# fp_32_v1.net
KiCad netlist of a schematic drawn in EAGLE
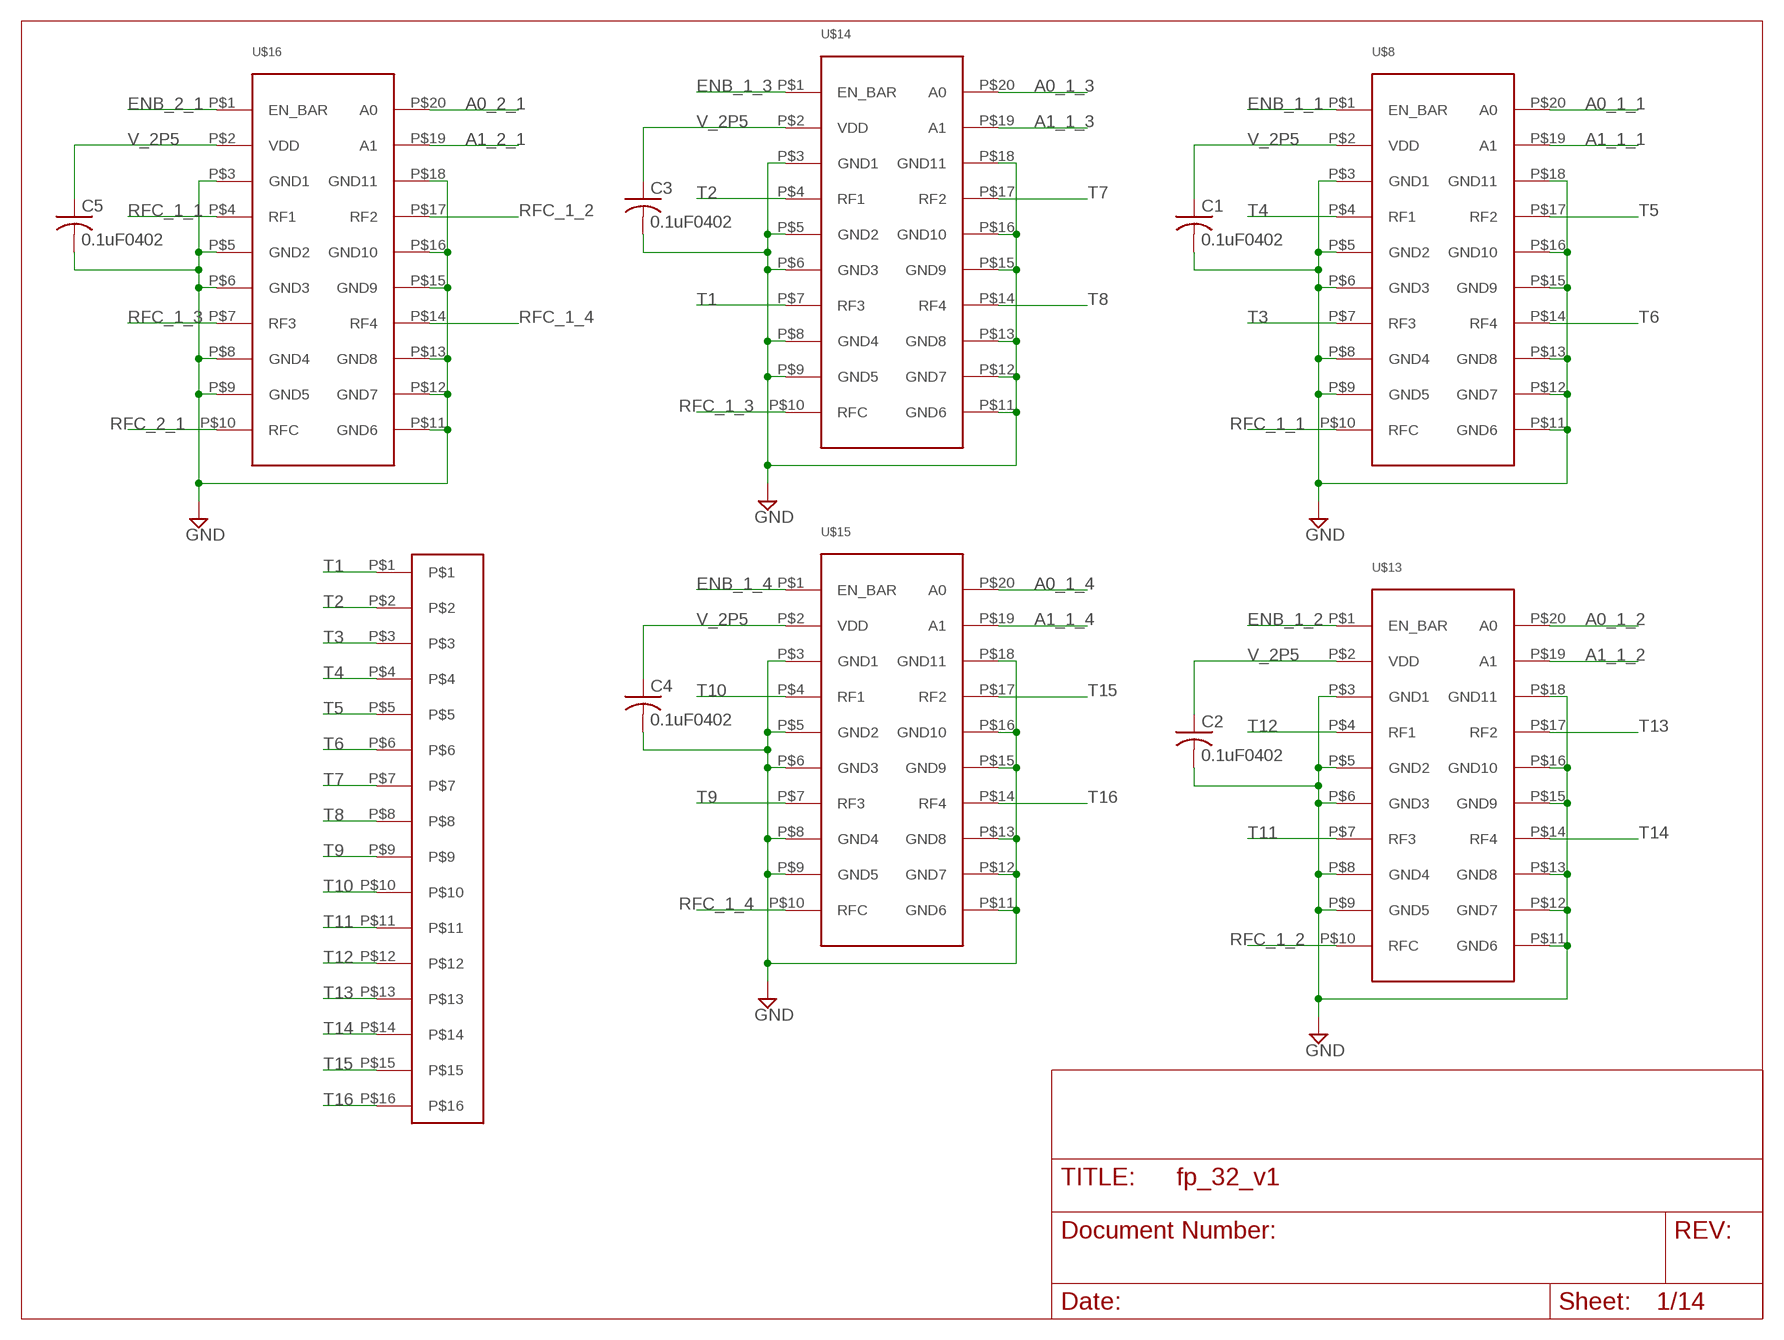
[diagram p0: schematic, sheet 1]
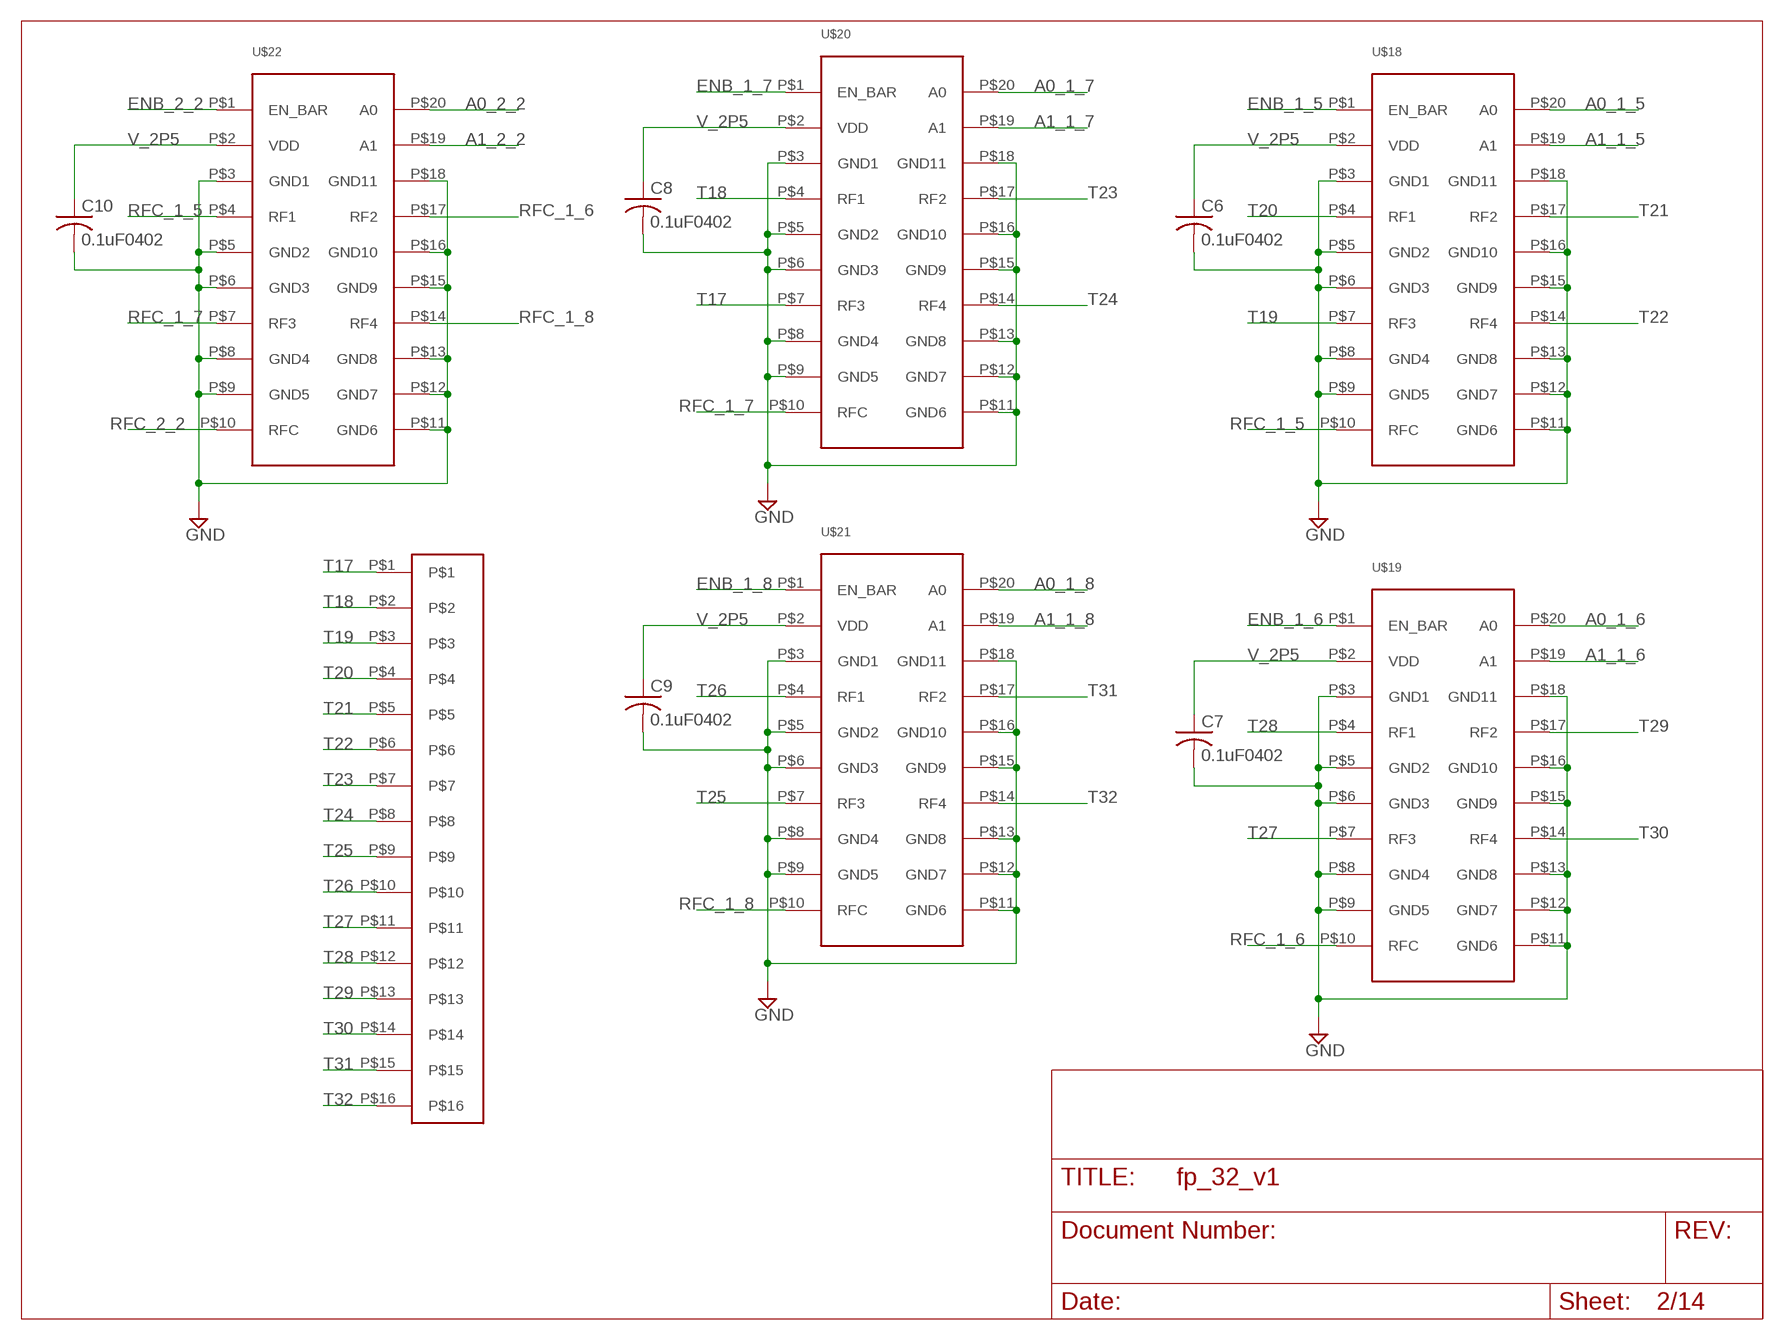
[diagram p1: schematic, sheet 2]
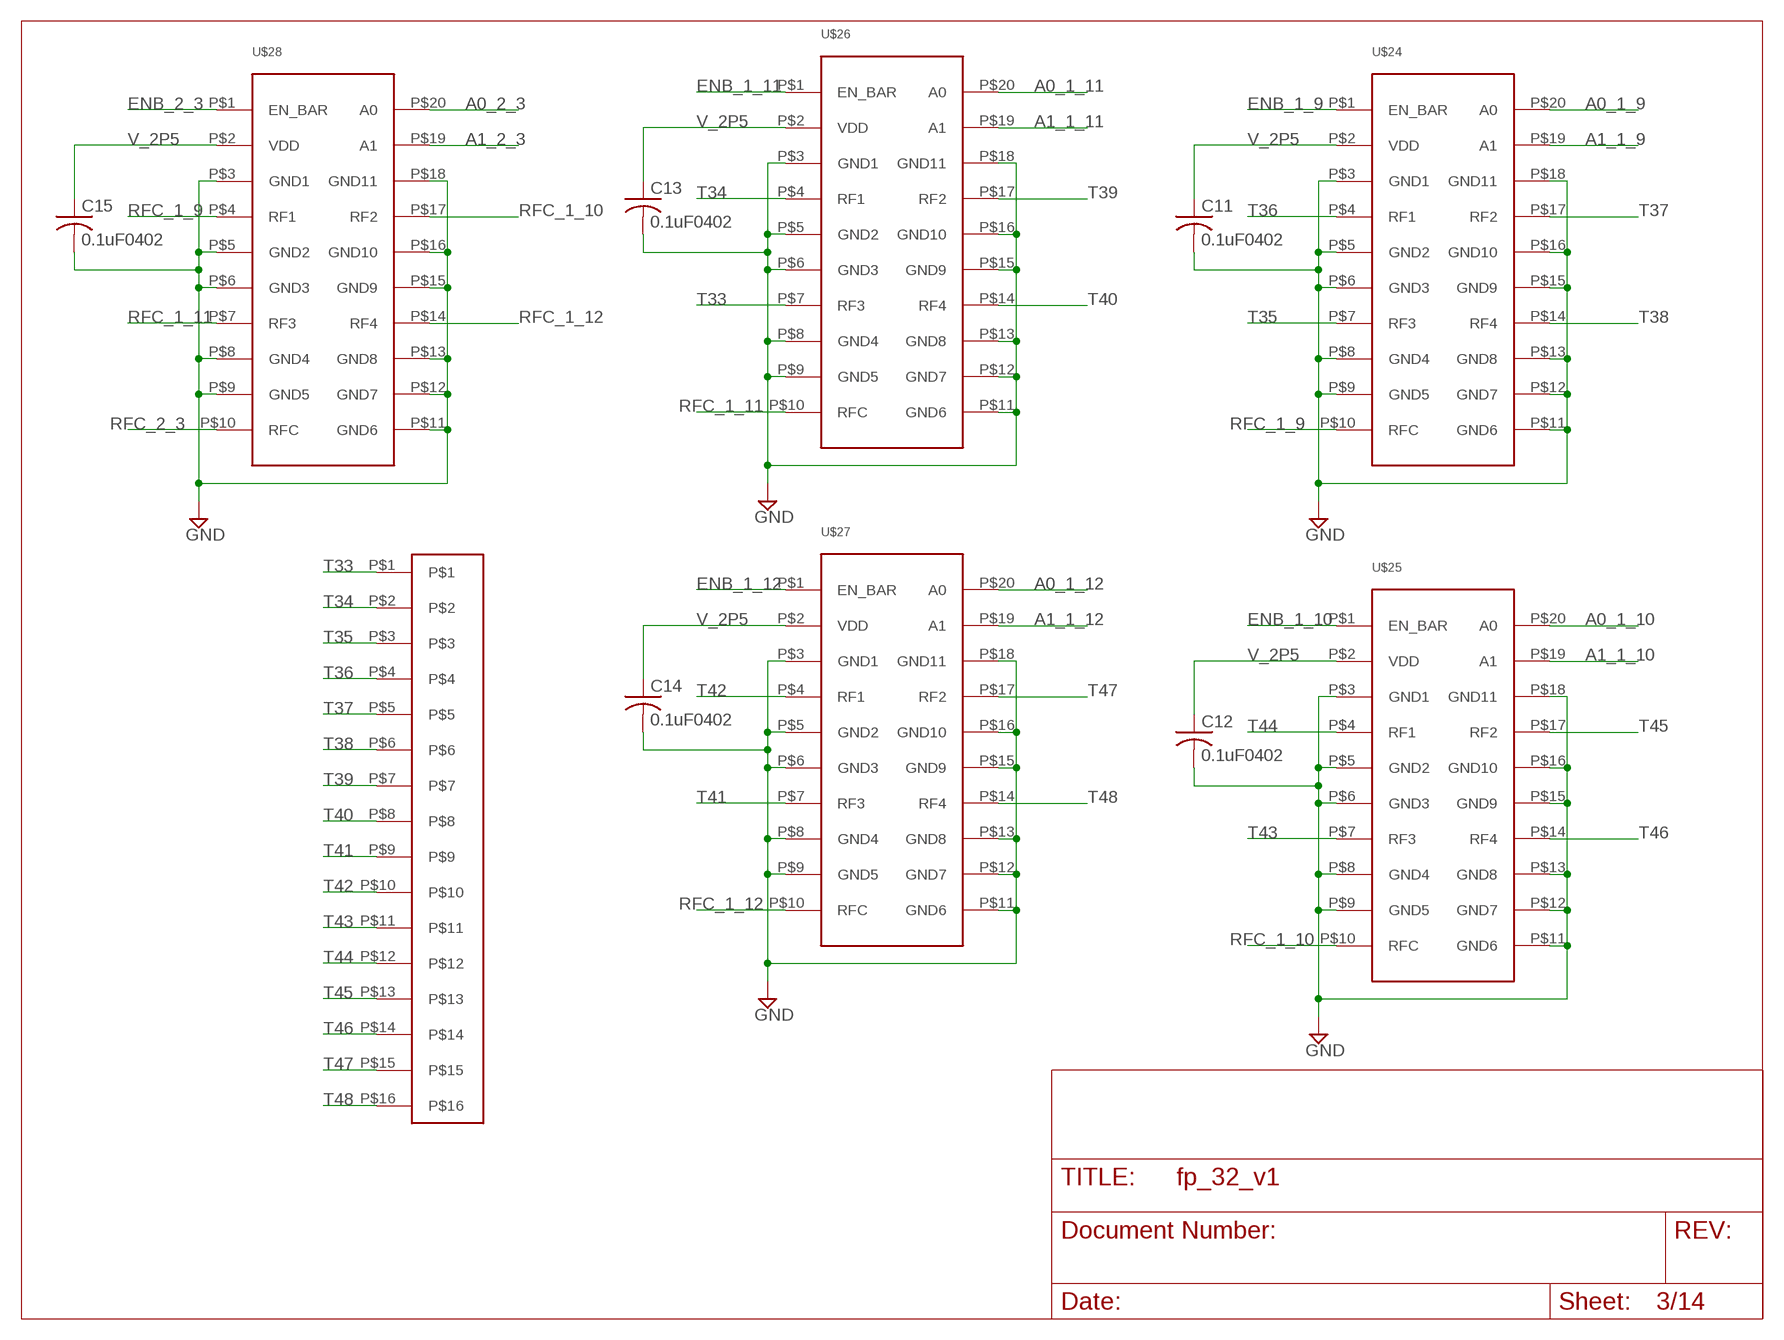
[diagram p2: schematic, sheet 3]
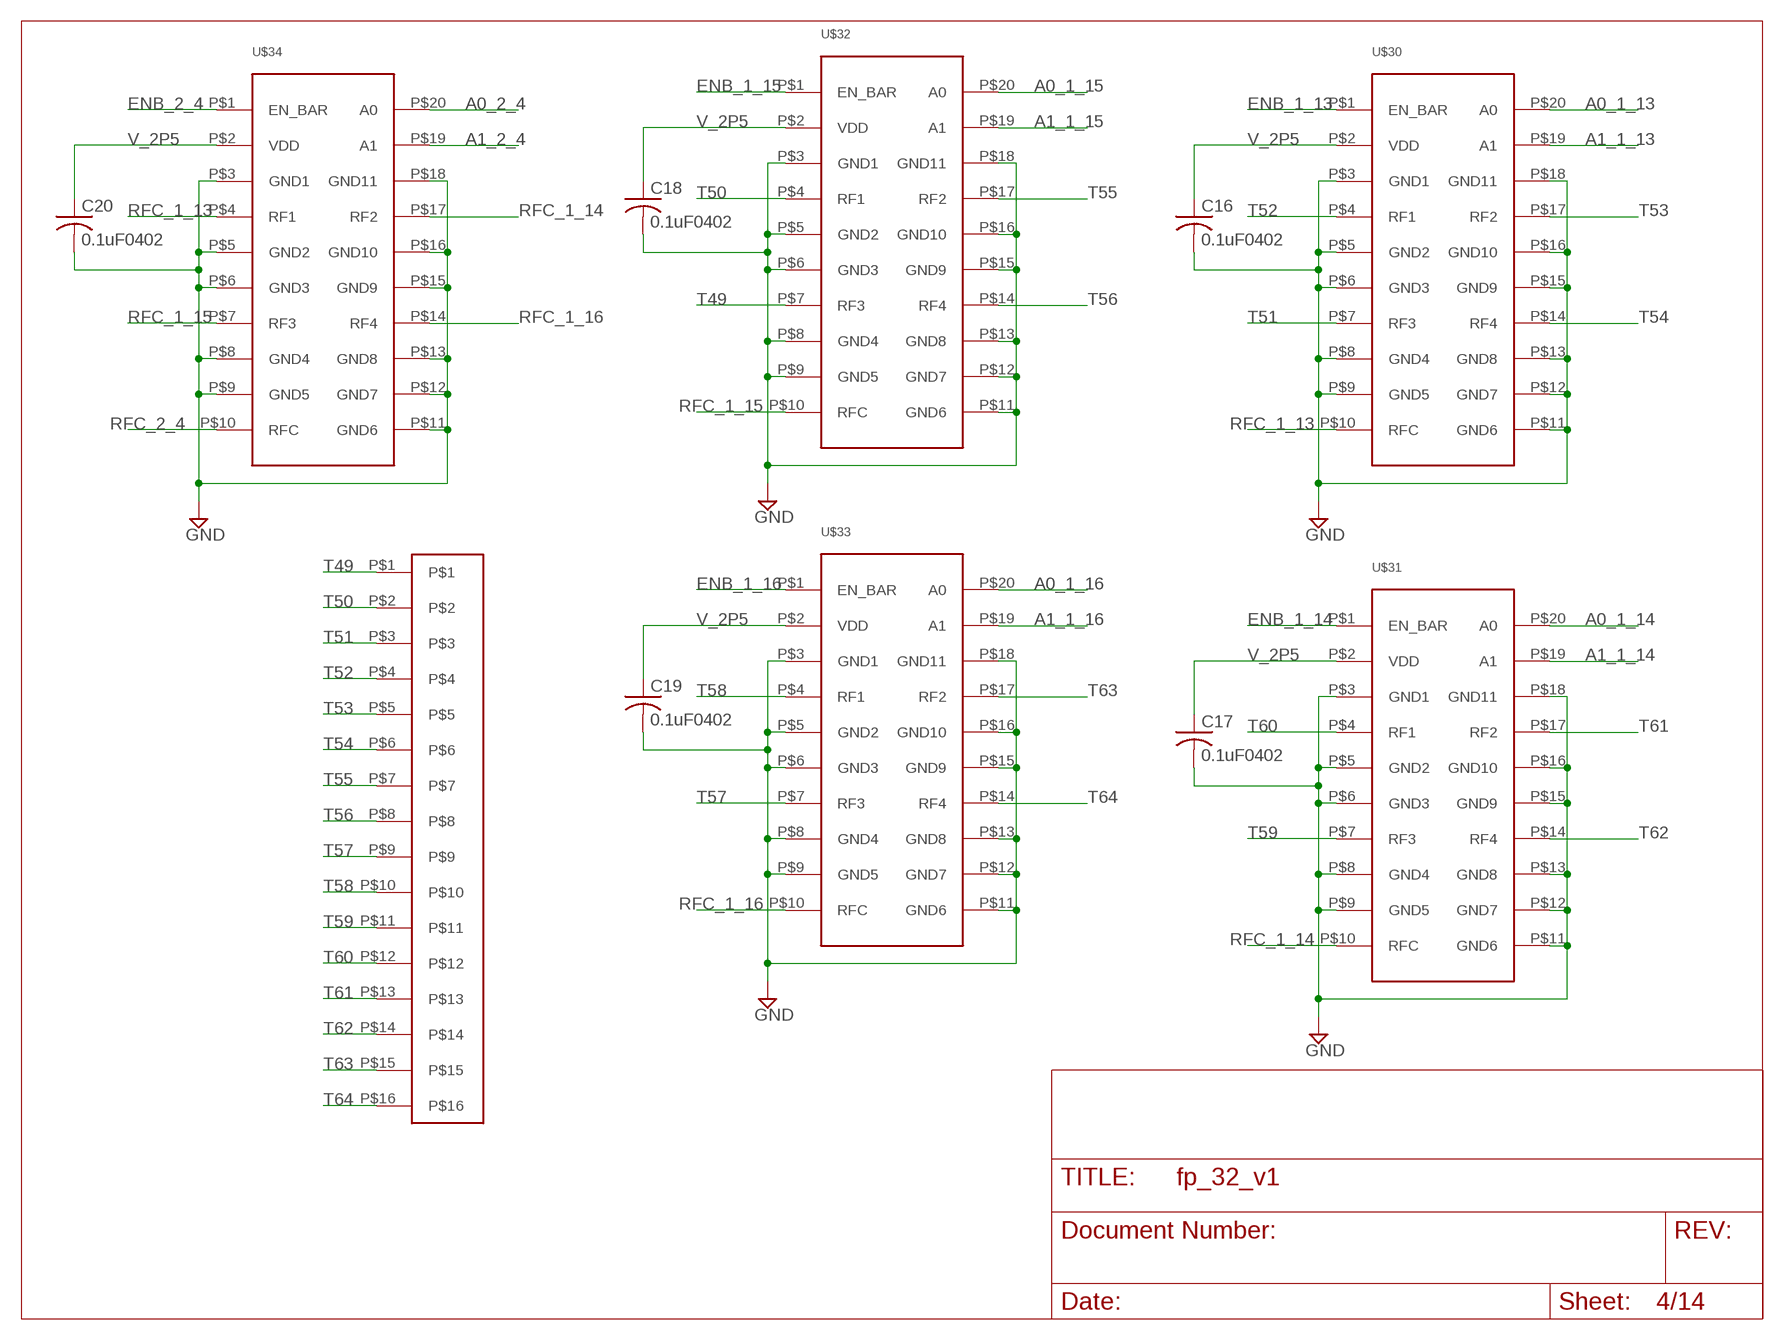
[diagram p3: schematic, sheet 4]
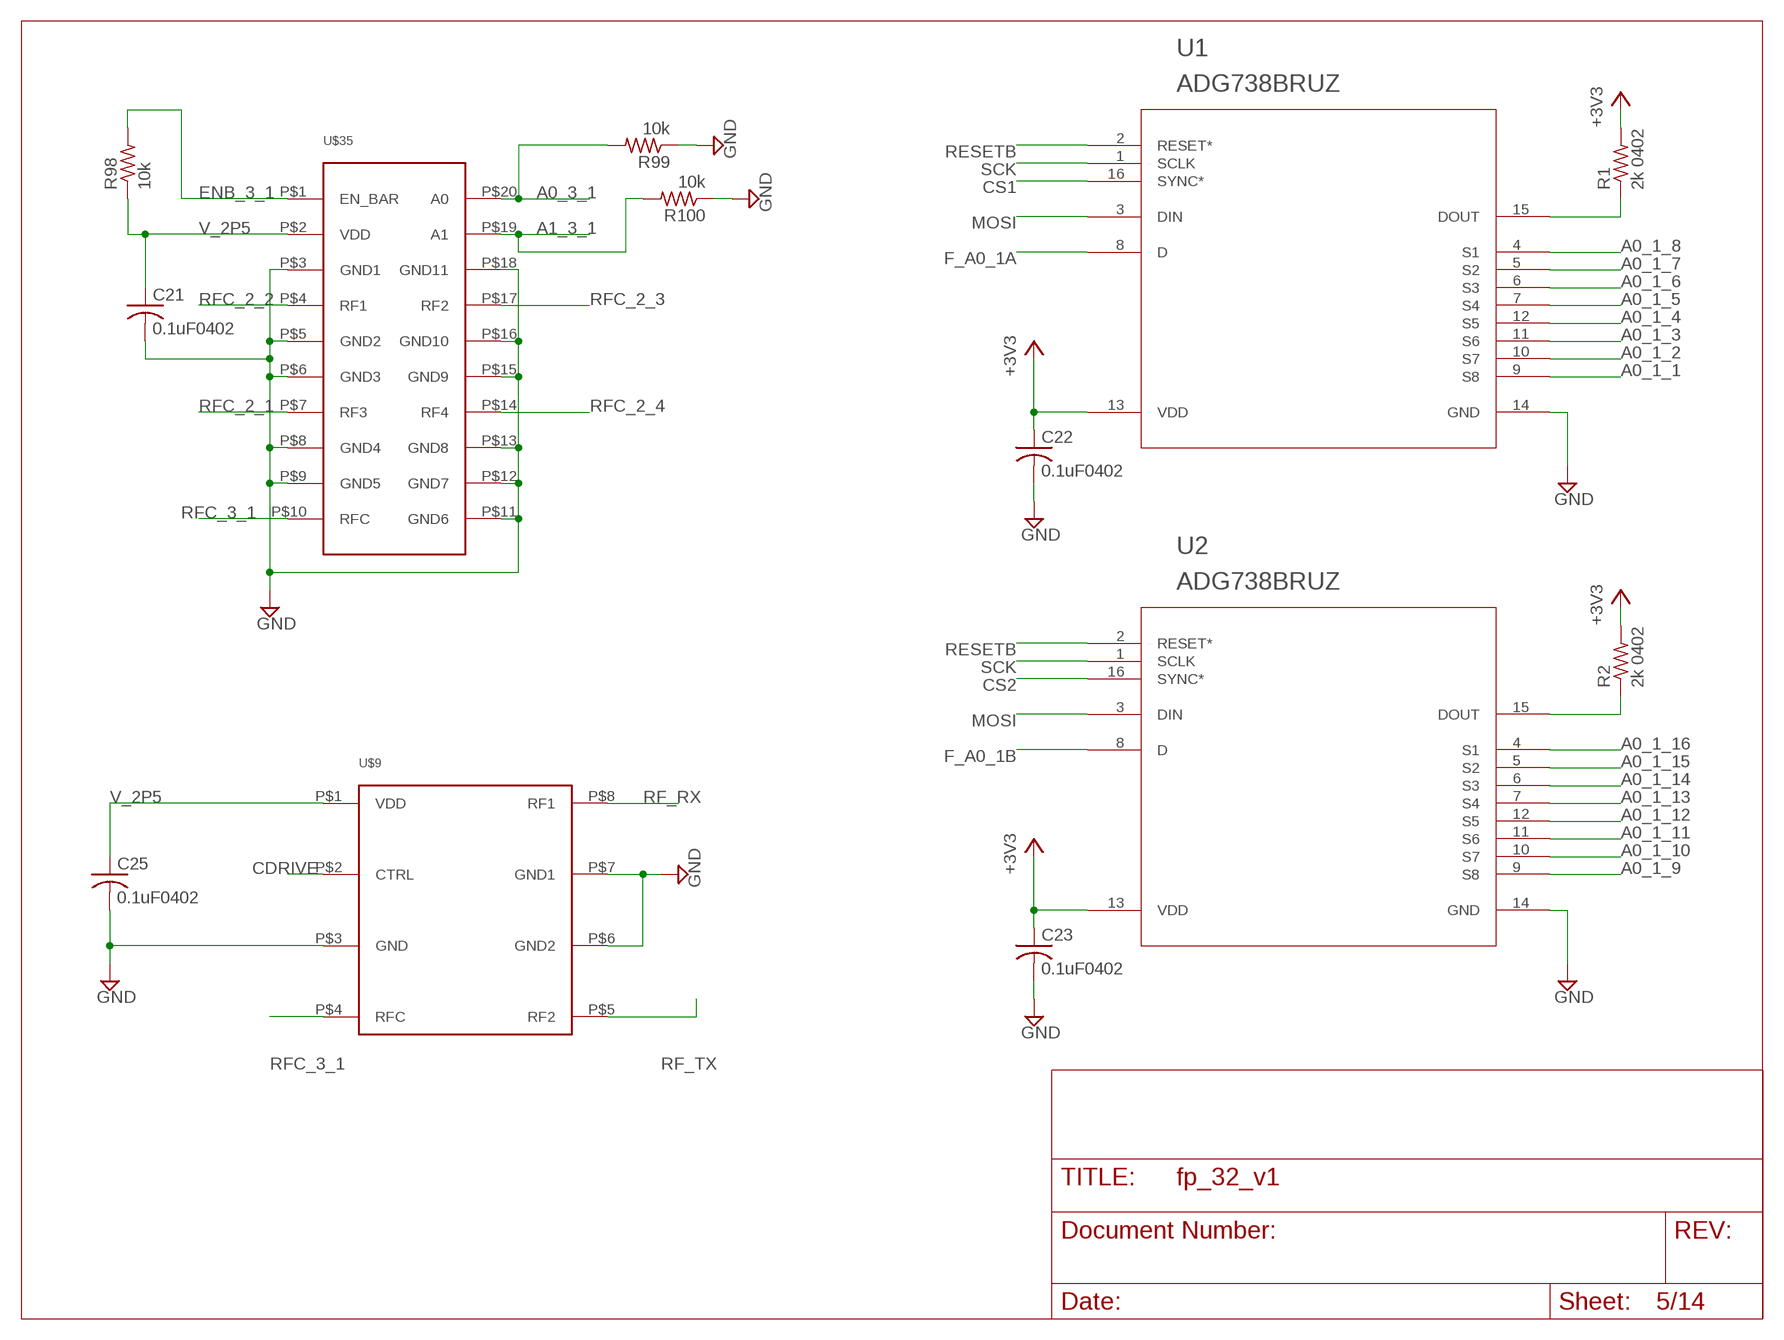
[diagram p4: schematic, sheet 5]
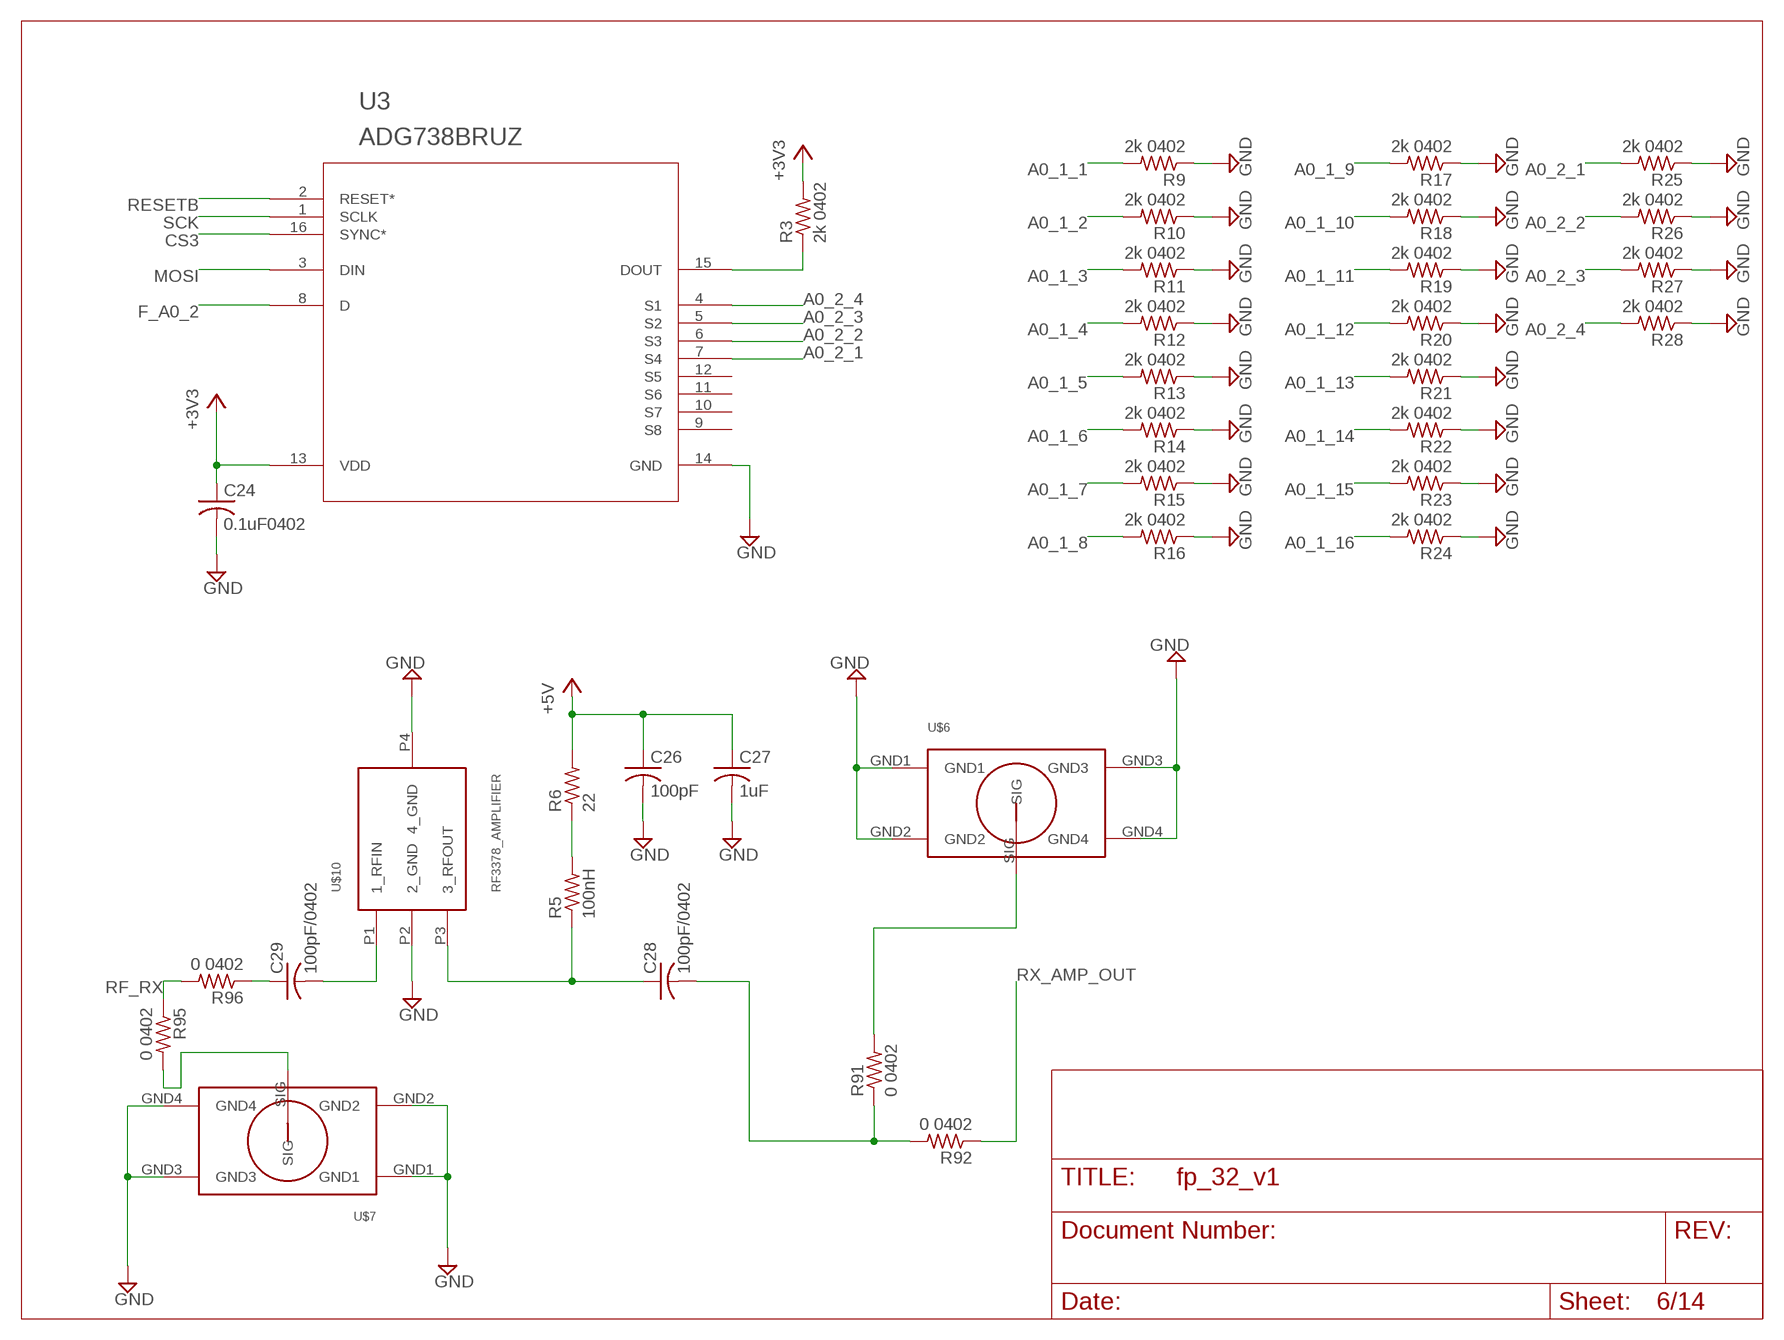
[diagram p5: schematic, sheet 6]
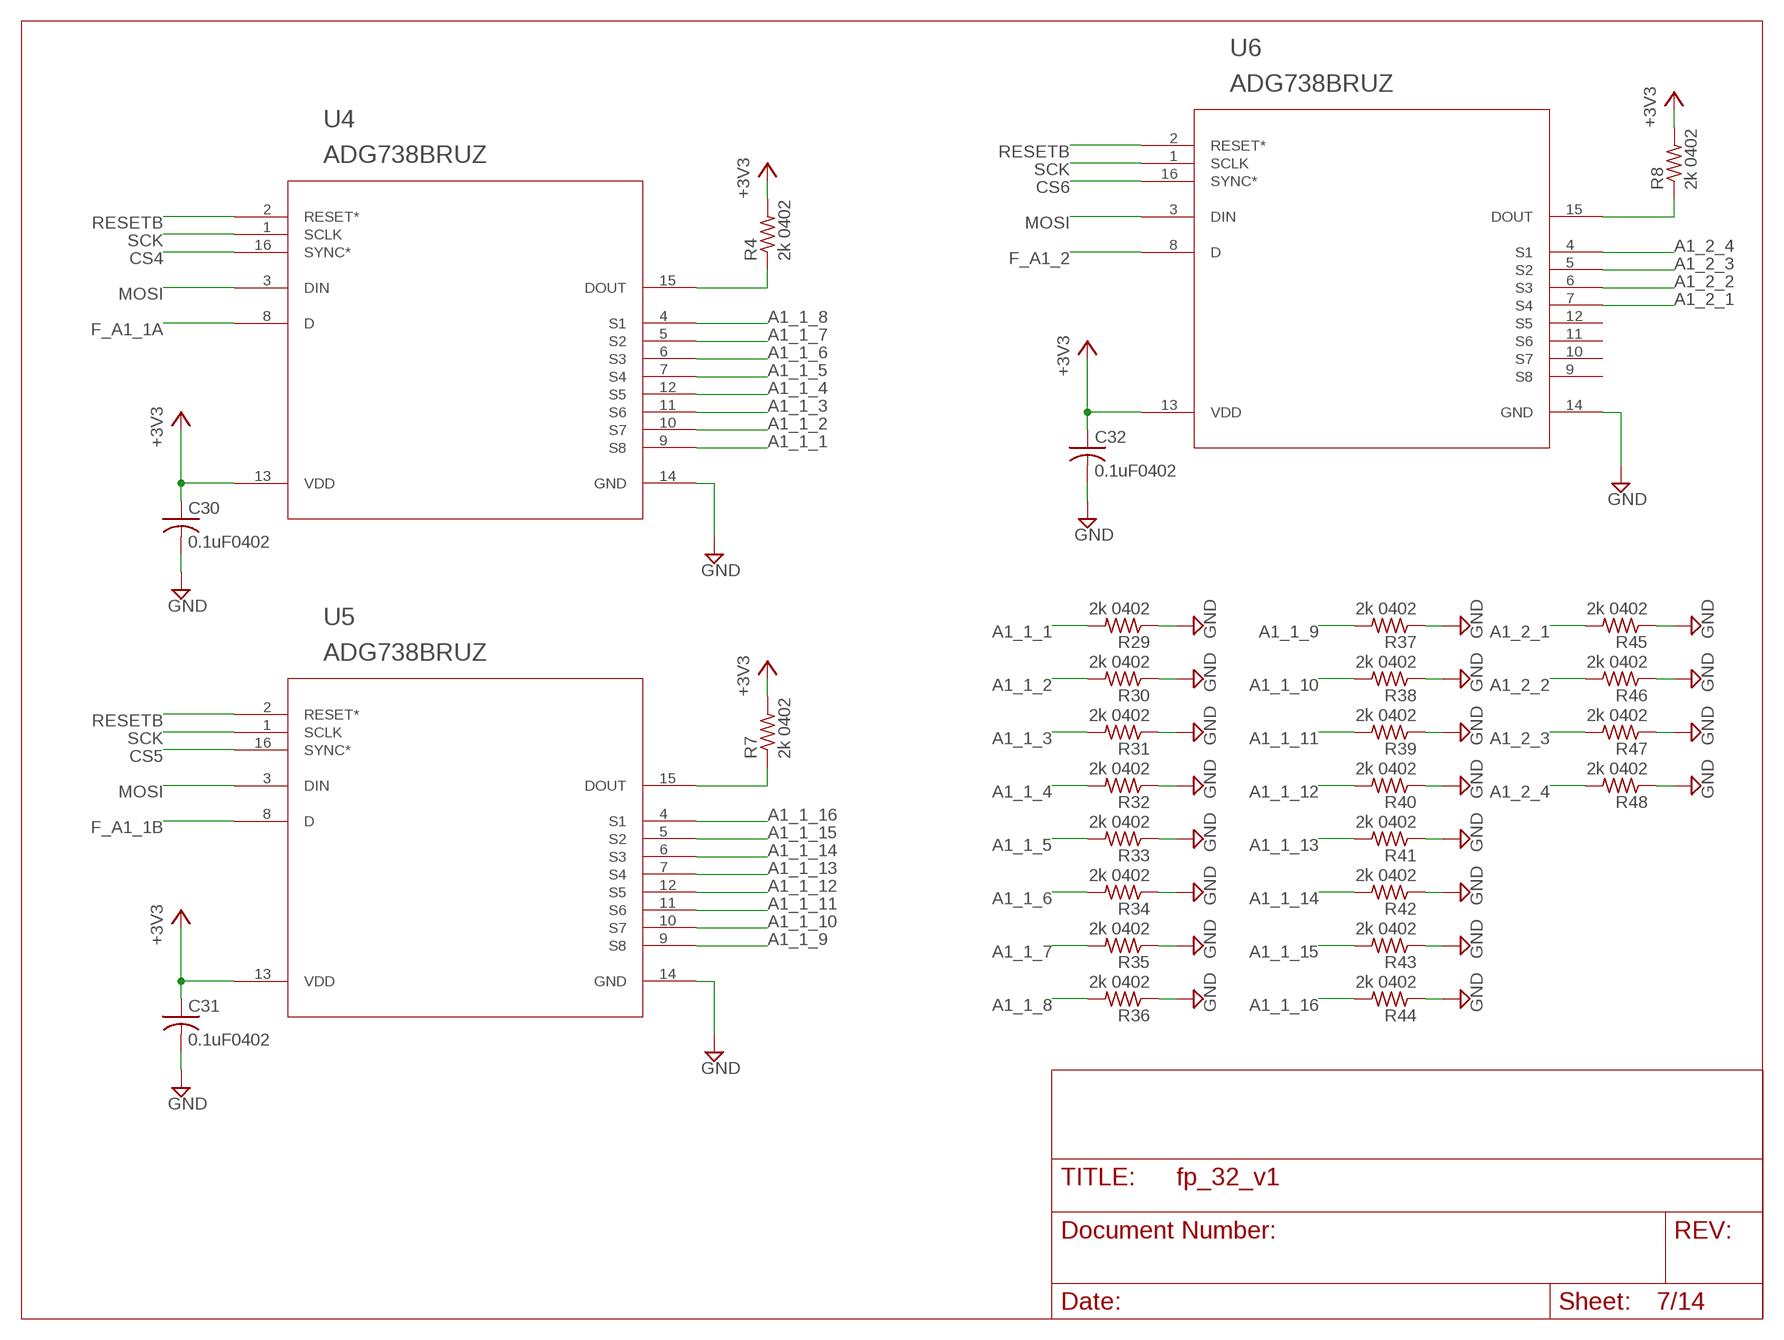
[diagram p6: schematic, sheet 7]
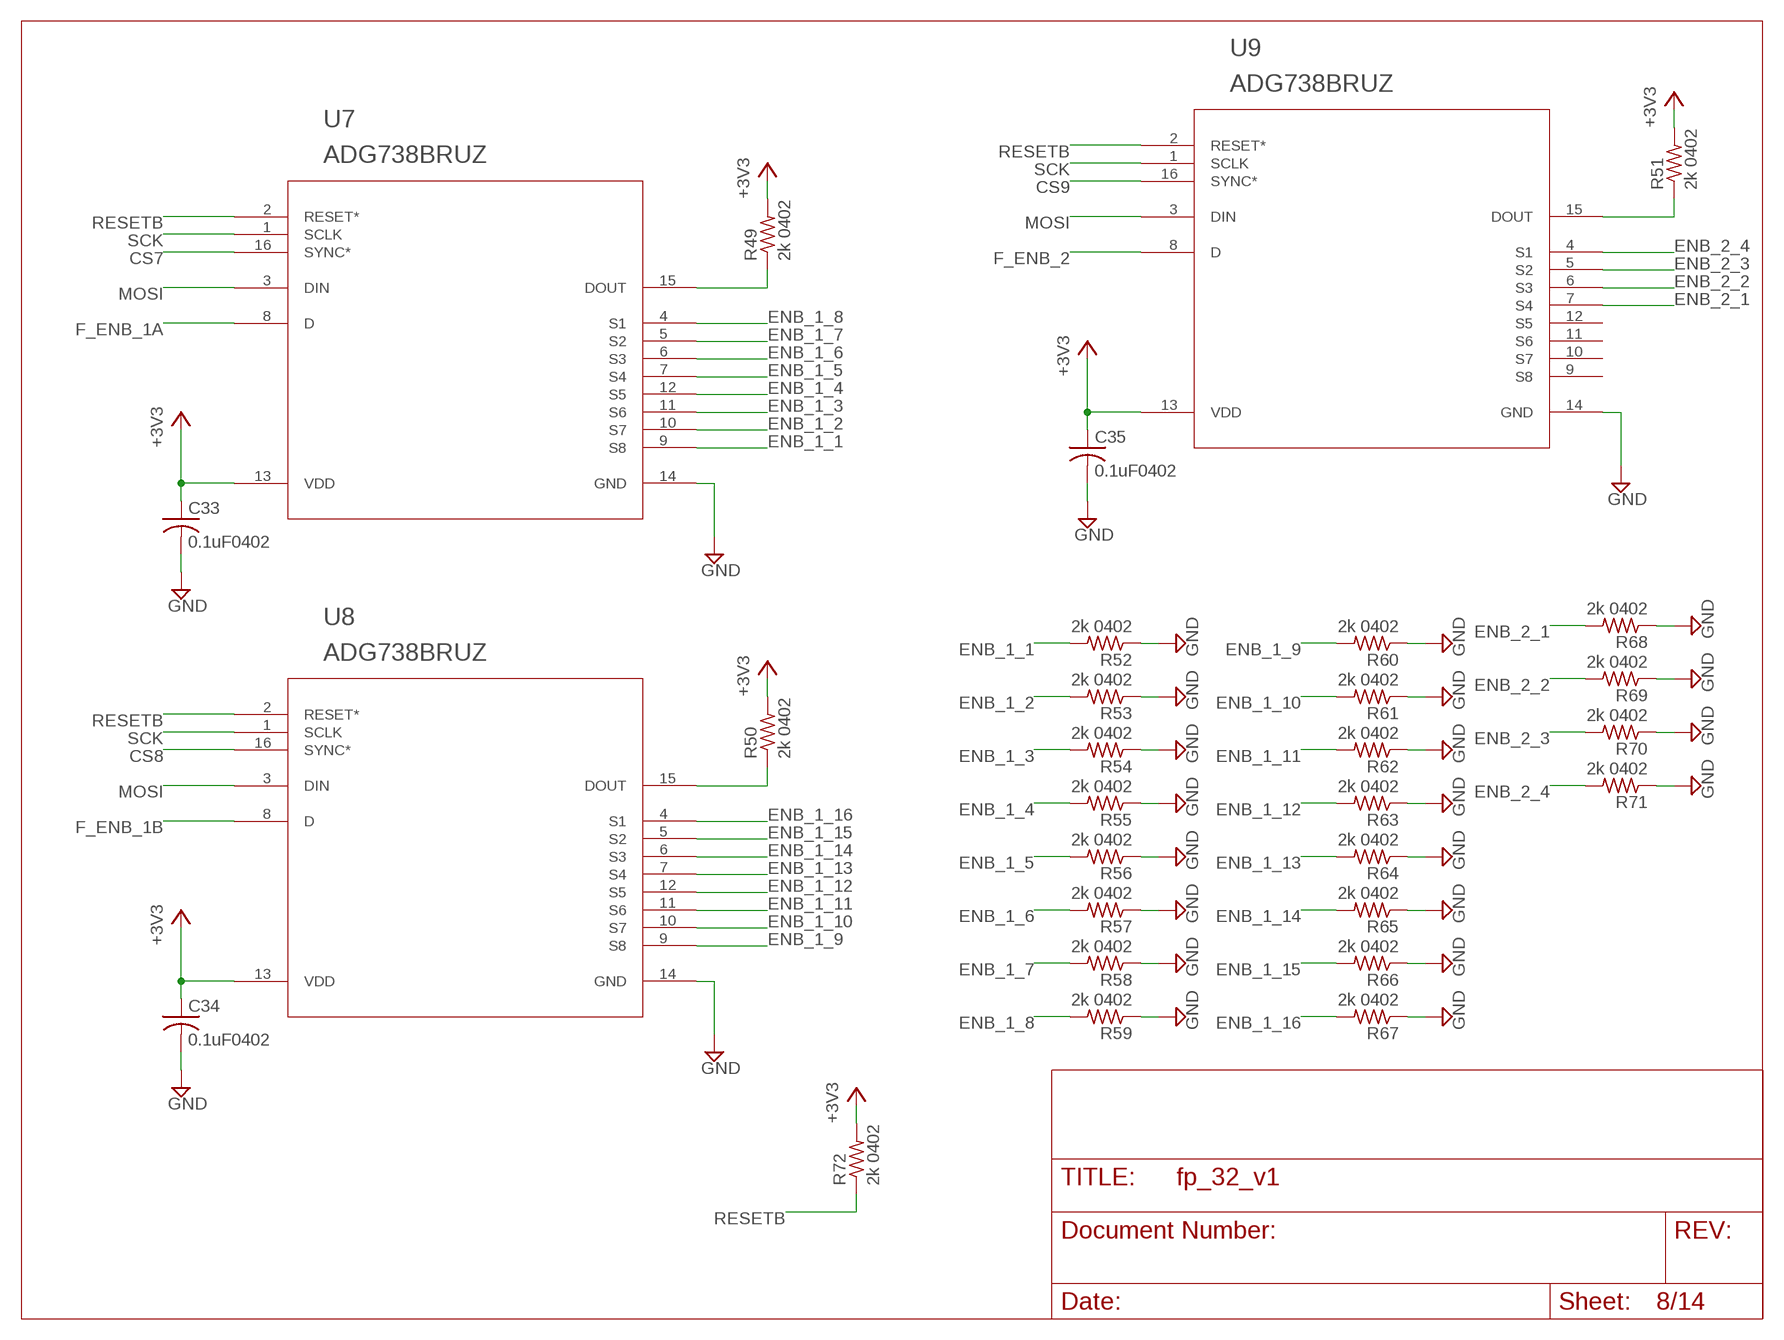
[diagram p7: schematic, sheet 8]
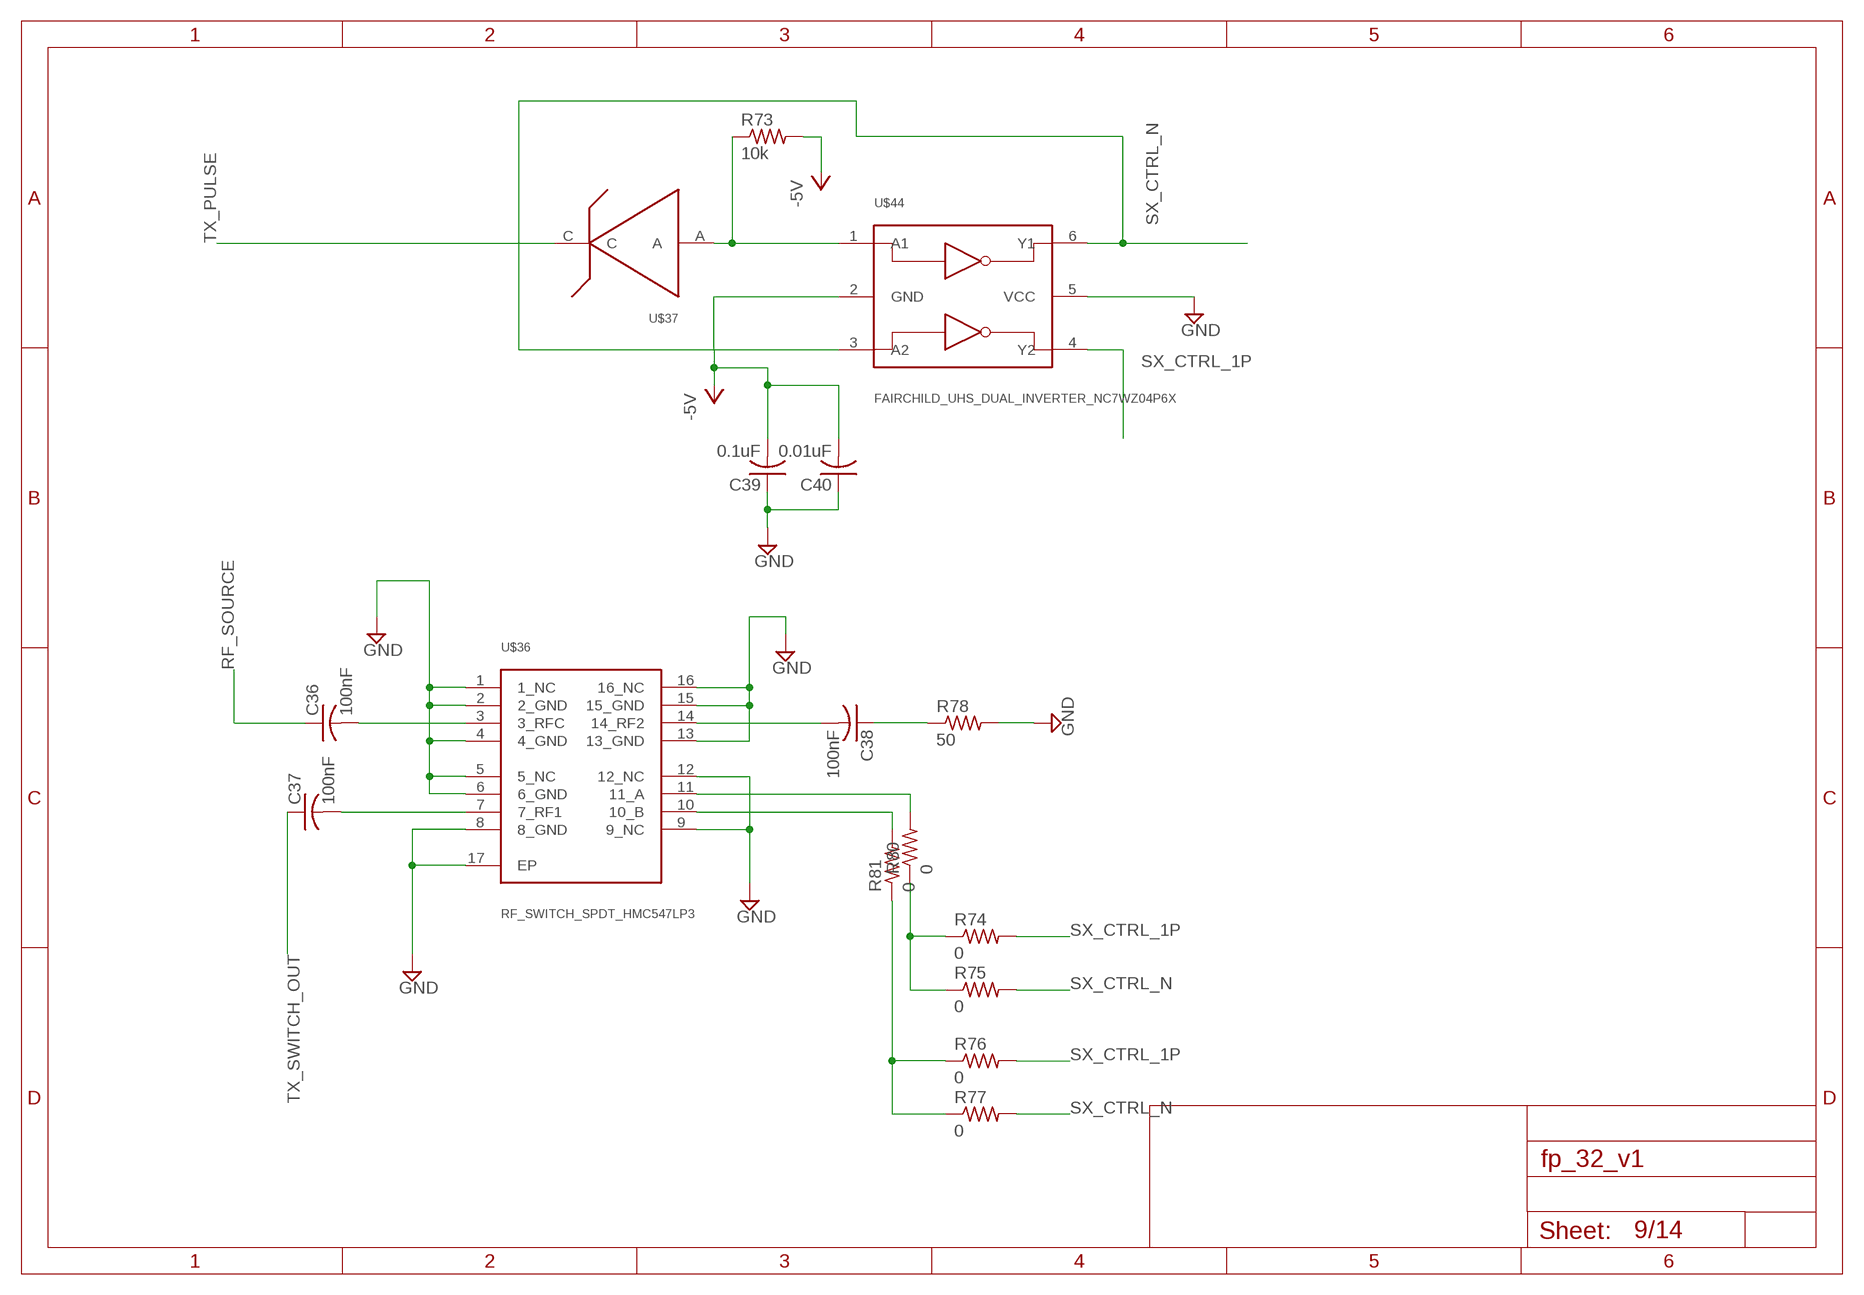
[diagram p8: schematic, sheet 9]
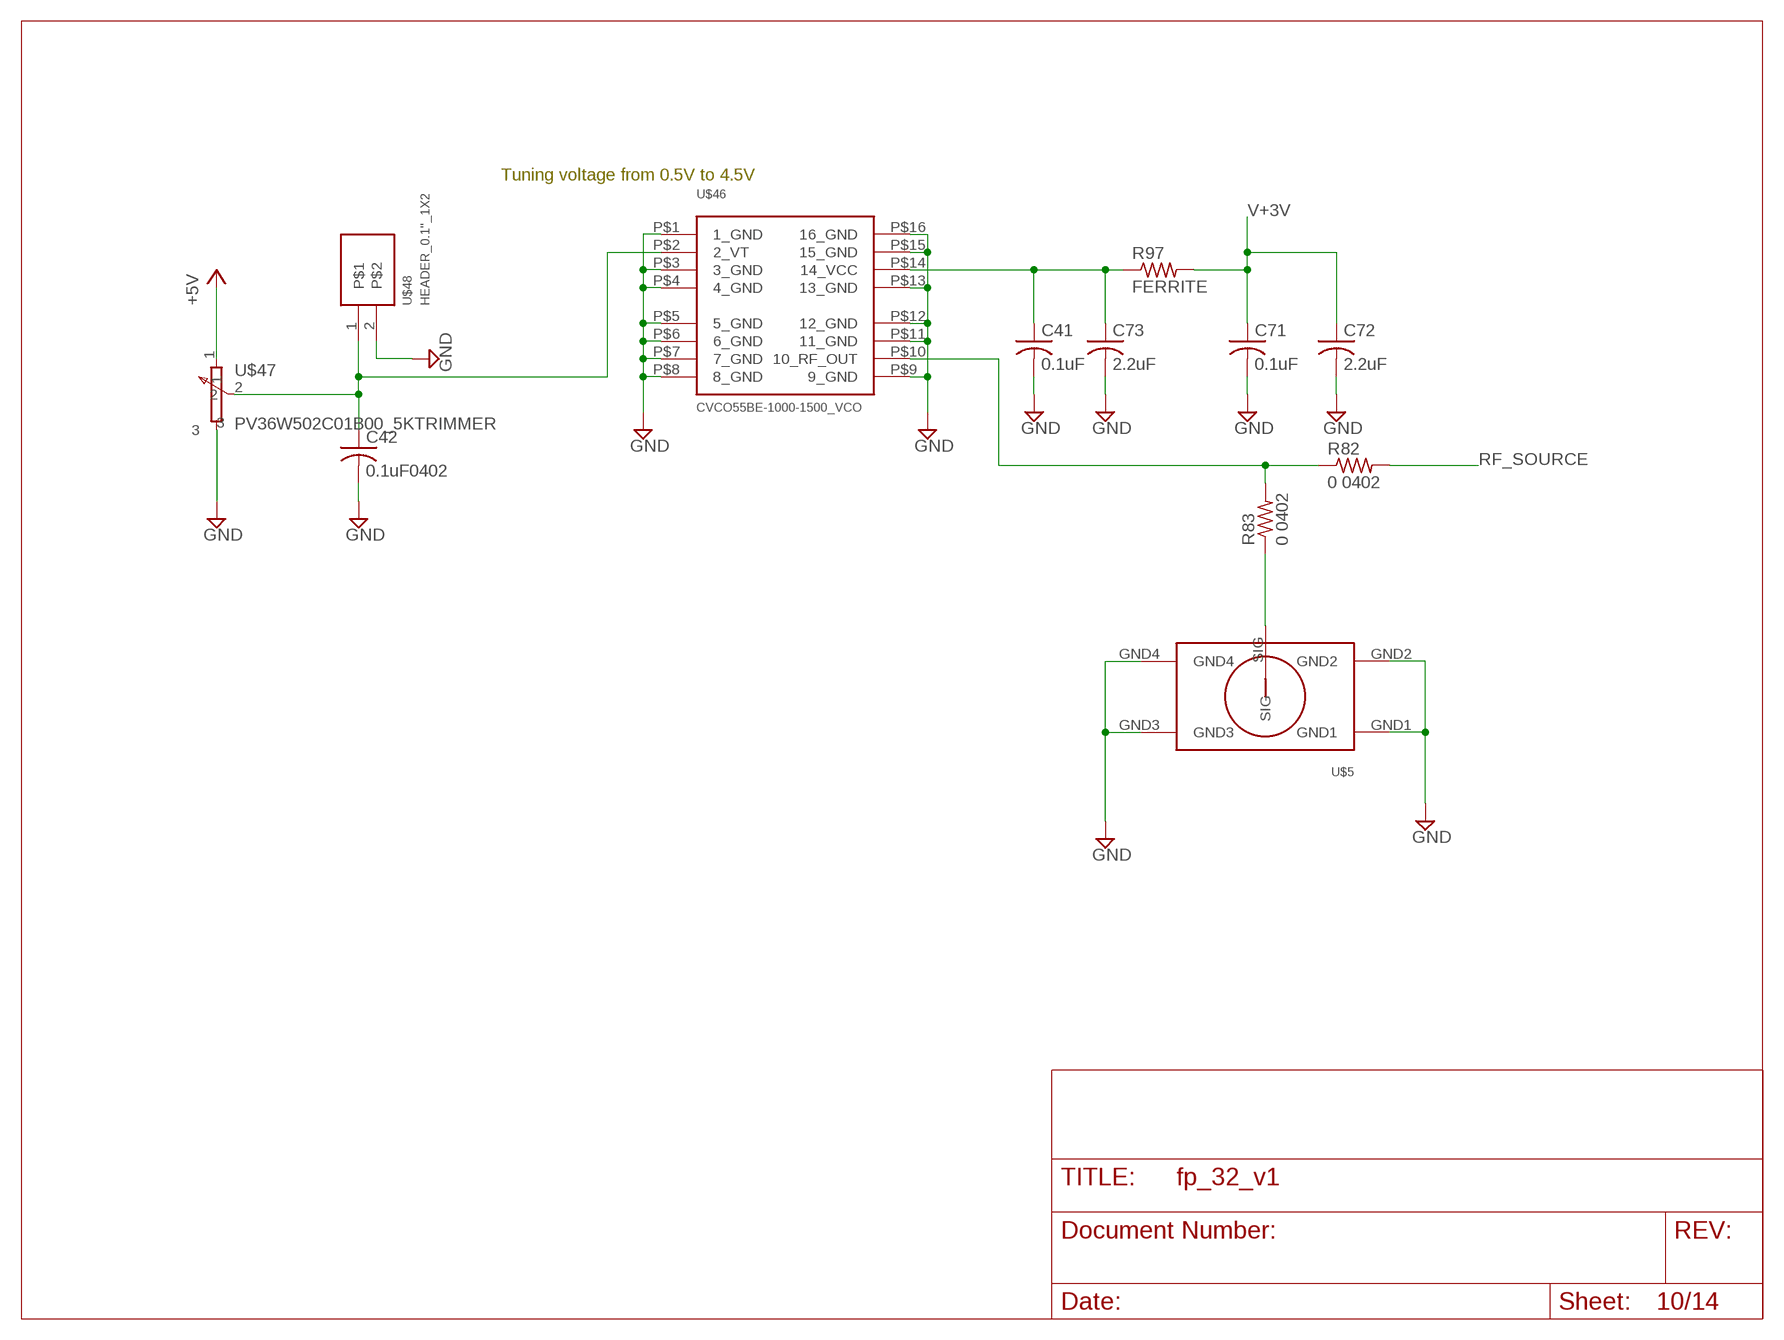
[diagram p9: schematic, sheet 10]
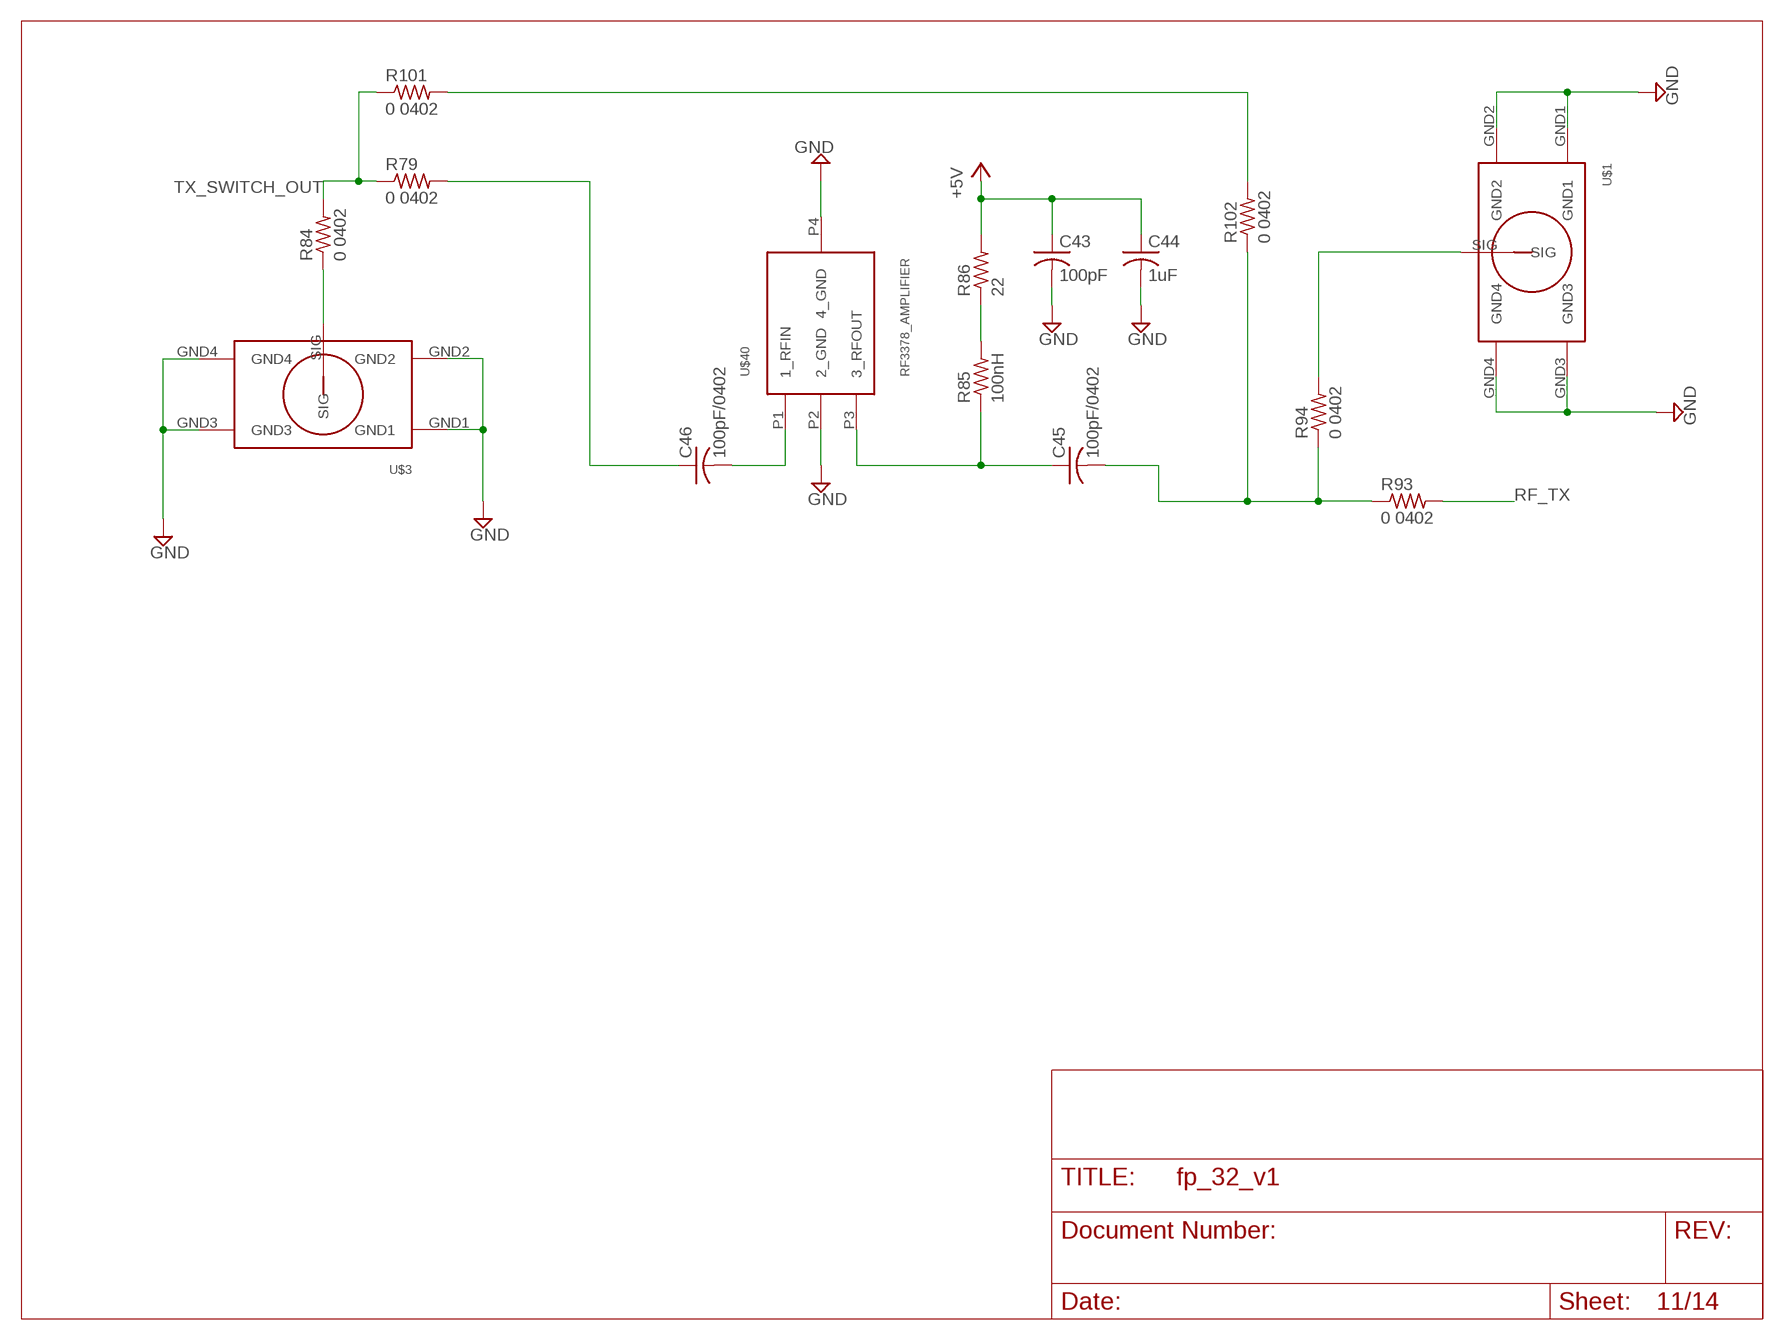
[diagram p10: schematic, sheet 11]
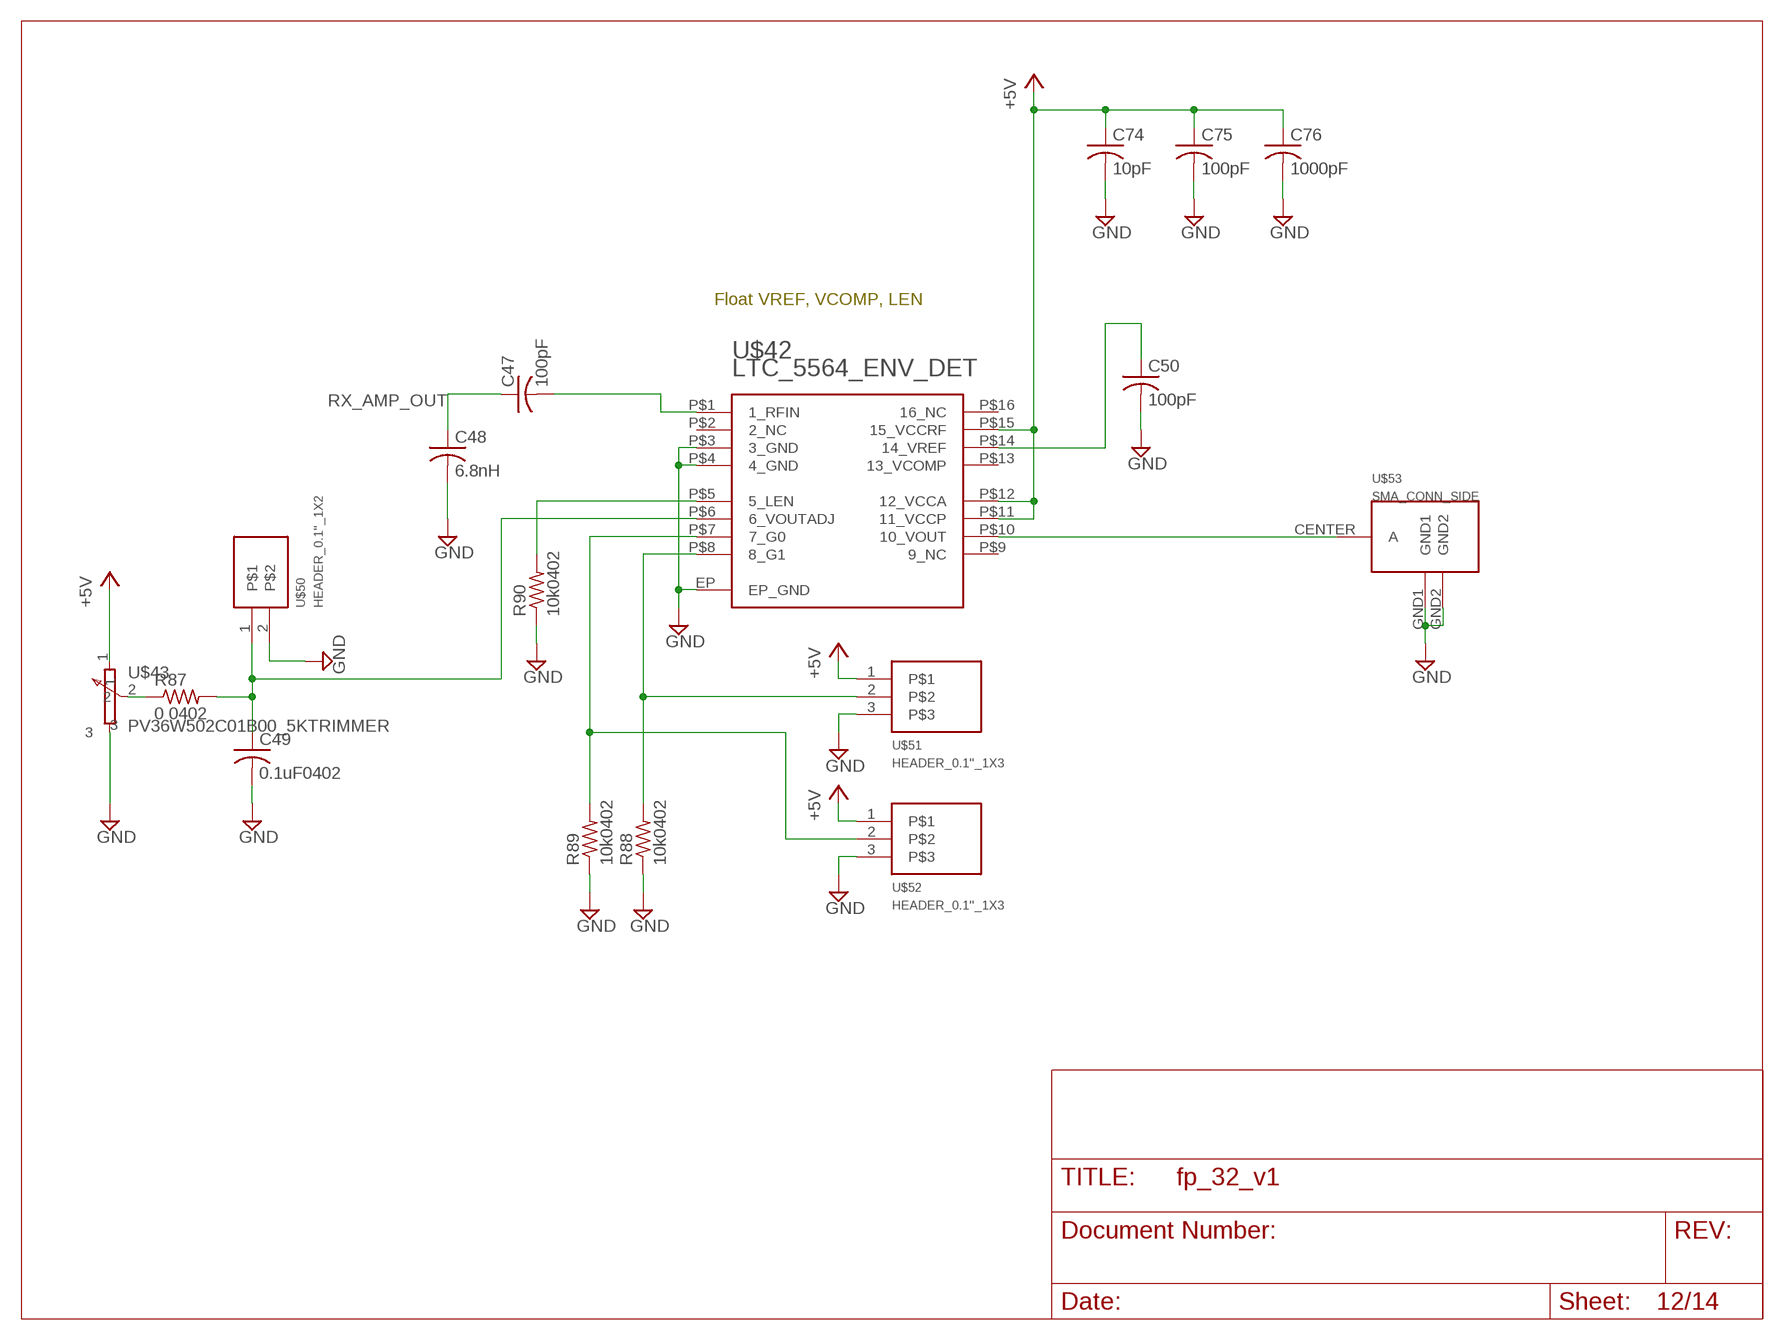
[diagram p11: schematic, sheet 12]
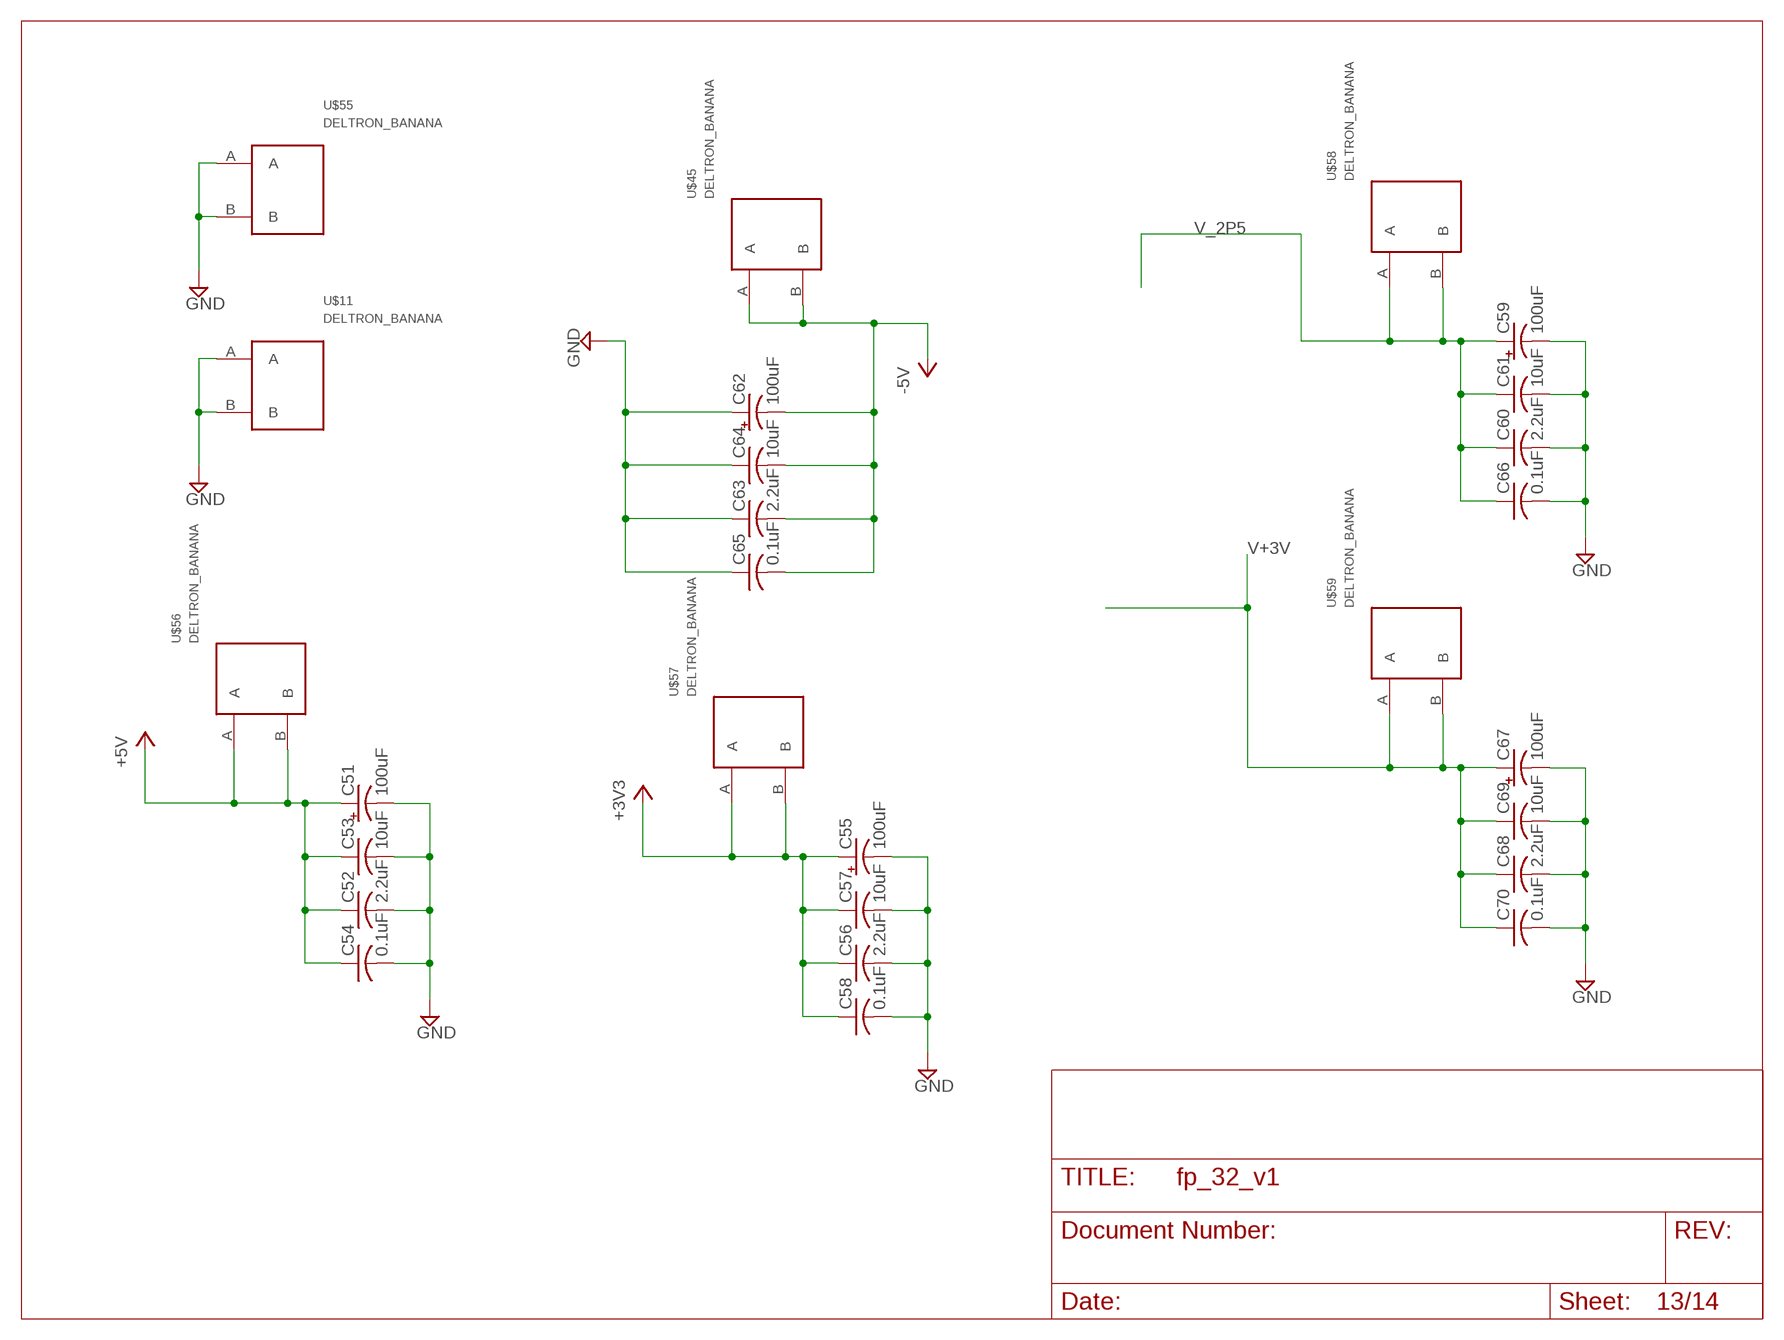
[diagram p12: schematic, sheet 13]
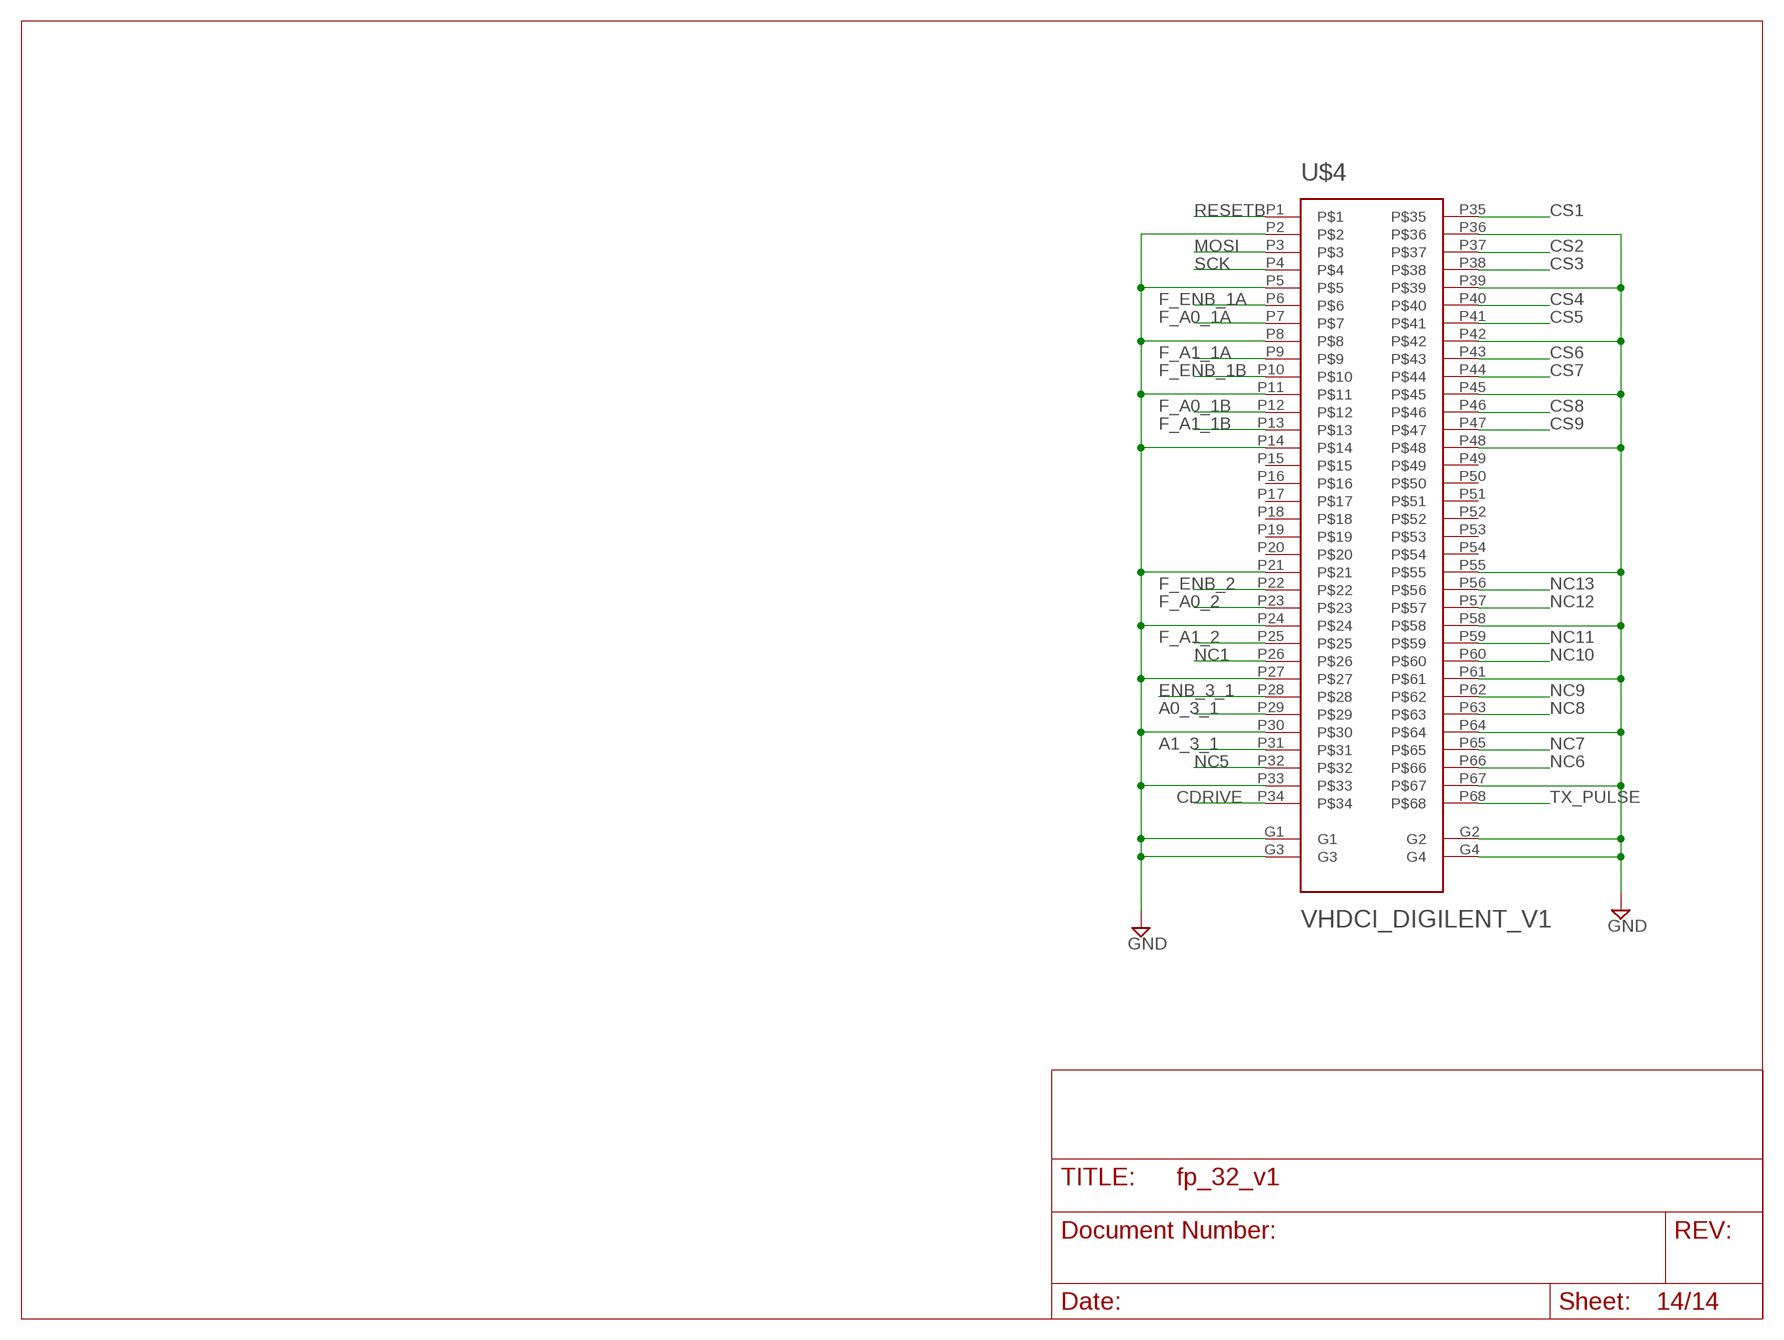
[diagram p13: schematic, sheet 14]

(export (version "E")
  (design (tool "Eeschema 10.0.6"))
  (components
    (comp (ref "C24")
      (value "0.1uF0402")
      (footprint "eagle-import:C0402")
      (libsource (lib "eagle-import") (part "C-USC0402"))
    )
    (comp (ref "C26")
      (value "100pF")
      (footprint "eagle-import:C0603")
      (libsource (lib "eagle-import") (part "C-USC0603"))
    )
    (comp (ref "C27")
      (value "1uF")
      (footprint "eagle-import:C0603")
      (libsource (lib "eagle-import") (part "C-USC0603"))
    )
    (comp (ref "C28")
      (value "100pF/0402")
      (footprint "eagle-import:C0402")
      (libsource (lib "eagle-import") (part "C-USC0402"))
    )
    (comp (ref "C29")
      (value "100pF/0402")
      (footprint "eagle-import:C0402")
      (libsource (lib "eagle-import") (part "C-USC0402"))
    )
    (comp (ref "R3")
      (value "2k 0402")
      (footprint "eagle-import:R0402")
      (libsource (lib "eagle-import") (part "R-US_R0402"))
    )
    (comp (ref "R5")
      (value "100nH")
      (footprint "eagle-import:R0603")
      (libsource (lib "eagle-import") (part "R-US_R0603"))
    )
    (comp (ref "R6")
      (value "22")
      (footprint "eagle-import:R0805")
      (libsource (lib "eagle-import") (part "R-US_R0805"))
    )
    (comp (ref "R9")
      (value "2k 0402")
      (footprint "eagle-import:R0402")
      (libsource (lib "eagle-import") (part "R-US_R0402"))
    )
    (comp (ref "R10")
      (value "2k 0402")
      (footprint "eagle-import:R0402")
      (libsource (lib "eagle-import") (part "R-US_R0402"))
    )
    (comp (ref "R11")
      (value "2k 0402")
      (footprint "eagle-import:R0402")
      (libsource (lib "eagle-import") (part "R-US_R0402"))
    )
    (comp (ref "R12")
      (value "2k 0402")
      (footprint "eagle-import:R0402")
      (libsource (lib "eagle-import") (part "R-US_R0402"))
    )
    (comp (ref "R13")
      (value "2k 0402")
      (footprint "eagle-import:R0402")
      (libsource (lib "eagle-import") (part "R-US_R0402"))
    )
    (comp (ref "R14")
      (value "2k 0402")
      (footprint "eagle-import:R0402")
      (libsource (lib "eagle-import") (part "R-US_R0402"))
    )
    (comp (ref "R15")
      (value "2k 0402")
      (footprint "eagle-import:R0402")
      (libsource (lib "eagle-import") (part "R-US_R0402"))
    )
    (comp (ref "R16")
      (value "2k 0402")
      (footprint "eagle-import:R0402")
      (libsource (lib "eagle-import") (part "R-US_R0402"))
    )
    (comp (ref "R17")
      (value "2k 0402")
      (footprint "eagle-import:R0402")
      (libsource (lib "eagle-import") (part "R-US_R0402"))
    )
    (comp (ref "R18")
      (value "2k 0402")
      (footprint "eagle-import:R0402")
      (libsource (lib "eagle-import") (part "R-US_R0402"))
    )
    (comp (ref "R19")
      (value "2k 0402")
      (footprint "eagle-import:R0402")
      (libsource (lib "eagle-import") (part "R-US_R0402"))
    )
    (comp (ref "R20")
      (value "2k 0402")
      (footprint "eagle-import:R0402")
      (libsource (lib "eagle-import") (part "R-US_R0402"))
    )
    (comp (ref "R21")
      (value "2k 0402")
      (footprint "eagle-import:R0402")
      (libsource (lib "eagle-import") (part "R-US_R0402"))
    )
    (comp (ref "R22")
      (value "2k 0402")
      (footprint "eagle-import:R0402")
      (libsource (lib "eagle-import") (part "R-US_R0402"))
    )
    (comp (ref "R23")
      (value "2k 0402")
      (footprint "eagle-import:R0402")
      (libsource (lib "eagle-import") (part "R-US_R0402"))
    )
    (comp (ref "R24")
      (value "2k 0402")
      (footprint "eagle-import:R0402")
      (libsource (lib "eagle-import") (part "R-US_R0402"))
    )
    (comp (ref "R25")
      (value "2k 0402")
      (footprint "eagle-import:R0402")
      (libsource (lib "eagle-import") (part "R-US_R0402"))
    )
    (comp (ref "R26")
      (value "2k 0402")
      (footprint "eagle-import:R0402")
      (libsource (lib "eagle-import") (part "R-US_R0402"))
    )
    (comp (ref "R27")
      (value "2k 0402")
      (footprint "eagle-import:R0402")
      (libsource (lib "eagle-import") (part "R-US_R0402"))
    )
    (comp (ref "R28")
      (value "2k 0402")
      (footprint "eagle-import:R0402")
      (libsource (lib "eagle-import") (part "R-US_R0402"))
    )
    (comp (ref "R91")
      (value "0 0402")
      (footprint "eagle-import:R0402")
      (libsource (lib "eagle-import") (part "R-US_R0402"))
    )
    (comp (ref "R92")
      (value "0 0402")
      (footprint "eagle-import:R0402")
      (libsource (lib "eagle-import") (part "R-US_R0402"))
    )
    (comp (ref "R95")
      (value "0 0402")
      (footprint "eagle-import:R0402")
      (libsource (lib "eagle-import") (part "R-US_R0402"))
    )
    (comp (ref "R96")
      (value "0 0402")
      (footprint "eagle-import:R0402")
      (libsource (lib "eagle-import") (part "R-US_R0402"))
    )
    (comp (ref "U$6")
      (value "MINISMP_PE44970_THRUHOLE")
      (footprint "eagle-import:MINISMP_PE44970_THRU_HOLE")
      (libsource (lib "eagle-import") (part "MINISMP_PE44970_THRUHOLE"))
    )
    (comp (ref "U$7")
      (value "MINISMP_PE44970_THRUHOLE")
      (footprint "eagle-import:MINISMP_PE44970_THRU_HOLE")
      (libsource (lib "eagle-import") (part "MINISMP_PE44970_THRUHOLE"))
    )
    (comp (ref "U$10")
      (value "RF3378_AMPLIFIER")
      (footprint "eagle-import:TO243AA_SOT89")
      (libsource (lib "eagle-import") (part "RF3378_AMPLIFIER"))
    )
    (comp (ref "U3")
      (value "ADG738BRUZ")
      (footprint "eagle-import:RU_16")
      (libsource (lib "eagle-import") (part "ADG738BRUZ"))
    )
    (comp (ref "C21")
      (value "0.1uF0402")
      (footprint "eagle-import:C0402")
      (libsource (lib "eagle-import") (part "C-USC0402"))
    )
    (comp (ref "C22")
      (value "0.1uF0402")
      (footprint "eagle-import:C0402")
      (libsource (lib "eagle-import") (part "C-USC0402"))
    )
    (comp (ref "C23")
      (value "0.1uF0402")
      (footprint "eagle-import:C0402")
      (libsource (lib "eagle-import") (part "C-USC0402"))
    )
    (comp (ref "C25")
      (value "0.1uF0402")
      (footprint "eagle-import:C0402")
      (libsource (lib "eagle-import") (part "C-USC0402"))
    )
    (comp (ref "R1")
      (value "2k 0402")
      (footprint "eagle-import:R0402")
      (libsource (lib "eagle-import") (part "R-US_R0402"))
    )
    (comp (ref "R2")
      (value "2k 0402")
      (footprint "eagle-import:R0402")
      (libsource (lib "eagle-import") (part "R-US_R0402"))
    )
    (comp (ref "R98")
      (value "10k")
      (footprint "eagle-import:R0402")
      (libsource (lib "eagle-import") (part "R-US_R0402"))
    )
    (comp (ref "R99")
      (value "10k")
      (footprint "eagle-import:R0402")
      (libsource (lib "eagle-import") (part "R-US_R0402"))
    )
    (comp (ref "R100")
      (value "10k")
      (footprint "eagle-import:R0402")
      (libsource (lib "eagle-import") (part "R-US_R0402"))
    )
    (comp (ref "U$9")
      (value "TIC_TESTING_ADG918BRMZ-500RL7CT")
      (footprint "eagle-import:TIC_TESTING_ADG918BRMZ-500RL7CT-ND")
      (libsource (lib "eagle-import") (part "TIC_TESTING_ADG918BRMZ-500RL7CT"))
    )
    (comp (ref "U$35")
      (value "TICLIB2_ADG904")
      (footprint "eagle-import:TICLIB2_ADG904_TSSOP")
      (libsource (lib "eagle-import") (part "TICLIB2_ADG904"))
    )
    (comp (ref "U1")
      (value "ADG738BRUZ")
      (footprint "eagle-import:RU_16")
      (libsource (lib "eagle-import") (part "ADG738BRUZ"))
    )
    (comp (ref "U2")
      (value "ADG738BRUZ")
      (footprint "eagle-import:RU_16")
      (libsource (lib "eagle-import") (part "ADG738BRUZ"))
    )
    (comp (ref "C1")
      (value "0.1uF0402")
      (footprint "eagle-import:C0402")
      (libsource (lib "eagle-import") (part "C-USC0402"))
    )
    (comp (ref "C2")
      (value "0.1uF0402")
      (footprint "eagle-import:C0402")
      (libsource (lib "eagle-import") (part "C-USC0402"))
    )
    (comp (ref "C3")
      (value "0.1uF0402")
      (footprint "eagle-import:C0402")
      (libsource (lib "eagle-import") (part "C-USC0402"))
    )
    (comp (ref "C4")
      (value "0.1uF0402")
      (footprint "eagle-import:C0402")
      (libsource (lib "eagle-import") (part "C-USC0402"))
    )
    (comp (ref "C5")
      (value "0.1uF0402")
      (footprint "eagle-import:C0402")
      (libsource (lib "eagle-import") (part "C-USC0402"))
    )
    (comp (ref "U$2")
      (value "FP-BOND-6MIL")
      (footprint "eagle-import:FP_BOND_6MIL")
      (libsource (lib "eagle-import") (part "FP-BOND-6MIL"))
    )
    (comp (ref "U$8")
      (value "TICLIB2_ADG904")
      (footprint "eagle-import:TICLIB2_ADG904_TSSOP")
      (libsource (lib "eagle-import") (part "TICLIB2_ADG904"))
    )
    (comp (ref "U$13")
      (value "TICLIB2_ADG904")
      (footprint "eagle-import:TICLIB2_ADG904_TSSOP")
      (libsource (lib "eagle-import") (part "TICLIB2_ADG904"))
    )
    (comp (ref "U$14")
      (value "TICLIB2_ADG904")
      (footprint "eagle-import:TICLIB2_ADG904_TSSOP")
      (libsource (lib "eagle-import") (part "TICLIB2_ADG904"))
    )
    (comp (ref "U$15")
      (value "TICLIB2_ADG904")
      (footprint "eagle-import:TICLIB2_ADG904_TSSOP")
      (libsource (lib "eagle-import") (part "TICLIB2_ADG904"))
    )
    (comp (ref "U$16")
      (value "TICLIB2_ADG904")
      (footprint "eagle-import:TICLIB2_ADG904_TSSOP")
      (fields (field (name "SPICEPREFIX") "X"))
      (libsource (lib "eagle-import") (part "TICLIB2_ADG904"))
    )
    (comp (ref "C43")
      (value "100pF")
      (footprint "eagle-import:C0603")
      (libsource (lib "eagle-import") (part "C-USC0603"))
    )
    (comp (ref "C44")
      (value "1uF")
      (footprint "eagle-import:C0603")
      (libsource (lib "eagle-import") (part "C-USC0603"))
    )
    (comp (ref "C45")
      (value "100pF/0402")
      (footprint "eagle-import:C0402")
      (libsource (lib "eagle-import") (part "C-USC0402"))
    )
    (comp (ref "C46")
      (value "100pF/0402")
      (footprint "eagle-import:C0402")
      (libsource (lib "eagle-import") (part "C-USC0402"))
    )
    (comp (ref "R79")
      (value "0 0402")
      (footprint "eagle-import:R0402")
      (libsource (lib "eagle-import") (part "R-US_R0402"))
    )
    (comp (ref "R84")
      (value "0 0402")
      (footprint "eagle-import:R0402")
      (libsource (lib "eagle-import") (part "R-US_R0402"))
    )
    (comp (ref "R85")
      (value "100nH")
      (footprint "eagle-import:R0603")
      (libsource (lib "eagle-import") (part "R-US_R0603"))
    )
    (comp (ref "R86")
      (value "22")
      (footprint "eagle-import:R0805")
      (libsource (lib "eagle-import") (part "R-US_R0805"))
    )
    (comp (ref "R93")
      (value "0 0402")
      (footprint "eagle-import:R0402")
      (libsource (lib "eagle-import") (part "R-US_R0402"))
    )
    (comp (ref "R94")
      (value "0 0402")
      (footprint "eagle-import:R0402")
      (libsource (lib "eagle-import") (part "R-US_R0402"))
    )
    (comp (ref "R101")
      (value "0 0402")
      (footprint "eagle-import:R0402")
      (libsource (lib "eagle-import") (part "R-US_R0402"))
    )
    (comp (ref "R102")
      (value "0 0402")
      (footprint "eagle-import:R0402")
      (libsource (lib "eagle-import") (part "R-US_R0402"))
    )
    (comp (ref "U$1")
      (value "MINISMP_PE44970_THRUHOLE")
      (footprint "eagle-import:MINISMP_PE44970_THRU_HOLE")
      (libsource (lib "eagle-import") (part "MINISMP_PE44970_THRUHOLE"))
    )
    (comp (ref "U$3")
      (value "MINISMP_PE44970_THRUHOLE")
      (footprint "eagle-import:MINISMP_PE44970_THRU_HOLE")
      (libsource (lib "eagle-import") (part "MINISMP_PE44970_THRUHOLE"))
    )
    (comp (ref "U$40")
      (value "RF3378_AMPLIFIER")
      (footprint "eagle-import:TO243AA_SOT89")
      (libsource (lib "eagle-import") (part "RF3378_AMPLIFIER"))
    )
    (comp (ref "C33")
      (value "0.1uF0402")
      (footprint "eagle-import:C0402")
      (libsource (lib "eagle-import") (part "C-USC0402"))
    )
    (comp (ref "C34")
      (value "0.1uF0402")
      (footprint "eagle-import:C0402")
      (libsource (lib "eagle-import") (part "C-USC0402"))
    )
    (comp (ref "C35")
      (value "0.1uF0402")
      (footprint "eagle-import:C0402")
      (libsource (lib "eagle-import") (part "C-USC0402"))
    )
    (comp (ref "R49")
      (value "2k 0402")
      (footprint "eagle-import:R0402")
      (libsource (lib "eagle-import") (part "R-US_R0402"))
    )
    (comp (ref "R50")
      (value "2k 0402")
      (footprint "eagle-import:R0402")
      (libsource (lib "eagle-import") (part "R-US_R0402"))
    )
    (comp (ref "R51")
      (value "2k 0402")
      (footprint "eagle-import:R0402")
      (libsource (lib "eagle-import") (part "R-US_R0402"))
    )
    (comp (ref "R52")
      (value "2k 0402")
      (footprint "eagle-import:R0402")
      (libsource (lib "eagle-import") (part "R-US_R0402"))
    )
    (comp (ref "R53")
      (value "2k 0402")
      (footprint "eagle-import:R0402")
      (libsource (lib "eagle-import") (part "R-US_R0402"))
    )
    (comp (ref "R54")
      (value "2k 0402")
      (footprint "eagle-import:R0402")
      (libsource (lib "eagle-import") (part "R-US_R0402"))
    )
    (comp (ref "R55")
      (value "2k 0402")
      (footprint "eagle-import:R0402")
      (libsource (lib "eagle-import") (part "R-US_R0402"))
    )
    (comp (ref "R56")
      (value "2k 0402")
      (footprint "eagle-import:R0402")
      (libsource (lib "eagle-import") (part "R-US_R0402"))
    )
    (comp (ref "R57")
      (value "2k 0402")
      (footprint "eagle-import:R0402")
      (libsource (lib "eagle-import") (part "R-US_R0402"))
    )
    (comp (ref "R58")
      (value "2k 0402")
      (footprint "eagle-import:R0402")
      (libsource (lib "eagle-import") (part "R-US_R0402"))
    )
    (comp (ref "R59")
      (value "2k 0402")
      (footprint "eagle-import:R0402")
      (libsource (lib "eagle-import") (part "R-US_R0402"))
    )
    (comp (ref "R60")
      (value "2k 0402")
      (footprint "eagle-import:R0402")
      (libsource (lib "eagle-import") (part "R-US_R0402"))
    )
    (comp (ref "R61")
      (value "2k 0402")
      (footprint "eagle-import:R0402")
      (libsource (lib "eagle-import") (part "R-US_R0402"))
    )
    (comp (ref "R62")
      (value "2k 0402")
      (footprint "eagle-import:R0402")
      (libsource (lib "eagle-import") (part "R-US_R0402"))
    )
    (comp (ref "R63")
      (value "2k 0402")
      (footprint "eagle-import:R0402")
      (libsource (lib "eagle-import") (part "R-US_R0402"))
    )
    (comp (ref "R64")
      (value "2k 0402")
      (footprint "eagle-import:R0402")
      (libsource (lib "eagle-import") (part "R-US_R0402"))
    )
    (comp (ref "R65")
      (value "2k 0402")
      (footprint "eagle-import:R0402")
      (libsource (lib "eagle-import") (part "R-US_R0402"))
    )
    (comp (ref "R66")
      (value "2k 0402")
      (footprint "eagle-import:R0402")
      (libsource (lib "eagle-import") (part "R-US_R0402"))
    )
    (comp (ref "R67")
      (value "2k 0402")
      (footprint "eagle-import:R0402")
      (libsource (lib "eagle-import") (part "R-US_R0402"))
    )
    (comp (ref "R68")
      (value "2k 0402")
      (footprint "eagle-import:R0402")
      (libsource (lib "eagle-import") (part "R-US_R0402"))
    )
    (comp (ref "R69")
      (value "2k 0402")
      (footprint "eagle-import:R0402")
      (libsource (lib "eagle-import") (part "R-US_R0402"))
    )
    (comp (ref "R70")
      (value "2k 0402")
      (footprint "eagle-import:R0402")
      (libsource (lib "eagle-import") (part "R-US_R0402"))
    )
    (comp (ref "R71")
      (value "2k 0402")
      (footprint "eagle-import:R0402")
      (libsource (lib "eagle-import") (part "R-US_R0402"))
    )
    (comp (ref "R72")
      (value "2k 0402")
      (footprint "eagle-import:R0402")
      (libsource (lib "eagle-import") (part "R-US_R0402"))
    )
    (comp (ref "U7")
      (value "ADG738BRUZ")
      (footprint "eagle-import:RU_16")
      (libsource (lib "eagle-import") (part "ADG738BRUZ"))
    )
    (comp (ref "U8")
      (value "ADG738BRUZ")
      (footprint "eagle-import:RU_16")
      (libsource (lib "eagle-import") (part "ADG738BRUZ"))
    )
    (comp (ref "U9")
      (value "ADG738BRUZ")
      (footprint "eagle-import:RU_16")
      (libsource (lib "eagle-import") (part "ADG738BRUZ"))
    )
    (comp (ref "C30")
      (value "0.1uF0402")
      (footprint "eagle-import:C0402")
      (libsource (lib "eagle-import") (part "C-USC0402"))
    )
    (comp (ref "C31")
      (value "0.1uF0402")
      (footprint "eagle-import:C0402")
      (libsource (lib "eagle-import") (part "C-USC0402"))
    )
    (comp (ref "C32")
      (value "0.1uF0402")
      (footprint "eagle-import:C0402")
      (libsource (lib "eagle-import") (part "C-USC0402"))
    )
    (comp (ref "R4")
      (value "2k 0402")
      (footprint "eagle-import:R0402")
      (libsource (lib "eagle-import") (part "R-US_R0402"))
    )
    (comp (ref "R7")
      (value "2k 0402")
      (footprint "eagle-import:R0402")
      (libsource (lib "eagle-import") (part "R-US_R0402"))
    )
    (comp (ref "R8")
      (value "2k 0402")
      (footprint "eagle-import:R0402")
      (libsource (lib "eagle-import") (part "R-US_R0402"))
    )
    (comp (ref "R29")
      (value "2k 0402")
      (footprint "eagle-import:R0402")
      (libsource (lib "eagle-import") (part "R-US_R0402"))
    )
    (comp (ref "R30")
      (value "2k 0402")
      (footprint "eagle-import:R0402")
      (libsource (lib "eagle-import") (part "R-US_R0402"))
    )
    (comp (ref "R31")
      (value "2k 0402")
      (footprint "eagle-import:R0402")
      (libsource (lib "eagle-import") (part "R-US_R0402"))
    )
    (comp (ref "R32")
      (value "2k 0402")
      (footprint "eagle-import:R0402")
      (libsource (lib "eagle-import") (part "R-US_R0402"))
    )
    (comp (ref "R33")
      (value "2k 0402")
      (footprint "eagle-import:R0402")
      (libsource (lib "eagle-import") (part "R-US_R0402"))
    )
    (comp (ref "R34")
      (value "2k 0402")
      (footprint "eagle-import:R0402")
      (libsource (lib "eagle-import") (part "R-US_R0402"))
    )
    (comp (ref "R35")
      (value "2k 0402")
      (footprint "eagle-import:R0402")
      (libsource (lib "eagle-import") (part "R-US_R0402"))
    )
    (comp (ref "R36")
      (value "2k 0402")
      (footprint "eagle-import:R0402")
      (libsource (lib "eagle-import") (part "R-US_R0402"))
    )
    (comp (ref "R37")
      (value "2k 0402")
      (footprint "eagle-import:R0402")
      (libsource (lib "eagle-import") (part "R-US_R0402"))
    )
    (comp (ref "R38")
      (value "2k 0402")
      (footprint "eagle-import:R0402")
      (libsource (lib "eagle-import") (part "R-US_R0402"))
    )
    (comp (ref "R39")
      (value "2k 0402")
      (footprint "eagle-import:R0402")
      (libsource (lib "eagle-import") (part "R-US_R0402"))
    )
    (comp (ref "R40")
      (value "2k 0402")
      (footprint "eagle-import:R0402")
      (libsource (lib "eagle-import") (part "R-US_R0402"))
    )
    (comp (ref "R41")
      (value "2k 0402")
      (footprint "eagle-import:R0402")
      (libsource (lib "eagle-import") (part "R-US_R0402"))
    )
    (comp (ref "R42")
      (value "2k 0402")
      (footprint "eagle-import:R0402")
      (libsource (lib "eagle-import") (part "R-US_R0402"))
    )
    (comp (ref "R43")
      (value "2k 0402")
      (footprint "eagle-import:R0402")
      (libsource (lib "eagle-import") (part "R-US_R0402"))
    )
    (comp (ref "R44")
      (value "2k 0402")
      (footprint "eagle-import:R0402")
      (libsource (lib "eagle-import") (part "R-US_R0402"))
    )
    (comp (ref "R45")
      (value "2k 0402")
      (footprint "eagle-import:R0402")
      (libsource (lib "eagle-import") (part "R-US_R0402"))
    )
    (comp (ref "R46")
      (value "2k 0402")
      (footprint "eagle-import:R0402")
      (libsource (lib "eagle-import") (part "R-US_R0402"))
    )
    (comp (ref "R47")
      (value "2k 0402")
      (footprint "eagle-import:R0402")
      (libsource (lib "eagle-import") (part "R-US_R0402"))
    )
    (comp (ref "R48")
      (value "2k 0402")
      (footprint "eagle-import:R0402")
      (libsource (lib "eagle-import") (part "R-US_R0402"))
    )
    (comp (ref "U4")
      (value "ADG738BRUZ")
      (footprint "eagle-import:RU_16")
      (libsource (lib "eagle-import") (part "ADG738BRUZ"))
    )
    (comp (ref "U5")
      (value "ADG738BRUZ")
      (footprint "eagle-import:RU_16")
      (libsource (lib "eagle-import") (part "ADG738BRUZ"))
    )
    (comp (ref "U6")
      (value "ADG738BRUZ")
      (footprint "eagle-import:RU_16")
      (libsource (lib "eagle-import") (part "ADG738BRUZ"))
    )
    (comp (ref "C6")
      (value "0.1uF0402")
      (footprint "eagle-import:C0402")
      (libsource (lib "eagle-import") (part "C-USC0402"))
    )
    (comp (ref "C7")
      (value "0.1uF0402")
      (footprint "eagle-import:C0402")
      (libsource (lib "eagle-import") (part "C-USC0402"))
    )
    (comp (ref "C8")
      (value "0.1uF0402")
      (footprint "eagle-import:C0402")
      (libsource (lib "eagle-import") (part "C-USC0402"))
    )
    (comp (ref "C9")
      (value "0.1uF0402")
      (footprint "eagle-import:C0402")
      (libsource (lib "eagle-import") (part "C-USC0402"))
    )
    (comp (ref "C10")
      (value "0.1uF0402")
      (footprint "eagle-import:C0402")
      (libsource (lib "eagle-import") (part "C-USC0402"))
    )
    (comp (ref "U$17")
      (value "FP-BOND-6MIL")
      (footprint "eagle-import:FP_BOND_6MIL")
      (libsource (lib "eagle-import") (part "FP-BOND-6MIL"))
    )
    (comp (ref "U$18")
      (value "TICLIB2_ADG904")
      (footprint "eagle-import:TICLIB2_ADG904_TSSOP")
      (libsource (lib "eagle-import") (part "TICLIB2_ADG904"))
    )
    (comp (ref "U$19")
      (value "TICLIB2_ADG904")
      (footprint "eagle-import:TICLIB2_ADG904_TSSOP")
      (libsource (lib "eagle-import") (part "TICLIB2_ADG904"))
    )
    (comp (ref "U$20")
      (value "TICLIB2_ADG904")
      (footprint "eagle-import:TICLIB2_ADG904_TSSOP")
      (libsource (lib "eagle-import") (part "TICLIB2_ADG904"))
    )
    (comp (ref "U$21")
      (value "TICLIB2_ADG904")
      (footprint "eagle-import:TICLIB2_ADG904_TSSOP")
      (libsource (lib "eagle-import") (part "TICLIB2_ADG904"))
    )
    (comp (ref "U$22")
      (value "TICLIB2_ADG904")
      (footprint "eagle-import:TICLIB2_ADG904_TSSOP")
      (libsource (lib "eagle-import") (part "TICLIB2_ADG904"))
    )
    (comp (ref "C47")
      (value "100pF")
      (footprint "eagle-import:C0402")
      (libsource (lib "eagle-import") (part "C-USC0402"))
    )
    (comp (ref "C48")
      (value "6.8nH")
      (footprint "eagle-import:C0402")
      (libsource (lib "eagle-import") (part "C-USC0402"))
    )
    (comp (ref "C49")
      (value "0.1uF0402")
      (footprint "eagle-import:C0402")
      (libsource (lib "eagle-import") (part "C-USC0402"))
    )
    (comp (ref "C50")
      (value "100pF")
      (footprint "eagle-import:C0402")
      (libsource (lib "eagle-import") (part "C-USC0402"))
    )
    (comp (ref "C74")
      (value "10pF")
      (footprint "eagle-import:C0402")
      (libsource (lib "eagle-import") (part "C-USC0402"))
    )
    (comp (ref "C75")
      (value "100pF")
      (footprint "eagle-import:C0402")
      (libsource (lib "eagle-import") (part "C-USC0402"))
    )
    (comp (ref "C76")
      (value "1000pF")
      (footprint "eagle-import:C0402")
      (libsource (lib "eagle-import") (part "C-USC0402"))
    )
    (comp (ref "R87")
      (value "0 0402")
      (footprint "eagle-import:R0402")
      (libsource (lib "eagle-import") (part "R-US_R0402"))
    )
    (comp (ref "R88")
      (value "10k0402")
      (footprint "eagle-import:R0402")
      (libsource (lib "eagle-import") (part "R-US_R0402"))
    )
    (comp (ref "R89")
      (value "10k0402")
      (footprint "eagle-import:R0402")
      (libsource (lib "eagle-import") (part "R-US_R0402"))
    )
    (comp (ref "R90")
      (value "10k0402")
      (footprint "eagle-import:R0402")
      (libsource (lib "eagle-import") (part "R-US_R0402"))
    )
    (comp (ref "U$42")
      (value "LTC_5564_ENV_DET")
      (footprint "eagle-import:QFN16")
      (libsource (lib "eagle-import") (part "LTC_5564_ENV_DET"))
    )
    (comp (ref "U$43")
      (value "PV36W502C01B00_5KTRIMMER")
      (footprint "eagle-import:PV36W502C01B00_5KTRIMMER")
      (libsource (lib "eagle-import") (part "PV36W502C01B00_5KTRIMMER"))
    )
    (comp (ref "U$50")
      (value "HEADER_0.1''_1X2")
      (footprint "eagle-import:HEADER_0.1''_1X2")
      (libsource (lib "eagle-import") (part "HEADER_0.1''_1X2"))
    )
    (comp (ref "U$51")
      (value "HEADER_0.1''_1X3")
      (footprint "eagle-import:HEADER_0.1''_1X3")
      (libsource (lib "eagle-import") (part "HEADER_0.1''_1X3"))
    )
    (comp (ref "U$52")
      (value "HEADER_0.1''_1X3")
      (footprint "eagle-import:HEADER_0.1''_1X3")
      (libsource (lib "eagle-import") (part "HEADER_0.1''_1X3"))
    )
    (comp (ref "U$53")
      (value "SMA_CONN_SIDE")
      (footprint "eagle-import:SMA_CONN_SIDE")
      (libsource (lib "eagle-import") (part "SMA_CONN_SIDE"))
    )
    (comp (ref "C36")
      (value "100nF")
      (footprint "eagle-import:C0603")
      (libsource (lib "eagle-import") (part "C-USC0603"))
    )
    (comp (ref "C37")
      (value "100nF")
      (footprint "eagle-import:C0603")
      (libsource (lib "eagle-import") (part "C-USC0603"))
    )
    (comp (ref "C38")
      (value "100nF")
      (footprint "eagle-import:C0603")
      (libsource (lib "eagle-import") (part "C-USC0603"))
    )
    (comp (ref "C39")
      (value "0.1uF")
      (footprint "eagle-import:C0603")
      (libsource (lib "eagle-import") (part "C-USC0603"))
    )
    (comp (ref "C40")
      (value "0.01uF")
      (footprint "eagle-import:C0603")
      (libsource (lib "eagle-import") (part "C-USC0603"))
    )
    (comp (ref "R73")
      (value "10k")
      (footprint "eagle-import:R0603")
      (libsource (lib "eagle-import") (part "R-US_R0603"))
    )
    (comp (ref "R74")
      (value "0")
      (footprint "eagle-import:R0603")
      (libsource (lib "eagle-import") (part "R-US_R0603"))
    )
    (comp (ref "R75")
      (value "0")
      (footprint "eagle-import:R0603")
      (libsource (lib "eagle-import") (part "R-US_R0603"))
    )
    (comp (ref "R76")
      (value "0")
      (footprint "eagle-import:R0603")
      (libsource (lib "eagle-import") (part "R-US_R0603"))
    )
    (comp (ref "R77")
      (value "0")
      (footprint "eagle-import:R0603")
      (libsource (lib "eagle-import") (part "R-US_R0603"))
    )
    (comp (ref "R78")
      (value "50")
      (footprint "eagle-import:R0603")
      (libsource (lib "eagle-import") (part "R-US_R0603"))
    )
    (comp (ref "R80")
      (value "0")
      (footprint "eagle-import:R0603")
      (libsource (lib "eagle-import") (part "R-US_R0603"))
    )
    (comp (ref "R81")
      (value "0")
      (footprint "eagle-import:R0603")
      (libsource (lib "eagle-import") (part "R-US_R0603"))
    )
    (comp (ref "U$36")
      (value "RF_SWITCH_SPDT_HMC547LP3")
      (footprint "eagle-import:CP_16_3")
      (libsource (lib "eagle-import") (part "RF_SWITCH_SPDT_HMC547LP3"))
    )
    (comp (ref "U$37")
      (value "ZENER_MMSZ4689-TP")
      (footprint "eagle-import:SOD123")
      (libsource (lib "eagle-import") (part "ZENER_MMSZ4689-TP"))
    )
    (comp (ref "U$44")
      (value "FAIRCHILD_UHS_DUAL_INVERTER_NC7WZ04P6X")
      (footprint "eagle-import:FAIRCHILD_DUAL_INVERTER_NC7WZ04P6X")
      (libsource (lib "eagle-import") (part "FAIRCHILD_UHS_DUAL_INVERTER_NC7WZ04P6X"))
    )
    (comp (ref "C16")
      (value "0.1uF0402")
      (footprint "eagle-import:C0402")
      (libsource (lib "eagle-import") (part "C-USC0402"))
    )
    (comp (ref "C17")
      (value "0.1uF0402")
      (footprint "eagle-import:C0402")
      (libsource (lib "eagle-import") (part "C-USC0402"))
    )
    (comp (ref "C18")
      (value "0.1uF0402")
      (footprint "eagle-import:C0402")
      (libsource (lib "eagle-import") (part "C-USC0402"))
    )
    (comp (ref "C19")
      (value "0.1uF0402")
      (footprint "eagle-import:C0402")
      (libsource (lib "eagle-import") (part "C-USC0402"))
    )
    (comp (ref "C20")
      (value "0.1uF0402")
      (footprint "eagle-import:C0402")
      (libsource (lib "eagle-import") (part "C-USC0402"))
    )
    (comp (ref "U$29")
      (value "FP-BOND-6MIL")
      (footprint "eagle-import:FP_BOND_6MIL")
      (libsource (lib "eagle-import") (part "FP-BOND-6MIL"))
    )
    (comp (ref "U$30")
      (value "TICLIB2_ADG904")
      (footprint "eagle-import:TICLIB2_ADG904_TSSOP")
      (libsource (lib "eagle-import") (part "TICLIB2_ADG904"))
    )
    (comp (ref "U$31")
      (value "TICLIB2_ADG904")
      (footprint "eagle-import:TICLIB2_ADG904_TSSOP")
      (libsource (lib "eagle-import") (part "TICLIB2_ADG904"))
    )
    (comp (ref "U$32")
      (value "TICLIB2_ADG904")
      (footprint "eagle-import:TICLIB2_ADG904_TSSOP")
      (libsource (lib "eagle-import") (part "TICLIB2_ADG904"))
    )
    (comp (ref "U$33")
      (value "TICLIB2_ADG904")
      (footprint "eagle-import:TICLIB2_ADG904_TSSOP")
      (libsource (lib "eagle-import") (part "TICLIB2_ADG904"))
    )
    (comp (ref "U$34")
      (value "TICLIB2_ADG904")
      (footprint "eagle-import:TICLIB2_ADG904_TSSOP")
      (libsource (lib "eagle-import") (part "TICLIB2_ADG904"))
    )
    (comp (ref "C51")
      (value "100uF")
      (footprint "eagle-import:CAP_POL_RADIAL_8MM_3P5MMPAD")
      (libsource (lib "eagle-import") (part "CAP_POL_DEV"))
    )
    (comp (ref "C52")
      (value "2.2uF")
      (footprint "eagle-import:C0603")
      (libsource (lib "eagle-import") (part "C-USC0603"))
    )
    (comp (ref "C53")
      (value "10uF")
      (footprint "eagle-import:C1206")
      (libsource (lib "eagle-import") (part "C-USC1206"))
    )
    (comp (ref "C54")
      (value "0.1uF")
      (footprint "eagle-import:C0603")
      (libsource (lib "eagle-import") (part "C-USC0603"))
    )
    (comp (ref "C55")
      (value "100uF")
      (footprint "eagle-import:CAP_POL_RADIAL_8MM_3P5MMPAD")
      (libsource (lib "eagle-import") (part "CAP_POL_DEV"))
    )
    (comp (ref "C56")
      (value "2.2uF")
      (footprint "eagle-import:C0603")
      (libsource (lib "eagle-import") (part "C-USC0603"))
    )
    (comp (ref "C57")
      (value "10uF")
      (footprint "eagle-import:C1206")
      (libsource (lib "eagle-import") (part "C-USC1206"))
    )
    (comp (ref "C58")
      (value "0.1uF")
      (footprint "eagle-import:C0603")
      (libsource (lib "eagle-import") (part "C-USC0603"))
    )
    (comp (ref "C59")
      (value "100uF")
      (footprint "eagle-import:CAP_POL_RADIAL_8MM_3P5MMPAD")
      (libsource (lib "eagle-import") (part "CAP_POL_DEV"))
    )
    (comp (ref "C60")
      (value "2.2uF")
      (footprint "eagle-import:C0603")
      (libsource (lib "eagle-import") (part "C-USC0603"))
    )
    (comp (ref "C61")
      (value "10uF")
      (footprint "eagle-import:C1206")
      (libsource (lib "eagle-import") (part "C-USC1206"))
    )
    (comp (ref "C62")
      (value "100uF")
      (footprint "eagle-import:CAP_POL_RADIAL_8MM_3P5MMPAD")
      (libsource (lib "eagle-import") (part "CAP_POL_DEV"))
    )
    (comp (ref "C63")
      (value "2.2uF")
      (footprint "eagle-import:C0603")
      (libsource (lib "eagle-import") (part "C-USC0603"))
    )
    (comp (ref "C64")
      (value "10uF")
      (footprint "eagle-import:C1206")
      (libsource (lib "eagle-import") (part "C-USC1206"))
    )
    (comp (ref "C65")
      (value "0.1uF")
      (footprint "eagle-import:C0603")
      (libsource (lib "eagle-import") (part "C-USC0603"))
    )
    (comp (ref "C66")
      (value "0.1uF")
      (footprint "eagle-import:C0603")
      (libsource (lib "eagle-import") (part "C-USC0603"))
    )
    (comp (ref "C67")
      (value "100uF")
      (footprint "eagle-import:CAP_POL_RADIAL_8MM_3P5MMPAD")
      (libsource (lib "eagle-import") (part "CAP_POL_DEV"))
    )
    (comp (ref "C68")
      (value "2.2uF")
      (footprint "eagle-import:C0603")
      (libsource (lib "eagle-import") (part "C-USC0603"))
    )
    (comp (ref "C69")
      (value "10uF")
      (footprint "eagle-import:C1206")
      (libsource (lib "eagle-import") (part "C-USC1206"))
    )
    (comp (ref "C70")
      (value "0.1uF")
      (footprint "eagle-import:C0603")
      (libsource (lib "eagle-import") (part "C-USC0603"))
    )
    (comp (ref "U$11")
      (value "DELTRON_BANANA")
      (footprint "eagle-import:DELTRON_BANANA")
      (libsource (lib "eagle-import") (part "DELTRON_BANANA"))
    )
    (comp (ref "U$45")
      (value "DELTRON_BANANA")
      (footprint "eagle-import:DELTRON_BANANA")
      (libsource (lib "eagle-import") (part "DELTRON_BANANA"))
    )
    (comp (ref "U$55")
      (value "DELTRON_BANANA")
      (footprint "eagle-import:DELTRON_BANANA")
      (libsource (lib "eagle-import") (part "DELTRON_BANANA"))
    )
    (comp (ref "U$56")
      (value "DELTRON_BANANA")
      (footprint "eagle-import:DELTRON_BANANA")
      (libsource (lib "eagle-import") (part "DELTRON_BANANA"))
    )
    (comp (ref "U$57")
      (value "DELTRON_BANANA")
      (footprint "eagle-import:DELTRON_BANANA")
      (libsource (lib "eagle-import") (part "DELTRON_BANANA"))
    )
    (comp (ref "U$58")
      (value "DELTRON_BANANA")
      (footprint "eagle-import:DELTRON_BANANA")
      (libsource (lib "eagle-import") (part "DELTRON_BANANA"))
    )
    (comp (ref "U$59")
      (value "DELTRON_BANANA")
      (footprint "eagle-import:DELTRON_BANANA")
      (libsource (lib "eagle-import") (part "DELTRON_BANANA"))
    )
    (comp (ref "U$4")
      (value "VHDCI_DIGILENT_V1")
      (footprint "eagle-import:VHCDI_DIGILENT_V1")
      (libsource (lib "eagle-import") (part "VHDCI_DIGILENT_V1"))
    )
    (comp (ref "C11")
      (value "0.1uF0402")
      (footprint "eagle-import:C0402")
      (libsource (lib "eagle-import") (part "C-USC0402"))
    )
    (comp (ref "C12")
      (value "0.1uF0402")
      (footprint "eagle-import:C0402")
      (libsource (lib "eagle-import") (part "C-USC0402"))
    )
    (comp (ref "C13")
      (value "0.1uF0402")
      (footprint "eagle-import:C0402")
      (libsource (lib "eagle-import") (part "C-USC0402"))
    )
    (comp (ref "C14")
      (value "0.1uF0402")
      (footprint "eagle-import:C0402")
      (libsource (lib "eagle-import") (part "C-USC0402"))
    )
    (comp (ref "C15")
      (value "0.1uF0402")
      (footprint "eagle-import:C0402")
      (libsource (lib "eagle-import") (part "C-USC0402"))
    )
    (comp (ref "U$23")
      (value "FP-BOND-6MIL")
      (footprint "eagle-import:FP_BOND_6MIL")
      (libsource (lib "eagle-import") (part "FP-BOND-6MIL"))
    )
    (comp (ref "U$24")
      (value "TICLIB2_ADG904")
      (footprint "eagle-import:TICLIB2_ADG904_TSSOP")
      (libsource (lib "eagle-import") (part "TICLIB2_ADG904"))
    )
    (comp (ref "U$25")
      (value "TICLIB2_ADG904")
      (footprint "eagle-import:TICLIB2_ADG904_TSSOP")
      (libsource (lib "eagle-import") (part "TICLIB2_ADG904"))
    )
    (comp (ref "U$26")
      (value "TICLIB2_ADG904")
      (footprint "eagle-import:TICLIB2_ADG904_TSSOP")
      (libsource (lib "eagle-import") (part "TICLIB2_ADG904"))
    )
    (comp (ref "U$27")
      (value "TICLIB2_ADG904")
      (footprint "eagle-import:TICLIB2_ADG904_TSSOP")
      (libsource (lib "eagle-import") (part "TICLIB2_ADG904"))
    )
    (comp (ref "U$28")
      (value "TICLIB2_ADG904")
      (footprint "eagle-import:TICLIB2_ADG904_TSSOP")
      (libsource (lib "eagle-import") (part "TICLIB2_ADG904"))
    )
    (comp (ref "C41")
      (value "0.1uF")
      (footprint "eagle-import:C0603")
      (libsource (lib "eagle-import") (part "C-USC0603"))
    )
    (comp (ref "C42")
      (value "0.1uF0402")
      (footprint "eagle-import:C0402")
      (libsource (lib "eagle-import") (part "C-USC0402"))
    )
    (comp (ref "C71")
      (value "0.1uF")
      (footprint "eagle-import:C0603")
      (libsource (lib "eagle-import") (part "C-USC0603"))
    )
    (comp (ref "C72")
      (value "2.2uF")
      (footprint "eagle-import:C0603")
      (libsource (lib "eagle-import") (part "C-USC0603"))
    )
    (comp (ref "C73")
      (value "2.2uF")
      (footprint "eagle-import:C0603")
      (libsource (lib "eagle-import") (part "C-USC0603"))
    )
    (comp (ref "R82")
      (value "0 0402")
      (footprint "eagle-import:R0402")
      (libsource (lib "eagle-import") (part "R-US_R0402"))
    )
    (comp (ref "R83")
      (value "0 0402")
      (footprint "eagle-import:R0402")
      (libsource (lib "eagle-import") (part "R-US_R0402"))
    )
    (comp (ref "R97")
      (value "FERRITE")
      (footprint "eagle-import:R0603")
      (libsource (lib "eagle-import") (part "R-US_R0603"))
    )
    (comp (ref "U$5")
      (value "MINISMP_PE44970_THRUHOLE")
      (footprint "eagle-import:MINISMP_PE44970_THRU_HOLE")
      (libsource (lib "eagle-import") (part "MINISMP_PE44970_THRUHOLE"))
    )
    (comp (ref "U$46")
      (value "CVCO55BE-1000-1500_VCO")
      (footprint "eagle-import:CVCO55BE-1000-1500_VCO")
      (libsource (lib "eagle-import") (part "CVCO55BE-1000-1500_VCO"))
    )
    (comp (ref "U$47")
      (value "PV36W502C01B00_5KTRIMMER")
      (footprint "eagle-import:PV36W502C01B00_5KTRIMMER")
      (libsource (lib "eagle-import") (part "PV36W502C01B00_5KTRIMMER"))
    )
    (comp (ref "U$48")
      (value "HEADER_0.1''_1X2")
      (footprint "eagle-import:HEADER_0.1''_1X2")
      (libsource (lib "eagle-import") (part "HEADER_0.1''_1X2"))
    )
  )
  (nets
    (net (code "1") (name "+3V3") (class "Default")
      (node (ref "C22") (pin "1") (pinfunction "1_1") (pintype "passive"))
      (node (ref "C23") (pin "1") (pinfunction "1_1") (pintype "passive"))
      (node (ref "C24") (pin "1") (pinfunction "1_1") (pintype "passive"))
      (node (ref "C30") (pin "1") (pinfunction "1_1") (pintype "passive"))
      (node (ref "C31") (pin "1") (pinfunction "1_1") (pintype "passive"))
      (node (ref "C32") (pin "1") (pinfunction "1_1") (pintype "passive"))
      (node (ref "C33") (pin "1") (pinfunction "1_1") (pintype "passive"))
      (node (ref "C34") (pin "1") (pinfunction "1_1") (pintype "passive"))
      (node (ref "C35") (pin "1") (pinfunction "1_1") (pintype "passive"))
      (node (ref "C55") (pin "PIN+") (pinfunction "PIN+_PIN+") (pintype "passive"))
      (node (ref "C56") (pin "1") (pinfunction "1_1") (pintype "passive"))
      (node (ref "C57") (pin "1") (pinfunction "1_1") (pintype "passive"))
      (node (ref "C58") (pin "1") (pinfunction "1_1") (pintype "passive"))
      (node (ref "R1") (pin "2") (pinfunction "2_2") (pintype "passive"))
      (node (ref "R2") (pin "2") (pinfunction "2_2") (pintype "passive"))
      (node (ref "R3") (pin "2") (pinfunction "2_2") (pintype "passive"))
      (node (ref "R4") (pin "2") (pinfunction "2_2") (pintype "passive"))
      (node (ref "R49") (pin "2") (pinfunction "2_2") (pintype "passive"))
      (node (ref "R50") (pin "2") (pinfunction "2_2") (pintype "passive"))
      (node (ref "R51") (pin "2") (pinfunction "2_2") (pintype "passive"))
      (node (ref "R7") (pin "2") (pinfunction "2_2") (pintype "passive"))
      (node (ref "R72") (pin "2") (pinfunction "2_2") (pintype "passive"))
      (node (ref "R8") (pin "2") (pinfunction "2_2") (pintype "passive"))
      (node (ref "U$57") (pin "A") (pinfunction "A_A") (pintype "bidirectional"))
      (node (ref "U$57") (pin "B") (pinfunction "B_B") (pintype "bidirectional"))
      (node (ref "U1") (pin "13") (pinfunction "VDD_13") (pintype "power_in"))
      (node (ref "U2") (pin "13") (pinfunction "VDD_13") (pintype "power_in"))
      (node (ref "U3") (pin "13") (pinfunction "VDD_13") (pintype "power_in"))
      (node (ref "U4") (pin "13") (pinfunction "VDD_13") (pintype "power_in"))
      (node (ref "U5") (pin "13") (pinfunction "VDD_13") (pintype "power_in"))
      (node (ref "U6") (pin "13") (pinfunction "VDD_13") (pintype "power_in"))
      (node (ref "U7") (pin "13") (pinfunction "VDD_13") (pintype "power_in"))
      (node (ref "U8") (pin "13") (pinfunction "VDD_13") (pintype "power_in"))
      (node (ref "U9") (pin "13") (pinfunction "VDD_13") (pintype "power_in"))
    )
    (net (code "2") (name "+5V") (class "Default")
      (node (ref "C26") (pin "1") (pinfunction "1_1") (pintype "passive"))
      (node (ref "C27") (pin "1") (pinfunction "1_1") (pintype "passive"))
      (node (ref "C43") (pin "1") (pinfunction "1_1") (pintype "passive"))
      (node (ref "C44") (pin "1") (pinfunction "1_1") (pintype "passive"))
      (node (ref "C51") (pin "PIN+") (pinfunction "PIN+_PIN+") (pintype "passive"))
      (node (ref "C52") (pin "1") (pinfunction "1_1") (pintype "passive"))
      (node (ref "C53") (pin "1") (pinfunction "1_1") (pintype "passive"))
      (node (ref "C54") (pin "1") (pinfunction "1_1") (pintype "passive"))
      (node (ref "C74") (pin "1") (pinfunction "1_1") (pintype "passive"))
      (node (ref "C75") (pin "1") (pinfunction "1_1") (pintype "passive"))
      (node (ref "C76") (pin "1") (pinfunction "1_1") (pintype "passive"))
      (node (ref "R6") (pin "2") (pinfunction "2_2") (pintype "passive"))
      (node (ref "R86") (pin "2") (pinfunction "2_2") (pintype "passive"))
      (node (ref "U$42") (pin "P$11") (pinfunction "11_VCCP_P$11") (pintype "bidirectional"))
      (node (ref "U$42") (pin "P$12") (pinfunction "12_VCCA_P$12") (pintype "bidirectional"))
      (node (ref "U$42") (pin "P$15") (pinfunction "15_VCCRF_P$15") (pintype "bidirectional"))
      (node (ref "U$43") (pin "1") (pinfunction "1_1") (pintype "bidirectional"))
      (node (ref "U$47") (pin "1") (pinfunction "1_1") (pintype "bidirectional"))
      (node (ref "U$51") (pin "1") (pinfunction "P$1_1") (pintype "bidirectional"))
      (node (ref "U$52") (pin "1") (pinfunction "P$1_1") (pintype "bidirectional"))
      (node (ref "U$56") (pin "A") (pinfunction "A_A") (pintype "bidirectional"))
      (node (ref "U$56") (pin "B") (pinfunction "B_B") (pintype "bidirectional"))
    )
    (net (code "3") (name "-5V") (class "Default")
      (node (ref "C39") (pin "2") (pinfunction "2_2") (pintype "passive"))
      (node (ref "C40") (pin "2") (pinfunction "2_2") (pintype "passive"))
      (node (ref "C62") (pin "PIN-") (pinfunction "PIN-_PIN-") (pintype "passive"))
      (node (ref "C63") (pin "2") (pinfunction "2_2") (pintype "passive"))
      (node (ref "C64") (pin "2") (pinfunction "2_2") (pintype "passive"))
      (node (ref "C65") (pin "2") (pinfunction "2_2") (pintype "passive"))
      (node (ref "R73") (pin "2") (pinfunction "2_2") (pintype "passive"))
      (node (ref "U$44") (pin "2") (pinfunction "GND_2") (pintype "bidirectional"))
      (node (ref "U$45") (pin "A") (pinfunction "A_A") (pintype "bidirectional"))
      (node (ref "U$45") (pin "B") (pinfunction "B_B") (pintype "bidirectional"))
    )
    (net (code "4") (name "A0_1_1") (class "Default")
      (node (ref "R9") (pin "2") (pinfunction "2_2") (pintype "passive"))
      (node (ref "U$8") (pin "P$20") (pinfunction "A0_P$20") (pintype "bidirectional"))
      (node (ref "U1") (pin "9") (pinfunction "S8_9") (pintype "passive"))
    )
    (net (code "5") (name "A0_1_2") (class "Default")
      (node (ref "R10") (pin "2") (pinfunction "2_2") (pintype "passive"))
      (node (ref "U$13") (pin "P$20") (pinfunction "A0_P$20") (pintype "bidirectional"))
      (node (ref "U1") (pin "10") (pinfunction "S7_10") (pintype "passive"))
    )
    (net (code "6") (name "A0_1_3") (class "Default")
      (node (ref "R11") (pin "2") (pinfunction "2_2") (pintype "passive"))
      (node (ref "U$14") (pin "P$20") (pinfunction "A0_P$20") (pintype "bidirectional"))
      (node (ref "U1") (pin "11") (pinfunction "S6_11") (pintype "passive"))
    )
    (net (code "7") (name "A0_1_4") (class "Default")
      (node (ref "R12") (pin "2") (pinfunction "2_2") (pintype "passive"))
      (node (ref "U$15") (pin "P$20") (pinfunction "A0_P$20") (pintype "bidirectional"))
      (node (ref "U1") (pin "12") (pinfunction "S5_12") (pintype "passive"))
    )
    (net (code "8") (name "A0_1_5") (class "Default")
      (node (ref "R13") (pin "2") (pinfunction "2_2") (pintype "passive"))
      (node (ref "U$18") (pin "P$20") (pinfunction "A0_P$20") (pintype "bidirectional"))
      (node (ref "U1") (pin "7") (pinfunction "S4_7") (pintype "passive"))
    )
    (net (code "9") (name "A0_1_6") (class "Default")
      (node (ref "R14") (pin "2") (pinfunction "2_2") (pintype "passive"))
      (node (ref "U$19") (pin "P$20") (pinfunction "A0_P$20") (pintype "bidirectional"))
      (node (ref "U1") (pin "6") (pinfunction "S3_6") (pintype "passive"))
    )
    (net (code "10") (name "A0_1_7") (class "Default")
      (node (ref "R15") (pin "2") (pinfunction "2_2") (pintype "passive"))
      (node (ref "U$20") (pin "P$20") (pinfunction "A0_P$20") (pintype "bidirectional"))
      (node (ref "U1") (pin "5") (pinfunction "S2_5") (pintype "passive"))
    )
    (net (code "11") (name "A0_1_8") (class "Default")
      (node (ref "R16") (pin "2") (pinfunction "2_2") (pintype "passive"))
      (node (ref "U$21") (pin "P$20") (pinfunction "A0_P$20") (pintype "bidirectional"))
      (node (ref "U1") (pin "4") (pinfunction "S1_4") (pintype "passive"))
    )
    (net (code "12") (name "A0_1_9") (class "Default")
      (node (ref "R17") (pin "2") (pinfunction "2_2") (pintype "passive"))
      (node (ref "U$24") (pin "P$20") (pinfunction "A0_P$20") (pintype "bidirectional"))
      (node (ref "U2") (pin "9") (pinfunction "S8_9") (pintype "passive"))
    )
    (net (code "13") (name "A0_1_10") (class "Default")
      (node (ref "R18") (pin "2") (pinfunction "2_2") (pintype "passive"))
      (node (ref "U$25") (pin "P$20") (pinfunction "A0_P$20") (pintype "bidirectional"))
      (node (ref "U2") (pin "10") (pinfunction "S7_10") (pintype "passive"))
    )
    (net (code "14") (name "A0_1_11") (class "Default")
      (node (ref "R19") (pin "2") (pinfunction "2_2") (pintype "passive"))
      (node (ref "U$26") (pin "P$20") (pinfunction "A0_P$20") (pintype "bidirectional"))
      (node (ref "U2") (pin "11") (pinfunction "S6_11") (pintype "passive"))
    )
    (net (code "15") (name "A0_1_12") (class "Default")
      (node (ref "R20") (pin "2") (pinfunction "2_2") (pintype "passive"))
      (node (ref "U$27") (pin "P$20") (pinfunction "A0_P$20") (pintype "bidirectional"))
      (node (ref "U2") (pin "12") (pinfunction "S5_12") (pintype "passive"))
    )
    (net (code "16") (name "A0_1_13") (class "Default")
      (node (ref "R21") (pin "2") (pinfunction "2_2") (pintype "passive"))
      (node (ref "U$30") (pin "P$20") (pinfunction "A0_P$20") (pintype "bidirectional"))
      (node (ref "U2") (pin "7") (pinfunction "S4_7") (pintype "passive"))
    )
    (net (code "17") (name "A0_1_14") (class "Default")
      (node (ref "R22") (pin "2") (pinfunction "2_2") (pintype "passive"))
      (node (ref "U$31") (pin "P$20") (pinfunction "A0_P$20") (pintype "bidirectional"))
      (node (ref "U2") (pin "6") (pinfunction "S3_6") (pintype "passive"))
    )
    (net (code "18") (name "A0_1_15") (class "Default")
      (node (ref "R23") (pin "2") (pinfunction "2_2") (pintype "passive"))
      (node (ref "U$32") (pin "P$20") (pinfunction "A0_P$20") (pintype "bidirectional"))
      (node (ref "U2") (pin "5") (pinfunction "S2_5") (pintype "passive"))
    )
    (net (code "19") (name "A0_1_16") (class "Default")
      (node (ref "R24") (pin "2") (pinfunction "2_2") (pintype "passive"))
      (node (ref "U$33") (pin "P$20") (pinfunction "A0_P$20") (pintype "bidirectional"))
      (node (ref "U2") (pin "4") (pinfunction "S1_4") (pintype "passive"))
    )
    (net (code "20") (name "A0_2_1") (class "Default")
      (node (ref "R25") (pin "2") (pinfunction "2_2") (pintype "passive"))
      (node (ref "U$16") (pin "P$20") (pinfunction "A0_P$20") (pintype "bidirectional"))
      (node (ref "U3") (pin "7") (pinfunction "S4_7") (pintype "passive"))
    )
    (net (code "21") (name "A0_2_2") (class "Default")
      (node (ref "R26") (pin "2") (pinfunction "2_2") (pintype "passive"))
      (node (ref "U$22") (pin "P$20") (pinfunction "A0_P$20") (pintype "bidirectional"))
      (node (ref "U3") (pin "6") (pinfunction "S3_6") (pintype "passive"))
    )
    (net (code "22") (name "A0_2_3") (class "Default")
      (node (ref "R27") (pin "2") (pinfunction "2_2") (pintype "passive"))
      (node (ref "U$28") (pin "P$20") (pinfunction "A0_P$20") (pintype "bidirectional"))
      (node (ref "U3") (pin "5") (pinfunction "S2_5") (pintype "passive"))
    )
    (net (code "23") (name "A0_2_4") (class "Default")
      (node (ref "R28") (pin "2") (pinfunction "2_2") (pintype "passive"))
      (node (ref "U$34") (pin "P$20") (pinfunction "A0_P$20") (pintype "bidirectional"))
      (node (ref "U3") (pin "4") (pinfunction "S1_4") (pintype "passive"))
    )
    (net (code "24") (name "A0_3_1") (class "Default")
      (node (ref "R99") (pin "2") (pinfunction "2_2") (pintype "passive"))
      (node (ref "U$35") (pin "P$20") (pinfunction "A0_P$20") (pintype "bidirectional"))
      (node (ref "U$4") (pin "P29") (pinfunction "P$29_P29") (pintype "bidirectional"))
    )
    (net (code "25") (name "A1_1_1") (class "Default")
      (node (ref "R29") (pin "2") (pinfunction "2_2") (pintype "passive"))
      (node (ref "U$8") (pin "P$19") (pinfunction "A1_P$19") (pintype "bidirectional"))
      (node (ref "U4") (pin "9") (pinfunction "S8_9") (pintype "passive"))
    )
    (net (code "26") (name "A1_1_2") (class "Default")
      (node (ref "R30") (pin "2") (pinfunction "2_2") (pintype "passive"))
      (node (ref "U$13") (pin "P$19") (pinfunction "A1_P$19") (pintype "bidirectional"))
      (node (ref "U4") (pin "10") (pinfunction "S7_10") (pintype "passive"))
    )
    (net (code "27") (name "A1_1_3") (class "Default")
      (node (ref "R31") (pin "2") (pinfunction "2_2") (pintype "passive"))
      (node (ref "U$14") (pin "P$19") (pinfunction "A1_P$19") (pintype "bidirectional"))
      (node (ref "U4") (pin "11") (pinfunction "S6_11") (pintype "passive"))
    )
    (net (code "28") (name "A1_1_4") (class "Default")
      (node (ref "R32") (pin "2") (pinfunction "2_2") (pintype "passive"))
      (node (ref "U$15") (pin "P$19") (pinfunction "A1_P$19") (pintype "bidirectional"))
      (node (ref "U4") (pin "12") (pinfunction "S5_12") (pintype "passive"))
    )
    (net (code "29") (name "A1_1_5") (class "Default")
      (node (ref "R33") (pin "2") (pinfunction "2_2") (pintype "passive"))
      (node (ref "U$18") (pin "P$19") (pinfunction "A1_P$19") (pintype "bidirectional"))
      (node (ref "U4") (pin "7") (pinfunction "S4_7") (pintype "passive"))
    )
    (net (code "30") (name "A1_1_6") (class "Default")
      (node (ref "R34") (pin "2") (pinfunction "2_2") (pintype "passive"))
      (node (ref "U$19") (pin "P$19") (pinfunction "A1_P$19") (pintype "bidirectional"))
      (node (ref "U4") (pin "6") (pinfunction "S3_6") (pintype "passive"))
    )
    (net (code "31") (name "A1_1_7") (class "Default")
      (node (ref "R35") (pin "2") (pinfunction "2_2") (pintype "passive"))
      (node (ref "U$20") (pin "P$19") (pinfunction "A1_P$19") (pintype "bidirectional"))
      (node (ref "U4") (pin "5") (pinfunction "S2_5") (pintype "passive"))
    )
    (net (code "32") (name "A1_1_8") (class "Default")
      (node (ref "R36") (pin "2") (pinfunction "2_2") (pintype "passive"))
      (node (ref "U$21") (pin "P$19") (pinfunction "A1_P$19") (pintype "bidirectional"))
      (node (ref "U4") (pin "4") (pinfunction "S1_4") (pintype "passive"))
    )
    (net (code "33") (name "A1_1_9") (class "Default")
      (node (ref "R37") (pin "2") (pinfunction "2_2") (pintype "passive"))
      (node (ref "U$24") (pin "P$19") (pinfunction "A1_P$19") (pintype "bidirectional"))
      (node (ref "U5") (pin "9") (pinfunction "S8_9") (pintype "passive"))
    )
    (net (code "34") (name "A1_1_10") (class "Default")
      (node (ref "R38") (pin "2") (pinfunction "2_2") (pintype "passive"))
      (node (ref "U$25") (pin "P$19") (pinfunction "A1_P$19") (pintype "bidirectional"))
      (node (ref "U5") (pin "10") (pinfunction "S7_10") (pintype "passive"))
    )
    (net (code "35") (name "A1_1_11") (class "Default")
      (node (ref "R39") (pin "2") (pinfunction "2_2") (pintype "passive"))
      (node (ref "U$26") (pin "P$19") (pinfunction "A1_P$19") (pintype "bidirectional"))
      (node (ref "U5") (pin "11") (pinfunction "S6_11") (pintype "passive"))
    )
    (net (code "36") (name "A1_1_12") (class "Default")
      (node (ref "R40") (pin "2") (pinfunction "2_2") (pintype "passive"))
      (node (ref "U$27") (pin "P$19") (pinfunction "A1_P$19") (pintype "bidirectional"))
      (node (ref "U5") (pin "12") (pinfunction "S5_12") (pintype "passive"))
    )
    (net (code "37") (name "A1_1_13") (class "Default")
      (node (ref "R41") (pin "2") (pinfunction "2_2") (pintype "passive"))
      (node (ref "U$30") (pin "P$19") (pinfunction "A1_P$19") (pintype "bidirectional"))
      (node (ref "U5") (pin "7") (pinfunction "S4_7") (pintype "passive"))
    )
    (net (code "38") (name "A1_1_14") (class "Default")
      (node (ref "R42") (pin "2") (pinfunction "2_2") (pintype "passive"))
      (node (ref "U$31") (pin "P$19") (pinfunction "A1_P$19") (pintype "bidirectional"))
      (node (ref "U5") (pin "6") (pinfunction "S3_6") (pintype "passive"))
    )
    (net (code "39") (name "A1_1_15") (class "Default")
      (node (ref "R43") (pin "2") (pinfunction "2_2") (pintype "passive"))
      (node (ref "U$32") (pin "P$19") (pinfunction "A1_P$19") (pintype "bidirectional"))
      (node (ref "U5") (pin "5") (pinfunction "S2_5") (pintype "passive"))
    )
    (net (code "40") (name "A1_1_16") (class "Default")
      (node (ref "R44") (pin "2") (pinfunction "2_2") (pintype "passive"))
      (node (ref "U$33") (pin "P$19") (pinfunction "A1_P$19") (pintype "bidirectional"))
      (node (ref "U5") (pin "4") (pinfunction "S1_4") (pintype "passive"))
    )
    (net (code "41") (name "A1_2_1") (class "Default")
      (node (ref "R45") (pin "2") (pinfunction "2_2") (pintype "passive"))
      (node (ref "U$16") (pin "P$19") (pinfunction "A1_P$19") (pintype "bidirectional"))
      (node (ref "U6") (pin "7") (pinfunction "S4_7") (pintype "passive"))
    )
    (net (code "42") (name "A1_2_2") (class "Default")
      (node (ref "R46") (pin "2") (pinfunction "2_2") (pintype "passive"))
      (node (ref "U$22") (pin "P$19") (pinfunction "A1_P$19") (pintype "bidirectional"))
      (node (ref "U6") (pin "6") (pinfunction "S3_6") (pintype "passive"))
    )
    (net (code "43") (name "A1_2_3") (class "Default")
      (node (ref "R47") (pin "2") (pinfunction "2_2") (pintype "passive"))
      (node (ref "U$28") (pin "P$19") (pinfunction "A1_P$19") (pintype "bidirectional"))
      (node (ref "U6") (pin "5") (pinfunction "S2_5") (pintype "passive"))
    )
    (net (code "44") (name "A1_2_4") (class "Default")
      (node (ref "R48") (pin "2") (pinfunction "2_2") (pintype "passive"))
      (node (ref "U$34") (pin "P$19") (pinfunction "A1_P$19") (pintype "bidirectional"))
      (node (ref "U6") (pin "4") (pinfunction "S1_4") (pintype "passive"))
    )
    (net (code "45") (name "A1_3_1") (class "Default")
      (node (ref "R100") (pin "2") (pinfunction "2_2") (pintype "passive"))
      (node (ref "U$35") (pin "P$19") (pinfunction "A1_P$19") (pintype "bidirectional"))
      (node (ref "U$4") (pin "P31") (pinfunction "P$31_P31") (pintype "bidirectional"))
    )
    (net (code "46") (name "CDRIVE") (class "Default")
      (node (ref "U$4") (pin "P34") (pinfunction "P$34_P34") (pintype "bidirectional"))
      (node (ref "U$9") (pin "P$2") (pinfunction "CTRL_P$2") (pintype "bidirectional"))
    )
    (net (code "47") (name "CS1") (class "Default")
      (node (ref "U$4") (pin "P35") (pinfunction "P$35_P35") (pintype "bidirectional"))
      (node (ref "U1") (pin "16") (pinfunction "SYNC*_16") (pintype "passive"))
    )
    (net (code "48") (name "CS2") (class "Default")
      (node (ref "U$4") (pin "P37") (pinfunction "P$37_P37") (pintype "bidirectional"))
      (node (ref "U2") (pin "16") (pinfunction "SYNC*_16") (pintype "passive"))
    )
    (net (code "49") (name "CS3") (class "Default")
      (node (ref "U$4") (pin "P38") (pinfunction "P$38_P38") (pintype "bidirectional"))
      (node (ref "U3") (pin "16") (pinfunction "SYNC*_16") (pintype "passive"))
    )
    (net (code "50") (name "CS4") (class "Default")
      (node (ref "U$4") (pin "P40") (pinfunction "P$40_P40") (pintype "bidirectional"))
      (node (ref "U4") (pin "16") (pinfunction "SYNC*_16") (pintype "passive"))
    )
    (net (code "51") (name "CS5") (class "Default")
      (node (ref "U$4") (pin "P41") (pinfunction "P$41_P41") (pintype "bidirectional"))
      (node (ref "U5") (pin "16") (pinfunction "SYNC*_16") (pintype "passive"))
    )
    (net (code "52") (name "CS6") (class "Default")
      (node (ref "U$4") (pin "P43") (pinfunction "P$43_P43") (pintype "bidirectional"))
      (node (ref "U6") (pin "16") (pinfunction "SYNC*_16") (pintype "passive"))
    )
    (net (code "53") (name "CS7") (class "Default")
      (node (ref "U$4") (pin "P44") (pinfunction "P$44_P44") (pintype "bidirectional"))
      (node (ref "U7") (pin "16") (pinfunction "SYNC*_16") (pintype "passive"))
    )
    (net (code "54") (name "CS8") (class "Default")
      (node (ref "U$4") (pin "P46") (pinfunction "P$46_P46") (pintype "bidirectional"))
      (node (ref "U8") (pin "16") (pinfunction "SYNC*_16") (pintype "passive"))
    )
    (net (code "55") (name "CS9") (class "Default")
      (node (ref "U$4") (pin "P47") (pinfunction "P$47_P47") (pintype "bidirectional"))
      (node (ref "U9") (pin "16") (pinfunction "SYNC*_16") (pintype "passive"))
    )
    (net (code "56") (name "ENB_1_1") (class "Default")
      (node (ref "R52") (pin "2") (pinfunction "2_2") (pintype "passive"))
      (node (ref "U$8") (pin "P$1") (pinfunction "EN_BAR_P$1") (pintype "bidirectional"))
      (node (ref "U7") (pin "9") (pinfunction "S8_9") (pintype "passive"))
    )
    (net (code "57") (name "ENB_1_2") (class "Default")
      (node (ref "R53") (pin "2") (pinfunction "2_2") (pintype "passive"))
      (node (ref "U$13") (pin "P$1") (pinfunction "EN_BAR_P$1") (pintype "bidirectional"))
      (node (ref "U7") (pin "10") (pinfunction "S7_10") (pintype "passive"))
    )
    (net (code "58") (name "ENB_1_3") (class "Default")
      (node (ref "R54") (pin "2") (pinfunction "2_2") (pintype "passive"))
      (node (ref "U$14") (pin "P$1") (pinfunction "EN_BAR_P$1") (pintype "bidirectional"))
      (node (ref "U7") (pin "11") (pinfunction "S6_11") (pintype "passive"))
    )
    (net (code "59") (name "ENB_1_4") (class "Default")
      (node (ref "R55") (pin "2") (pinfunction "2_2") (pintype "passive"))
      (node (ref "U$15") (pin "P$1") (pinfunction "EN_BAR_P$1") (pintype "bidirectional"))
      (node (ref "U7") (pin "12") (pinfunction "S5_12") (pintype "passive"))
    )
    (net (code "60") (name "ENB_1_5") (class "Default")
      (node (ref "R56") (pin "2") (pinfunction "2_2") (pintype "passive"))
      (node (ref "U$18") (pin "P$1") (pinfunction "EN_BAR_P$1") (pintype "bidirectional"))
      (node (ref "U7") (pin "7") (pinfunction "S4_7") (pintype "passive"))
    )
    (net (code "61") (name "ENB_1_6") (class "Default")
      (node (ref "R57") (pin "2") (pinfunction "2_2") (pintype "passive"))
      (node (ref "U$19") (pin "P$1") (pinfunction "EN_BAR_P$1") (pintype "bidirectional"))
      (node (ref "U7") (pin "6") (pinfunction "S3_6") (pintype "passive"))
    )
    (net (code "62") (name "ENB_1_7") (class "Default")
      (node (ref "R58") (pin "2") (pinfunction "2_2") (pintype "passive"))
      (node (ref "U$20") (pin "P$1") (pinfunction "EN_BAR_P$1") (pintype "bidirectional"))
      (node (ref "U7") (pin "5") (pinfunction "S2_5") (pintype "passive"))
    )
    (net (code "63") (name "ENB_1_8") (class "Default")
      (node (ref "R59") (pin "2") (pinfunction "2_2") (pintype "passive"))
      (node (ref "U$21") (pin "P$1") (pinfunction "EN_BAR_P$1") (pintype "bidirectional"))
      (node (ref "U7") (pin "4") (pinfunction "S1_4") (pintype "passive"))
    )
    (net (code "64") (name "ENB_1_9") (class "Default")
      (node (ref "R60") (pin "2") (pinfunction "2_2") (pintype "passive"))
      (node (ref "U$24") (pin "P$1") (pinfunction "EN_BAR_P$1") (pintype "bidirectional"))
      (node (ref "U8") (pin "9") (pinfunction "S8_9") (pintype "passive"))
    )
    (net (code "65") (name "ENB_1_10") (class "Default")
      (node (ref "R61") (pin "2") (pinfunction "2_2") (pintype "passive"))
      (node (ref "U$25") (pin "P$1") (pinfunction "EN_BAR_P$1") (pintype "bidirectional"))
      (node (ref "U8") (pin "10") (pinfunction "S7_10") (pintype "passive"))
    )
    (net (code "66") (name "ENB_1_11") (class "Default")
      (node (ref "R62") (pin "2") (pinfunction "2_2") (pintype "passive"))
      (node (ref "U$26") (pin "P$1") (pinfunction "EN_BAR_P$1") (pintype "bidirectional"))
      (node (ref "U8") (pin "11") (pinfunction "S6_11") (pintype "passive"))
    )
    (net (code "67") (name "ENB_1_12") (class "Default")
      (node (ref "R63") (pin "2") (pinfunction "2_2") (pintype "passive"))
      (node (ref "U$27") (pin "P$1") (pinfunction "EN_BAR_P$1") (pintype "bidirectional"))
      (node (ref "U8") (pin "12") (pinfunction "S5_12") (pintype "passive"))
    )
    (net (code "68") (name "ENB_1_13") (class "Default")
      (node (ref "R64") (pin "2") (pinfunction "2_2") (pintype "passive"))
      (node (ref "U$30") (pin "P$1") (pinfunction "EN_BAR_P$1") (pintype "bidirectional"))
      (node (ref "U8") (pin "7") (pinfunction "S4_7") (pintype "passive"))
    )
    (net (code "69") (name "ENB_1_14") (class "Default")
      (node (ref "R65") (pin "2") (pinfunction "2_2") (pintype "passive"))
      (node (ref "U$31") (pin "P$1") (pinfunction "EN_BAR_P$1") (pintype "bidirectional"))
      (node (ref "U8") (pin "6") (pinfunction "S3_6") (pintype "passive"))
    )
    (net (code "70") (name "ENB_1_15") (class "Default")
      (node (ref "R66") (pin "2") (pinfunction "2_2") (pintype "passive"))
      (node (ref "U$32") (pin "P$1") (pinfunction "EN_BAR_P$1") (pintype "bidirectional"))
      (node (ref "U8") (pin "5") (pinfunction "S2_5") (pintype "passive"))
    )
    (net (code "71") (name "ENB_1_16") (class "Default")
      (node (ref "R67") (pin "2") (pinfunction "2_2") (pintype "passive"))
      (node (ref "U$33") (pin "P$1") (pinfunction "EN_BAR_P$1") (pintype "bidirectional"))
      (node (ref "U8") (pin "4") (pinfunction "S1_4") (pintype "passive"))
    )
    (net (code "72") (name "ENB_2_1") (class "Default")
      (node (ref "R68") (pin "2") (pinfunction "2_2") (pintype "passive"))
      (node (ref "U$16") (pin "P$1") (pinfunction "EN_BAR_P$1") (pintype "bidirectional"))
      (node (ref "U9") (pin "7") (pinfunction "S4_7") (pintype "passive"))
    )
    (net (code "73") (name "ENB_2_2") (class "Default")
      (node (ref "R69") (pin "2") (pinfunction "2_2") (pintype "passive"))
      (node (ref "U$22") (pin "P$1") (pinfunction "EN_BAR_P$1") (pintype "bidirectional"))
      (node (ref "U9") (pin "6") (pinfunction "S3_6") (pintype "passive"))
    )
    (net (code "74") (name "ENB_2_3") (class "Default")
      (node (ref "R70") (pin "2") (pinfunction "2_2") (pintype "passive"))
      (node (ref "U$28") (pin "P$1") (pinfunction "EN_BAR_P$1") (pintype "bidirectional"))
      (node (ref "U9") (pin "5") (pinfunction "S2_5") (pintype "passive"))
    )
    (net (code "75") (name "ENB_2_4") (class "Default")
      (node (ref "R71") (pin "2") (pinfunction "2_2") (pintype "passive"))
      (node (ref "U$34") (pin "P$1") (pinfunction "EN_BAR_P$1") (pintype "bidirectional"))
      (node (ref "U9") (pin "4") (pinfunction "S1_4") (pintype "passive"))
    )
    (net (code "76") (name "ENB_3_1") (class "Default")
      (node (ref "R98") (pin "2") (pinfunction "2_2") (pintype "passive"))
      (node (ref "U$35") (pin "P$1") (pinfunction "EN_BAR_P$1") (pintype "bidirectional"))
      (node (ref "U$4") (pin "P28") (pinfunction "P$28_P28") (pintype "bidirectional"))
    )
    (net (code "77") (name "F_A0_1A") (class "Default")
      (node (ref "U$4") (pin "P7") (pinfunction "P$7_P7") (pintype "bidirectional"))
      (node (ref "U1") (pin "8") (pinfunction "D_8") (pintype "passive"))
    )
    (net (code "78") (name "F_A0_1B") (class "Default")
      (node (ref "U$4") (pin "P12") (pinfunction "P$12_P12") (pintype "bidirectional"))
      (node (ref "U2") (pin "8") (pinfunction "D_8") (pintype "passive"))
    )
    (net (code "79") (name "F_A0_2") (class "Default")
      (node (ref "U$4") (pin "P23") (pinfunction "P$23_P23") (pintype "bidirectional"))
      (node (ref "U3") (pin "8") (pinfunction "D_8") (pintype "passive"))
    )
    (net (code "80") (name "F_A1_1A") (class "Default")
      (node (ref "U$4") (pin "P9") (pinfunction "P$9_P9") (pintype "bidirectional"))
      (node (ref "U4") (pin "8") (pinfunction "D_8") (pintype "passive"))
    )
    (net (code "81") (name "F_A1_1B") (class "Default")
      (node (ref "U$4") (pin "P13") (pinfunction "P$13_P13") (pintype "bidirectional"))
      (node (ref "U5") (pin "8") (pinfunction "D_8") (pintype "passive"))
    )
    (net (code "82") (name "F_A1_2") (class "Default")
      (node (ref "U$4") (pin "P25") (pinfunction "P$25_P25") (pintype "bidirectional"))
      (node (ref "U6") (pin "8") (pinfunction "D_8") (pintype "passive"))
    )
    (net (code "83") (name "F_ENB_1A") (class "Default")
      (node (ref "U$4") (pin "P6") (pinfunction "P$6_P6") (pintype "bidirectional"))
      (node (ref "U7") (pin "8") (pinfunction "D_8") (pintype "passive"))
    )
    (net (code "84") (name "F_ENB_1B") (class "Default")
      (node (ref "U$4") (pin "P10") (pinfunction "P$10_P10") (pintype "bidirectional"))
      (node (ref "U8") (pin "8") (pinfunction "D_8") (pintype "passive"))
    )
    (net (code "85") (name "F_ENB_2") (class "Default")
      (node (ref "U$4") (pin "P22") (pinfunction "P$22_P22") (pintype "bidirectional"))
      (node (ref "U9") (pin "8") (pinfunction "D_8") (pintype "passive"))
    )
    (net (code "86") (name "GND") (class "Default")
      (node (ref "C1") (pin "2") (pinfunction "2_2") (pintype "passive"))
      (node (ref "C10") (pin "2") (pinfunction "2_2") (pintype "passive"))
      (node (ref "C11") (pin "2") (pinfunction "2_2") (pintype "passive"))
      (node (ref "C12") (pin "2") (pinfunction "2_2") (pintype "passive"))
      (node (ref "C13") (pin "2") (pinfunction "2_2") (pintype "passive"))
      (node (ref "C14") (pin "2") (pinfunction "2_2") (pintype "passive"))
      (node (ref "C15") (pin "2") (pinfunction "2_2") (pintype "passive"))
      (node (ref "C16") (pin "2") (pinfunction "2_2") (pintype "passive"))
      (node (ref "C17") (pin "2") (pinfunction "2_2") (pintype "passive"))
      (node (ref "C18") (pin "2") (pinfunction "2_2") (pintype "passive"))
      (node (ref "C19") (pin "2") (pinfunction "2_2") (pintype "passive"))
      (node (ref "C2") (pin "2") (pinfunction "2_2") (pintype "passive"))
      (node (ref "C20") (pin "2") (pinfunction "2_2") (pintype "passive"))
      (node (ref "C21") (pin "2") (pinfunction "2_2") (pintype "passive"))
      (node (ref "C22") (pin "2") (pinfunction "2_2") (pintype "passive"))
      (node (ref "C23") (pin "2") (pinfunction "2_2") (pintype "passive"))
      (node (ref "C24") (pin "2") (pinfunction "2_2") (pintype "passive"))
      (node (ref "C25") (pin "2") (pinfunction "2_2") (pintype "passive"))
      (node (ref "C26") (pin "2") (pinfunction "2_2") (pintype "passive"))
      (node (ref "C27") (pin "2") (pinfunction "2_2") (pintype "passive"))
      (node (ref "C3") (pin "2") (pinfunction "2_2") (pintype "passive"))
      (node (ref "C30") (pin "2") (pinfunction "2_2") (pintype "passive"))
      (node (ref "C31") (pin "2") (pinfunction "2_2") (pintype "passive"))
      (node (ref "C32") (pin "2") (pinfunction "2_2") (pintype "passive"))
      (node (ref "C33") (pin "2") (pinfunction "2_2") (pintype "passive"))
      (node (ref "C34") (pin "2") (pinfunction "2_2") (pintype "passive"))
      (node (ref "C35") (pin "2") (pinfunction "2_2") (pintype "passive"))
      (node (ref "C39") (pin "1") (pinfunction "1_1") (pintype "passive"))
      (node (ref "C4") (pin "2") (pinfunction "2_2") (pintype "passive"))
      (node (ref "C40") (pin "1") (pinfunction "1_1") (pintype "passive"))
      (node (ref "C41") (pin "2") (pinfunction "2_2") (pintype "passive"))
      (node (ref "C42") (pin "2") (pinfunction "2_2") (pintype "passive"))
      (node (ref "C43") (pin "2") (pinfunction "2_2") (pintype "passive"))
      (node (ref "C44") (pin "2") (pinfunction "2_2") (pintype "passive"))
      (node (ref "C48") (pin "2") (pinfunction "2_2") (pintype "passive"))
      (node (ref "C49") (pin "2") (pinfunction "2_2") (pintype "passive"))
      (node (ref "C5") (pin "2") (pinfunction "2_2") (pintype "passive"))
      (node (ref "C50") (pin "2") (pinfunction "2_2") (pintype "passive"))
      (node (ref "C51") (pin "PIN-") (pinfunction "PIN-_PIN-") (pintype "passive"))
      (node (ref "C52") (pin "2") (pinfunction "2_2") (pintype "passive"))
      (node (ref "C53") (pin "2") (pinfunction "2_2") (pintype "passive"))
      (node (ref "C54") (pin "2") (pinfunction "2_2") (pintype "passive"))
      (node (ref "C55") (pin "PIN-") (pinfunction "PIN-_PIN-") (pintype "passive"))
      (node (ref "C56") (pin "2") (pinfunction "2_2") (pintype "passive"))
      (node (ref "C57") (pin "2") (pinfunction "2_2") (pintype "passive"))
      (node (ref "C58") (pin "2") (pinfunction "2_2") (pintype "passive"))
      (node (ref "C59") (pin "PIN-") (pinfunction "PIN-_PIN-") (pintype "passive"))
      (node (ref "C6") (pin "2") (pinfunction "2_2") (pintype "passive"))
      (node (ref "C60") (pin "2") (pinfunction "2_2") (pintype "passive"))
      (node (ref "C61") (pin "2") (pinfunction "2_2") (pintype "passive"))
      (node (ref "C62") (pin "PIN+") (pinfunction "PIN+_PIN+") (pintype "passive"))
      (node (ref "C63") (pin "1") (pinfunction "1_1") (pintype "passive"))
      (node (ref "C64") (pin "1") (pinfunction "1_1") (pintype "passive"))
      (node (ref "C65") (pin "1") (pinfunction "1_1") (pintype "passive"))
      (node (ref "C66") (pin "2") (pinfunction "2_2") (pintype "passive"))
      (node (ref "C67") (pin "PIN-") (pinfunction "PIN-_PIN-") (pintype "passive"))
      (node (ref "C68") (pin "2") (pinfunction "2_2") (pintype "passive"))
      (node (ref "C69") (pin "2") (pinfunction "2_2") (pintype "passive"))
      (node (ref "C7") (pin "2") (pinfunction "2_2") (pintype "passive"))
      (node (ref "C70") (pin "2") (pinfunction "2_2") (pintype "passive"))
      (node (ref "C71") (pin "2") (pinfunction "2_2") (pintype "passive"))
      (node (ref "C72") (pin "2") (pinfunction "2_2") (pintype "passive"))
      (node (ref "C73") (pin "2") (pinfunction "2_2") (pintype "passive"))
      (node (ref "C74") (pin "2") (pinfunction "2_2") (pintype "passive"))
      (node (ref "C75") (pin "2") (pinfunction "2_2") (pintype "passive"))
      (node (ref "C76") (pin "2") (pinfunction "2_2") (pintype "passive"))
      (node (ref "C8") (pin "2") (pinfunction "2_2") (pintype "passive"))
      (node (ref "C9") (pin "2") (pinfunction "2_2") (pintype "passive"))
      (node (ref "R10") (pin "1") (pinfunction "1_1") (pintype "passive"))
      (node (ref "R100") (pin "1") (pinfunction "1_1") (pintype "passive"))
      (node (ref "R11") (pin "1") (pinfunction "1_1") (pintype "passive"))
      (node (ref "R12") (pin "1") (pinfunction "1_1") (pintype "passive"))
      (node (ref "R13") (pin "1") (pinfunction "1_1") (pintype "passive"))
      (node (ref "R14") (pin "1") (pinfunction "1_1") (pintype "passive"))
      (node (ref "R15") (pin "1") (pinfunction "1_1") (pintype "passive"))
      (node (ref "R16") (pin "1") (pinfunction "1_1") (pintype "passive"))
      (node (ref "R17") (pin "1") (pinfunction "1_1") (pintype "passive"))
      (node (ref "R18") (pin "1") (pinfunction "1_1") (pintype "passive"))
      (node (ref "R19") (pin "1") (pinfunction "1_1") (pintype "passive"))
      (node (ref "R20") (pin "1") (pinfunction "1_1") (pintype "passive"))
      (node (ref "R21") (pin "1") (pinfunction "1_1") (pintype "passive"))
      (node (ref "R22") (pin "1") (pinfunction "1_1") (pintype "passive"))
      (node (ref "R23") (pin "1") (pinfunction "1_1") (pintype "passive"))
      (node (ref "R24") (pin "1") (pinfunction "1_1") (pintype "passive"))
      (node (ref "R25") (pin "1") (pinfunction "1_1") (pintype "passive"))
      (node (ref "R26") (pin "1") (pinfunction "1_1") (pintype "passive"))
      (node (ref "R27") (pin "1") (pinfunction "1_1") (pintype "passive"))
      (node (ref "R28") (pin "1") (pinfunction "1_1") (pintype "passive"))
      (node (ref "R29") (pin "1") (pinfunction "1_1") (pintype "passive"))
      (node (ref "R30") (pin "1") (pinfunction "1_1") (pintype "passive"))
      (node (ref "R31") (pin "1") (pinfunction "1_1") (pintype "passive"))
      (node (ref "R32") (pin "1") (pinfunction "1_1") (pintype "passive"))
      (node (ref "R33") (pin "1") (pinfunction "1_1") (pintype "passive"))
      (node (ref "R34") (pin "1") (pinfunction "1_1") (pintype "passive"))
      (node (ref "R35") (pin "1") (pinfunction "1_1") (pintype "passive"))
      (node (ref "R36") (pin "1") (pinfunction "1_1") (pintype "passive"))
      (node (ref "R37") (pin "1") (pinfunction "1_1") (pintype "passive"))
      (node (ref "R38") (pin "1") (pinfunction "1_1") (pintype "passive"))
      (node (ref "R39") (pin "1") (pinfunction "1_1") (pintype "passive"))
      (node (ref "R40") (pin "1") (pinfunction "1_1") (pintype "passive"))
      (node (ref "R41") (pin "1") (pinfunction "1_1") (pintype "passive"))
      (node (ref "R42") (pin "1") (pinfunction "1_1") (pintype "passive"))
      (node (ref "R43") (pin "1") (pinfunction "1_1") (pintype "passive"))
      (node (ref "R44") (pin "1") (pinfunction "1_1") (pintype "passive"))
      (node (ref "R45") (pin "1") (pinfunction "1_1") (pintype "passive"))
      (node (ref "R46") (pin "1") (pinfunction "1_1") (pintype "passive"))
      (node (ref "R47") (pin "1") (pinfunction "1_1") (pintype "passive"))
      (node (ref "R48") (pin "1") (pinfunction "1_1") (pintype "passive"))
      (node (ref "R52") (pin "1") (pinfunction "1_1") (pintype "passive"))
      (node (ref "R53") (pin "1") (pinfunction "1_1") (pintype "passive"))
      (node (ref "R54") (pin "1") (pinfunction "1_1") (pintype "passive"))
      (node (ref "R55") (pin "1") (pinfunction "1_1") (pintype "passive"))
      (node (ref "R56") (pin "1") (pinfunction "1_1") (pintype "passive"))
      (node (ref "R57") (pin "1") (pinfunction "1_1") (pintype "passive"))
      (node (ref "R58") (pin "1") (pinfunction "1_1") (pintype "passive"))
      (node (ref "R59") (pin "1") (pinfunction "1_1") (pintype "passive"))
      (node (ref "R60") (pin "1") (pinfunction "1_1") (pintype "passive"))
      (node (ref "R61") (pin "1") (pinfunction "1_1") (pintype "passive"))
      (node (ref "R62") (pin "1") (pinfunction "1_1") (pintype "passive"))
      (node (ref "R63") (pin "1") (pinfunction "1_1") (pintype "passive"))
      (node (ref "R64") (pin "1") (pinfunction "1_1") (pintype "passive"))
      (node (ref "R65") (pin "1") (pinfunction "1_1") (pintype "passive"))
      (node (ref "R66") (pin "1") (pinfunction "1_1") (pintype "passive"))
      (node (ref "R67") (pin "1") (pinfunction "1_1") (pintype "passive"))
      (node (ref "R68") (pin "1") (pinfunction "1_1") (pintype "passive"))
      (node (ref "R69") (pin "1") (pinfunction "1_1") (pintype "passive"))
      (node (ref "R70") (pin "1") (pinfunction "1_1") (pintype "passive"))
      (node (ref "R71") (pin "1") (pinfunction "1_1") (pintype "passive"))
      (node (ref "R78") (pin "2") (pinfunction "2_2") (pintype "passive"))
      (node (ref "R88") (pin "1") (pinfunction "1_1") (pintype "passive"))
      (node (ref "R89") (pin "1") (pinfunction "1_1") (pintype "passive"))
      (node (ref "R9") (pin "1") (pinfunction "1_1") (pintype "passive"))
      (node (ref "R90") (pin "1") (pinfunction "1_1") (pintype "passive"))
      (node (ref "R99") (pin "1") (pinfunction "1_1") (pintype "passive"))
      (node (ref "U$1") (pin "GND1") (pinfunction "GND1_GND1") (pintype "bidirectional"))
      (node (ref "U$1") (pin "GND2") (pinfunction "GND2_GND2") (pintype "bidirectional"))
      (node (ref "U$1") (pin "GND3") (pinfunction "GND3_GND3") (pintype "bidirectional"))
      (node (ref "U$1") (pin "GND4") (pinfunction "GND4_GND4") (pintype "bidirectional"))
      (node (ref "U$10") (pin "P2") (pinfunction "2_GND_P2") (pintype "bidirectional"))
      (node (ref "U$10") (pin "P4") (pinfunction "4_GND_P4") (pintype "bidirectional"))
      (node (ref "U$11") (pin "A") (pinfunction "A_A") (pintype "bidirectional"))
      (node (ref "U$11") (pin "B") (pinfunction "B_B") (pintype "bidirectional"))
      (node (ref "U$13") (pin "P$11") (pinfunction "GND6_P$11") (pintype "bidirectional"))
      (node (ref "U$13") (pin "P$12") (pinfunction "GND7_P$12") (pintype "bidirectional"))
      (node (ref "U$13") (pin "P$13") (pinfunction "GND8_P$13") (pintype "bidirectional"))
      (node (ref "U$13") (pin "P$15") (pinfunction "GND9_P$15") (pintype "bidirectional"))
      (node (ref "U$13") (pin "P$16") (pinfunction "GND10_P$16") (pintype "bidirectional"))
      (node (ref "U$13") (pin "P$18") (pinfunction "GND11_P$18") (pintype "bidirectional"))
      (node (ref "U$13") (pin "P$3") (pinfunction "GND1_P$3") (pintype "bidirectional"))
      (node (ref "U$13") (pin "P$5") (pinfunction "GND2_P$5") (pintype "bidirectional"))
      (node (ref "U$13") (pin "P$6") (pinfunction "GND3_P$6") (pintype "bidirectional"))
      (node (ref "U$13") (pin "P$8") (pinfunction "GND4_P$8") (pintype "bidirectional"))
      (node (ref "U$13") (pin "P$9") (pinfunction "GND5_P$9") (pintype "bidirectional"))
      (node (ref "U$14") (pin "P$11") (pinfunction "GND6_P$11") (pintype "bidirectional"))
      (node (ref "U$14") (pin "P$12") (pinfunction "GND7_P$12") (pintype "bidirectional"))
      (node (ref "U$14") (pin "P$13") (pinfunction "GND8_P$13") (pintype "bidirectional"))
      (node (ref "U$14") (pin "P$15") (pinfunction "GND9_P$15") (pintype "bidirectional"))
      (node (ref "U$14") (pin "P$16") (pinfunction "GND10_P$16") (pintype "bidirectional"))
      (node (ref "U$14") (pin "P$18") (pinfunction "GND11_P$18") (pintype "bidirectional"))
      (node (ref "U$14") (pin "P$3") (pinfunction "GND1_P$3") (pintype "bidirectional"))
      (node (ref "U$14") (pin "P$5") (pinfunction "GND2_P$5") (pintype "bidirectional"))
      (node (ref "U$14") (pin "P$6") (pinfunction "GND3_P$6") (pintype "bidirectional"))
      (node (ref "U$14") (pin "P$8") (pinfunction "GND4_P$8") (pintype "bidirectional"))
      (node (ref "U$14") (pin "P$9") (pinfunction "GND5_P$9") (pintype "bidirectional"))
      (node (ref "U$15") (pin "P$11") (pinfunction "GND6_P$11") (pintype "bidirectional"))
      (node (ref "U$15") (pin "P$12") (pinfunction "GND7_P$12") (pintype "bidirectional"))
      (node (ref "U$15") (pin "P$13") (pinfunction "GND8_P$13") (pintype "bidirectional"))
      (node (ref "U$15") (pin "P$15") (pinfunction "GND9_P$15") (pintype "bidirectional"))
      (node (ref "U$15") (pin "P$16") (pinfunction "GND10_P$16") (pintype "bidirectional"))
      (node (ref "U$15") (pin "P$18") (pinfunction "GND11_P$18") (pintype "bidirectional"))
      (node (ref "U$15") (pin "P$3") (pinfunction "GND1_P$3") (pintype "bidirectional"))
      (node (ref "U$15") (pin "P$5") (pinfunction "GND2_P$5") (pintype "bidirectional"))
      (node (ref "U$15") (pin "P$6") (pinfunction "GND3_P$6") (pintype "bidirectional"))
      (node (ref "U$15") (pin "P$8") (pinfunction "GND4_P$8") (pintype "bidirectional"))
      (node (ref "U$15") (pin "P$9") (pinfunction "GND5_P$9") (pintype "bidirectional"))
      (node (ref "U$16") (pin "P$11") (pinfunction "GND6_P$11") (pintype "bidirectional"))
      (node (ref "U$16") (pin "P$12") (pinfunction "GND7_P$12") (pintype "bidirectional"))
      (node (ref "U$16") (pin "P$13") (pinfunction "GND8_P$13") (pintype "bidirectional"))
      (node (ref "U$16") (pin "P$15") (pinfunction "GND9_P$15") (pintype "bidirectional"))
      (node (ref "U$16") (pin "P$16") (pinfunction "GND10_P$16") (pintype "bidirectional"))
      (node (ref "U$16") (pin "P$18") (pinfunction "GND11_P$18") (pintype "bidirectional"))
      (node (ref "U$16") (pin "P$3") (pinfunction "GND1_P$3") (pintype "bidirectional"))
      (node (ref "U$16") (pin "P$5") (pinfunction "GND2_P$5") (pintype "bidirectional"))
      (node (ref "U$16") (pin "P$6") (pinfunction "GND3_P$6") (pintype "bidirectional"))
      (node (ref "U$16") (pin "P$8") (pinfunction "GND4_P$8") (pintype "bidirectional"))
      (node (ref "U$16") (pin "P$9") (pinfunction "GND5_P$9") (pintype "bidirectional"))
      (node (ref "U$18") (pin "P$11") (pinfunction "GND6_P$11") (pintype "bidirectional"))
      (node (ref "U$18") (pin "P$12") (pinfunction "GND7_P$12") (pintype "bidirectional"))
      (node (ref "U$18") (pin "P$13") (pinfunction "GND8_P$13") (pintype "bidirectional"))
      (node (ref "U$18") (pin "P$15") (pinfunction "GND9_P$15") (pintype "bidirectional"))
      (node (ref "U$18") (pin "P$16") (pinfunction "GND10_P$16") (pintype "bidirectional"))
      (node (ref "U$18") (pin "P$18") (pinfunction "GND11_P$18") (pintype "bidirectional"))
      (node (ref "U$18") (pin "P$3") (pinfunction "GND1_P$3") (pintype "bidirectional"))
      (node (ref "U$18") (pin "P$5") (pinfunction "GND2_P$5") (pintype "bidirectional"))
      (node (ref "U$18") (pin "P$6") (pinfunction "GND3_P$6") (pintype "bidirectional"))
      (node (ref "U$18") (pin "P$8") (pinfunction "GND4_P$8") (pintype "bidirectional"))
      (node (ref "U$18") (pin "P$9") (pinfunction "GND5_P$9") (pintype "bidirectional"))
      (node (ref "U$19") (pin "P$11") (pinfunction "GND6_P$11") (pintype "bidirectional"))
      (node (ref "U$19") (pin "P$12") (pinfunction "GND7_P$12") (pintype "bidirectional"))
      (node (ref "U$19") (pin "P$13") (pinfunction "GND8_P$13") (pintype "bidirectional"))
      (node (ref "U$19") (pin "P$15") (pinfunction "GND9_P$15") (pintype "bidirectional"))
      (node (ref "U$19") (pin "P$16") (pinfunction "GND10_P$16") (pintype "bidirectional"))
      (node (ref "U$19") (pin "P$18") (pinfunction "GND11_P$18") (pintype "bidirectional"))
      (node (ref "U$19") (pin "P$3") (pinfunction "GND1_P$3") (pintype "bidirectional"))
      (node (ref "U$19") (pin "P$5") (pinfunction "GND2_P$5") (pintype "bidirectional"))
      (node (ref "U$19") (pin "P$6") (pinfunction "GND3_P$6") (pintype "bidirectional"))
      (node (ref "U$19") (pin "P$8") (pinfunction "GND4_P$8") (pintype "bidirectional"))
      (node (ref "U$19") (pin "P$9") (pinfunction "GND5_P$9") (pintype "bidirectional"))
      (node (ref "U$20") (pin "P$11") (pinfunction "GND6_P$11") (pintype "bidirectional"))
      (node (ref "U$20") (pin "P$12") (pinfunction "GND7_P$12") (pintype "bidirectional"))
      (node (ref "U$20") (pin "P$13") (pinfunction "GND8_P$13") (pintype "bidirectional"))
      (node (ref "U$20") (pin "P$15") (pinfunction "GND9_P$15") (pintype "bidirectional"))
      (node (ref "U$20") (pin "P$16") (pinfunction "GND10_P$16") (pintype "bidirectional"))
      (node (ref "U$20") (pin "P$18") (pinfunction "GND11_P$18") (pintype "bidirectional"))
      (node (ref "U$20") (pin "P$3") (pinfunction "GND1_P$3") (pintype "bidirectional"))
      (node (ref "U$20") (pin "P$5") (pinfunction "GND2_P$5") (pintype "bidirectional"))
      (node (ref "U$20") (pin "P$6") (pinfunction "GND3_P$6") (pintype "bidirectional"))
      (node (ref "U$20") (pin "P$8") (pinfunction "GND4_P$8") (pintype "bidirectional"))
      (node (ref "U$20") (pin "P$9") (pinfunction "GND5_P$9") (pintype "bidirectional"))
      (node (ref "U$21") (pin "P$11") (pinfunction "GND6_P$11") (pintype "bidirectional"))
      (node (ref "U$21") (pin "P$12") (pinfunction "GND7_P$12") (pintype "bidirectional"))
      (node (ref "U$21") (pin "P$13") (pinfunction "GND8_P$13") (pintype "bidirectional"))
      (node (ref "U$21") (pin "P$15") (pinfunction "GND9_P$15") (pintype "bidirectional"))
      (node (ref "U$21") (pin "P$16") (pinfunction "GND10_P$16") (pintype "bidirectional"))
      (node (ref "U$21") (pin "P$18") (pinfunction "GND11_P$18") (pintype "bidirectional"))
      (node (ref "U$21") (pin "P$3") (pinfunction "GND1_P$3") (pintype "bidirectional"))
      (node (ref "U$21") (pin "P$5") (pinfunction "GND2_P$5") (pintype "bidirectional"))
      (node (ref "U$21") (pin "P$6") (pinfunction "GND3_P$6") (pintype "bidirectional"))
      (node (ref "U$21") (pin "P$8") (pinfunction "GND4_P$8") (pintype "bidirectional"))
      (node (ref "U$21") (pin "P$9") (pinfunction "GND5_P$9") (pintype "bidirectional"))
      (node (ref "U$22") (pin "P$11") (pinfunction "GND6_P$11") (pintype "bidirectional"))
      (node (ref "U$22") (pin "P$12") (pinfunction "GND7_P$12") (pintype "bidirectional"))
      (node (ref "U$22") (pin "P$13") (pinfunction "GND8_P$13") (pintype "bidirectional"))
      (node (ref "U$22") (pin "P$15") (pinfunction "GND9_P$15") (pintype "bidirectional"))
      (node (ref "U$22") (pin "P$16") (pinfunction "GND10_P$16") (pintype "bidirectional"))
      (node (ref "U$22") (pin "P$18") (pinfunction "GND11_P$18") (pintype "bidirectional"))
      (node (ref "U$22") (pin "P$3") (pinfunction "GND1_P$3") (pintype "bidirectional"))
      (node (ref "U$22") (pin "P$5") (pinfunction "GND2_P$5") (pintype "bidirectional"))
      (node (ref "U$22") (pin "P$6") (pinfunction "GND3_P$6") (pintype "bidirectional"))
      (node (ref "U$22") (pin "P$8") (pinfunction "GND4_P$8") (pintype "bidirectional"))
      (node (ref "U$22") (pin "P$9") (pinfunction "GND5_P$9") (pintype "bidirectional"))
      (node (ref "U$24") (pin "P$11") (pinfunction "GND6_P$11") (pintype "bidirectional"))
      (node (ref "U$24") (pin "P$12") (pinfunction "GND7_P$12") (pintype "bidirectional"))
      (node (ref "U$24") (pin "P$13") (pinfunction "GND8_P$13") (pintype "bidirectional"))
      (node (ref "U$24") (pin "P$15") (pinfunction "GND9_P$15") (pintype "bidirectional"))
      (node (ref "U$24") (pin "P$16") (pinfunction "GND10_P$16") (pintype "bidirectional"))
      (node (ref "U$24") (pin "P$18") (pinfunction "GND11_P$18") (pintype "bidirectional"))
      (node (ref "U$24") (pin "P$3") (pinfunction "GND1_P$3") (pintype "bidirectional"))
      (node (ref "U$24") (pin "P$5") (pinfunction "GND2_P$5") (pintype "bidirectional"))
      (node (ref "U$24") (pin "P$6") (pinfunction "GND3_P$6") (pintype "bidirectional"))
      (node (ref "U$24") (pin "P$8") (pinfunction "GND4_P$8") (pintype "bidirectional"))
      (node (ref "U$24") (pin "P$9") (pinfunction "GND5_P$9") (pintype "bidirectional"))
      (node (ref "U$25") (pin "P$11") (pinfunction "GND6_P$11") (pintype "bidirectional"))
      (node (ref "U$25") (pin "P$12") (pinfunction "GND7_P$12") (pintype "bidirectional"))
      (node (ref "U$25") (pin "P$13") (pinfunction "GND8_P$13") (pintype "bidirectional"))
      (node (ref "U$25") (pin "P$15") (pinfunction "GND9_P$15") (pintype "bidirectional"))
      (node (ref "U$25") (pin "P$16") (pinfunction "GND10_P$16") (pintype "bidirectional"))
      (node (ref "U$25") (pin "P$18") (pinfunction "GND11_P$18") (pintype "bidirectional"))
      (node (ref "U$25") (pin "P$3") (pinfunction "GND1_P$3") (pintype "bidirectional"))
      (node (ref "U$25") (pin "P$5") (pinfunction "GND2_P$5") (pintype "bidirectional"))
      (node (ref "U$25") (pin "P$6") (pinfunction "GND3_P$6") (pintype "bidirectional"))
      (node (ref "U$25") (pin "P$8") (pinfunction "GND4_P$8") (pintype "bidirectional"))
      (node (ref "U$25") (pin "P$9") (pinfunction "GND5_P$9") (pintype "bidirectional"))
      (node (ref "U$26") (pin "P$11") (pinfunction "GND6_P$11") (pintype "bidirectional"))
      (node (ref "U$26") (pin "P$12") (pinfunction "GND7_P$12") (pintype "bidirectional"))
      (node (ref "U$26") (pin "P$13") (pinfunction "GND8_P$13") (pintype "bidirectional"))
      (node (ref "U$26") (pin "P$15") (pinfunction "GND9_P$15") (pintype "bidirectional"))
      (node (ref "U$26") (pin "P$16") (pinfunction "GND10_P$16") (pintype "bidirectional"))
      (node (ref "U$26") (pin "P$18") (pinfunction "GND11_P$18") (pintype "bidirectional"))
      (node (ref "U$26") (pin "P$3") (pinfunction "GND1_P$3") (pintype "bidirectional"))
      (node (ref "U$26") (pin "P$5") (pinfunction "GND2_P$5") (pintype "bidirectional"))
      (node (ref "U$26") (pin "P$6") (pinfunction "GND3_P$6") (pintype "bidirectional"))
      (node (ref "U$26") (pin "P$8") (pinfunction "GND4_P$8") (pintype "bidirectional"))
      (node (ref "U$26") (pin "P$9") (pinfunction "GND5_P$9") (pintype "bidirectional"))
      (node (ref "U$27") (pin "P$11") (pinfunction "GND6_P$11") (pintype "bidirectional"))
      (node (ref "U$27") (pin "P$12") (pinfunction "GND7_P$12") (pintype "bidirectional"))
      (node (ref "U$27") (pin "P$13") (pinfunction "GND8_P$13") (pintype "bidirectional"))
      (node (ref "U$27") (pin "P$15") (pinfunction "GND9_P$15") (pintype "bidirectional"))
      (node (ref "U$27") (pin "P$16") (pinfunction "GND10_P$16") (pintype "bidirectional"))
      (node (ref "U$27") (pin "P$18") (pinfunction "GND11_P$18") (pintype "bidirectional"))
      (node (ref "U$27") (pin "P$3") (pinfunction "GND1_P$3") (pintype "bidirectional"))
      (node (ref "U$27") (pin "P$5") (pinfunction "GND2_P$5") (pintype "bidirectional"))
      (node (ref "U$27") (pin "P$6") (pinfunction "GND3_P$6") (pintype "bidirectional"))
      (node (ref "U$27") (pin "P$8") (pinfunction "GND4_P$8") (pintype "bidirectional"))
      (node (ref "U$27") (pin "P$9") (pinfunction "GND5_P$9") (pintype "bidirectional"))
      (node (ref "U$28") (pin "P$11") (pinfunction "GND6_P$11") (pintype "bidirectional"))
      (node (ref "U$28") (pin "P$12") (pinfunction "GND7_P$12") (pintype "bidirectional"))
      (node (ref "U$28") (pin "P$13") (pinfunction "GND8_P$13") (pintype "bidirectional"))
      (node (ref "U$28") (pin "P$15") (pinfunction "GND9_P$15") (pintype "bidirectional"))
      (node (ref "U$28") (pin "P$16") (pinfunction "GND10_P$16") (pintype "bidirectional"))
      (node (ref "U$28") (pin "P$18") (pinfunction "GND11_P$18") (pintype "bidirectional"))
      (node (ref "U$28") (pin "P$3") (pinfunction "GND1_P$3") (pintype "bidirectional"))
      (node (ref "U$28") (pin "P$5") (pinfunction "GND2_P$5") (pintype "bidirectional"))
      (node (ref "U$28") (pin "P$6") (pinfunction "GND3_P$6") (pintype "bidirectional"))
      (node (ref "U$28") (pin "P$8") (pinfunction "GND4_P$8") (pintype "bidirectional"))
      (node (ref "U$28") (pin "P$9") (pinfunction "GND5_P$9") (pintype "bidirectional"))
      (node (ref "U$3") (pin "GND1") (pinfunction "GND1_GND1") (pintype "bidirectional"))
      (node (ref "U$3") (pin "GND2") (pinfunction "GND2_GND2") (pintype "bidirectional"))
      (node (ref "U$3") (pin "GND3") (pinfunction "GND3_GND3") (pintype "bidirectional"))
      (node (ref "U$3") (pin "GND4") (pinfunction "GND4_GND4") (pintype "bidirectional"))
      (node (ref "U$30") (pin "P$11") (pinfunction "GND6_P$11") (pintype "bidirectional"))
      (node (ref "U$30") (pin "P$12") (pinfunction "GND7_P$12") (pintype "bidirectional"))
      (node (ref "U$30") (pin "P$13") (pinfunction "GND8_P$13") (pintype "bidirectional"))
      (node (ref "U$30") (pin "P$15") (pinfunction "GND9_P$15") (pintype "bidirectional"))
      (node (ref "U$30") (pin "P$16") (pinfunction "GND10_P$16") (pintype "bidirectional"))
      (node (ref "U$30") (pin "P$18") (pinfunction "GND11_P$18") (pintype "bidirectional"))
      (node (ref "U$30") (pin "P$3") (pinfunction "GND1_P$3") (pintype "bidirectional"))
      (node (ref "U$30") (pin "P$5") (pinfunction "GND2_P$5") (pintype "bidirectional"))
      (node (ref "U$30") (pin "P$6") (pinfunction "GND3_P$6") (pintype "bidirectional"))
      (node (ref "U$30") (pin "P$8") (pinfunction "GND4_P$8") (pintype "bidirectional"))
      (node (ref "U$30") (pin "P$9") (pinfunction "GND5_P$9") (pintype "bidirectional"))
      (node (ref "U$31") (pin "P$11") (pinfunction "GND6_P$11") (pintype "bidirectional"))
      (node (ref "U$31") (pin "P$12") (pinfunction "GND7_P$12") (pintype "bidirectional"))
      (node (ref "U$31") (pin "P$13") (pinfunction "GND8_P$13") (pintype "bidirectional"))
      (node (ref "U$31") (pin "P$15") (pinfunction "GND9_P$15") (pintype "bidirectional"))
      (node (ref "U$31") (pin "P$16") (pinfunction "GND10_P$16") (pintype "bidirectional"))
      (node (ref "U$31") (pin "P$18") (pinfunction "GND11_P$18") (pintype "bidirectional"))
      (node (ref "U$31") (pin "P$3") (pinfunction "GND1_P$3") (pintype "bidirectional"))
      (node (ref "U$31") (pin "P$5") (pinfunction "GND2_P$5") (pintype "bidirectional"))
      (node (ref "U$31") (pin "P$6") (pinfunction "GND3_P$6") (pintype "bidirectional"))
      (node (ref "U$31") (pin "P$8") (pinfunction "GND4_P$8") (pintype "bidirectional"))
      (node (ref "U$31") (pin "P$9") (pinfunction "GND5_P$9") (pintype "bidirectional"))
      (node (ref "U$32") (pin "P$11") (pinfunction "GND6_P$11") (pintype "bidirectional"))
      (node (ref "U$32") (pin "P$12") (pinfunction "GND7_P$12") (pintype "bidirectional"))
      (node (ref "U$32") (pin "P$13") (pinfunction "GND8_P$13") (pintype "bidirectional"))
      (node (ref "U$32") (pin "P$15") (pinfunction "GND9_P$15") (pintype "bidirectional"))
      (node (ref "U$32") (pin "P$16") (pinfunction "GND10_P$16") (pintype "bidirectional"))
      (node (ref "U$32") (pin "P$18") (pinfunction "GND11_P$18") (pintype "bidirectional"))
      (node (ref "U$32") (pin "P$3") (pinfunction "GND1_P$3") (pintype "bidirectional"))
      (node (ref "U$32") (pin "P$5") (pinfunction "GND2_P$5") (pintype "bidirectional"))
      (node (ref "U$32") (pin "P$6") (pinfunction "GND3_P$6") (pintype "bidirectional"))
      (node (ref "U$32") (pin "P$8") (pinfunction "GND4_P$8") (pintype "bidirectional"))
      (node (ref "U$32") (pin "P$9") (pinfunction "GND5_P$9") (pintype "bidirectional"))
      (node (ref "U$33") (pin "P$11") (pinfunction "GND6_P$11") (pintype "bidirectional"))
      (node (ref "U$33") (pin "P$12") (pinfunction "GND7_P$12") (pintype "bidirectional"))
      (node (ref "U$33") (pin "P$13") (pinfunction "GND8_P$13") (pintype "bidirectional"))
      (node (ref "U$33") (pin "P$15") (pinfunction "GND9_P$15") (pintype "bidirectional"))
      (node (ref "U$33") (pin "P$16") (pinfunction "GND10_P$16") (pintype "bidirectional"))
      (node (ref "U$33") (pin "P$18") (pinfunction "GND11_P$18") (pintype "bidirectional"))
      (node (ref "U$33") (pin "P$3") (pinfunction "GND1_P$3") (pintype "bidirectional"))
      (node (ref "U$33") (pin "P$5") (pinfunction "GND2_P$5") (pintype "bidirectional"))
      (node (ref "U$33") (pin "P$6") (pinfunction "GND3_P$6") (pintype "bidirectional"))
      (node (ref "U$33") (pin "P$8") (pinfunction "GND4_P$8") (pintype "bidirectional"))
      (node (ref "U$33") (pin "P$9") (pinfunction "GND5_P$9") (pintype "bidirectional"))
      (node (ref "U$34") (pin "P$11") (pinfunction "GND6_P$11") (pintype "bidirectional"))
      (node (ref "U$34") (pin "P$12") (pinfunction "GND7_P$12") (pintype "bidirectional"))
      (node (ref "U$34") (pin "P$13") (pinfunction "GND8_P$13") (pintype "bidirectional"))
      (node (ref "U$34") (pin "P$15") (pinfunction "GND9_P$15") (pintype "bidirectional"))
      (node (ref "U$34") (pin "P$16") (pinfunction "GND10_P$16") (pintype "bidirectional"))
      (node (ref "U$34") (pin "P$18") (pinfunction "GND11_P$18") (pintype "bidirectional"))
      (node (ref "U$34") (pin "P$3") (pinfunction "GND1_P$3") (pintype "bidirectional"))
      (node (ref "U$34") (pin "P$5") (pinfunction "GND2_P$5") (pintype "bidirectional"))
      (node (ref "U$34") (pin "P$6") (pinfunction "GND3_P$6") (pintype "bidirectional"))
      (node (ref "U$34") (pin "P$8") (pinfunction "GND4_P$8") (pintype "bidirectional"))
      (node (ref "U$34") (pin "P$9") (pinfunction "GND5_P$9") (pintype "bidirectional"))
      (node (ref "U$35") (pin "P$11") (pinfunction "GND6_P$11") (pintype "bidirectional"))
      (node (ref "U$35") (pin "P$12") (pinfunction "GND7_P$12") (pintype "bidirectional"))
      (node (ref "U$35") (pin "P$13") (pinfunction "GND8_P$13") (pintype "bidirectional"))
      (node (ref "U$35") (pin "P$15") (pinfunction "GND9_P$15") (pintype "bidirectional"))
      (node (ref "U$35") (pin "P$16") (pinfunction "GND10_P$16") (pintype "bidirectional"))
      (node (ref "U$35") (pin "P$18") (pinfunction "GND11_P$18") (pintype "bidirectional"))
      (node (ref "U$35") (pin "P$3") (pinfunction "GND1_P$3") (pintype "bidirectional"))
      (node (ref "U$35") (pin "P$5") (pinfunction "GND2_P$5") (pintype "bidirectional"))
      (node (ref "U$35") (pin "P$6") (pinfunction "GND3_P$6") (pintype "bidirectional"))
      (node (ref "U$35") (pin "P$8") (pinfunction "GND4_P$8") (pintype "bidirectional"))
      (node (ref "U$35") (pin "P$9") (pinfunction "GND5_P$9") (pintype "bidirectional"))
      (node (ref "U$36") (pin "1") (pinfunction "1_NC_1") (pintype "bidirectional"))
      (node (ref "U$36") (pin "12") (pinfunction "12_NC_12") (pintype "bidirectional"))
      (node (ref "U$36") (pin "13") (pinfunction "13_GND_13") (pintype "bidirectional"))
      (node (ref "U$36") (pin "15") (pinfunction "15_GND_15") (pintype "bidirectional"))
      (node (ref "U$36") (pin "16") (pinfunction "16_NC_16") (pintype "bidirectional"))
      (node (ref "U$36") (pin "17") (pinfunction "EP_17") (pintype "bidirectional"))
      (node (ref "U$36") (pin "2") (pinfunction "2_GND_2") (pintype "bidirectional"))
      (node (ref "U$36") (pin "4") (pinfunction "4_GND_4") (pintype "bidirectional"))
      (node (ref "U$36") (pin "5") (pinfunction "5_NC_5") (pintype "bidirectional"))
      (node (ref "U$36") (pin "6") (pinfunction "6_GND_6") (pintype "bidirectional"))
      (node (ref "U$36") (pin "8") (pinfunction "8_GND_8") (pintype "bidirectional"))
      (node (ref "U$36") (pin "9") (pinfunction "9_NC_9") (pintype "bidirectional"))
      (node (ref "U$4") (pin "G1") (pinfunction "G1_G1") (pintype "bidirectional"))
      (node (ref "U$4") (pin "G2") (pinfunction "G2_G2") (pintype "bidirectional"))
      (node (ref "U$4") (pin "G3") (pinfunction "G3_G3") (pintype "bidirectional"))
      (node (ref "U$4") (pin "G4") (pinfunction "G4_G4") (pintype "bidirectional"))
      (node (ref "U$4") (pin "P11") (pinfunction "P$11_P11") (pintype "bidirectional"))
      (node (ref "U$4") (pin "P14") (pinfunction "P$14_P14") (pintype "bidirectional"))
      (node (ref "U$4") (pin "P2") (pinfunction "P$2_P2") (pintype "bidirectional"))
      (node (ref "U$4") (pin "P21") (pinfunction "P$21_P21") (pintype "bidirectional"))
      (node (ref "U$4") (pin "P24") (pinfunction "P$24_P24") (pintype "bidirectional"))
      (node (ref "U$4") (pin "P27") (pinfunction "P$27_P27") (pintype "bidirectional"))
      (node (ref "U$4") (pin "P30") (pinfunction "P$30_P30") (pintype "bidirectional"))
      (node (ref "U$4") (pin "P33") (pinfunction "P$33_P33") (pintype "bidirectional"))
      (node (ref "U$4") (pin "P36") (pinfunction "P$36_P36") (pintype "bidirectional"))
      (node (ref "U$4") (pin "P39") (pinfunction "P$39_P39") (pintype "bidirectional"))
      (node (ref "U$4") (pin "P42") (pinfunction "P$42_P42") (pintype "bidirectional"))
      (node (ref "U$4") (pin "P45") (pinfunction "P$45_P45") (pintype "bidirectional"))
      (node (ref "U$4") (pin "P48") (pinfunction "P$48_P48") (pintype "bidirectional"))
      (node (ref "U$4") (pin "P5") (pinfunction "P$5_P5") (pintype "bidirectional"))
      (node (ref "U$4") (pin "P55") (pinfunction "P$55_P55") (pintype "bidirectional"))
      (node (ref "U$4") (pin "P58") (pinfunction "P$58_P58") (pintype "bidirectional"))
      (node (ref "U$4") (pin "P61") (pinfunction "P$61_P61") (pintype "bidirectional"))
      (node (ref "U$4") (pin "P64") (pinfunction "P$64_P64") (pintype "bidirectional"))
      (node (ref "U$4") (pin "P67") (pinfunction "P$67_P67") (pintype "bidirectional"))
      (node (ref "U$4") (pin "P8") (pinfunction "P$8_P8") (pintype "bidirectional"))
      (node (ref "U$40") (pin "P2") (pinfunction "2_GND_P2") (pintype "bidirectional"))
      (node (ref "U$40") (pin "P4") (pinfunction "4_GND_P4") (pintype "bidirectional"))
      (node (ref "U$42") (pin "EP") (pinfunction "EP_GND_EP") (pintype "bidirectional"))
      (node (ref "U$42") (pin "P$3") (pinfunction "3_GND_P$3") (pintype "bidirectional"))
      (node (ref "U$42") (pin "P$4") (pinfunction "4_GND_P$4") (pintype "bidirectional"))
      (node (ref "U$43") (pin "3") (pinfunction "3_3") (pintype "bidirectional"))
      (node (ref "U$44") (pin "5") (pinfunction "VCC_5") (pintype "bidirectional"))
      (node (ref "U$46") (pin "P$1") (pinfunction "1_GND_P$1") (pintype "bidirectional"))
      (node (ref "U$46") (pin "P$11") (pinfunction "11_GND_P$11") (pintype "bidirectional"))
      (node (ref "U$46") (pin "P$12") (pinfunction "12_GND_P$12") (pintype "bidirectional"))
      (node (ref "U$46") (pin "P$13") (pinfunction "13_GND_P$13") (pintype "bidirectional"))
      (node (ref "U$46") (pin "P$15") (pinfunction "15_GND_P$15") (pintype "bidirectional"))
      (node (ref "U$46") (pin "P$16") (pinfunction "16_GND_P$16") (pintype "bidirectional"))
      (node (ref "U$46") (pin "P$3") (pinfunction "3_GND_P$3") (pintype "bidirectional"))
      (node (ref "U$46") (pin "P$4") (pinfunction "4_GND_P$4") (pintype "bidirectional"))
      (node (ref "U$46") (pin "P$5") (pinfunction "5_GND_P$5") (pintype "bidirectional"))
      (node (ref "U$46") (pin "P$6") (pinfunction "6_GND_P$6") (pintype "bidirectional"))
      (node (ref "U$46") (pin "P$7") (pinfunction "7_GND_P$7") (pintype "bidirectional"))
      (node (ref "U$46") (pin "P$8") (pinfunction "8_GND_P$8") (pintype "bidirectional"))
      (node (ref "U$46") (pin "P$9") (pinfunction "9_GND_P$9") (pintype "bidirectional"))
      (node (ref "U$47") (pin "3") (pinfunction "3_3") (pintype "bidirectional"))
      (node (ref "U$48") (pin "2") (pinfunction "P$2_2") (pintype "bidirectional"))
      (node (ref "U$5") (pin "GND1") (pinfunction "GND1_GND1") (pintype "bidirectional"))
      (node (ref "U$5") (pin "GND2") (pinfunction "GND2_GND2") (pintype "bidirectional"))
      (node (ref "U$5") (pin "GND3") (pinfunction "GND3_GND3") (pintype "bidirectional"))
      (node (ref "U$5") (pin "GND4") (pinfunction "GND4_GND4") (pintype "bidirectional"))
      (node (ref "U$50") (pin "2") (pinfunction "P$2_2") (pintype "bidirectional"))
      (node (ref "U$51") (pin "3") (pinfunction "P$3_3") (pintype "bidirectional"))
      (node (ref "U$52") (pin "3") (pinfunction "P$3_3") (pintype "bidirectional"))
      (node (ref "U$53") (pin "GND1") (pinfunction "GND1_GND1") (pintype "bidirectional"))
      (node (ref "U$53") (pin "GND2") (pinfunction "GND2_GND2") (pintype "bidirectional"))
      (node (ref "U$55") (pin "A") (pinfunction "A_A") (pintype "bidirectional"))
      (node (ref "U$55") (pin "B") (pinfunction "B_B") (pintype "bidirectional"))
      (node (ref "U$6") (pin "GND1") (pinfunction "GND1_GND1") (pintype "bidirectional"))
      (node (ref "U$6") (pin "GND2") (pinfunction "GND2_GND2") (pintype "bidirectional"))
      (node (ref "U$6") (pin "GND3") (pinfunction "GND3_GND3") (pintype "bidirectional"))
      (node (ref "U$6") (pin "GND4") (pinfunction "GND4_GND4") (pintype "bidirectional"))
      (node (ref "U$7") (pin "GND1") (pinfunction "GND1_GND1") (pintype "bidirectional"))
      (node (ref "U$7") (pin "GND2") (pinfunction "GND2_GND2") (pintype "bidirectional"))
      (node (ref "U$7") (pin "GND3") (pinfunction "GND3_GND3") (pintype "bidirectional"))
      (node (ref "U$7") (pin "GND4") (pinfunction "GND4_GND4") (pintype "bidirectional"))
      (node (ref "U$8") (pin "P$11") (pinfunction "GND6_P$11") (pintype "bidirectional"))
      (node (ref "U$8") (pin "P$12") (pinfunction "GND7_P$12") (pintype "bidirectional"))
      (node (ref "U$8") (pin "P$13") (pinfunction "GND8_P$13") (pintype "bidirectional"))
      (node (ref "U$8") (pin "P$15") (pinfunction "GND9_P$15") (pintype "bidirectional"))
      (node (ref "U$8") (pin "P$16") (pinfunction "GND10_P$16") (pintype "bidirectional"))
      (node (ref "U$8") (pin "P$18") (pinfunction "GND11_P$18") (pintype "bidirectional"))
      (node (ref "U$8") (pin "P$3") (pinfunction "GND1_P$3") (pintype "bidirectional"))
      (node (ref "U$8") (pin "P$5") (pinfunction "GND2_P$5") (pintype "bidirectional"))
      (node (ref "U$8") (pin "P$6") (pinfunction "GND3_P$6") (pintype "bidirectional"))
      (node (ref "U$8") (pin "P$8") (pinfunction "GND4_P$8") (pintype "bidirectional"))
      (node (ref "U$8") (pin "P$9") (pinfunction "GND5_P$9") (pintype "bidirectional"))
      (node (ref "U$9") (pin "P$3") (pinfunction "GND_P$3") (pintype "bidirectional"))
      (node (ref "U$9") (pin "P$6") (pinfunction "GND2_P$6") (pintype "bidirectional"))
      (node (ref "U$9") (pin "P$7") (pinfunction "GND1_P$7") (pintype "bidirectional"))
      (node (ref "U1") (pin "14") (pinfunction "GND_14") (pintype "passive"))
      (node (ref "U2") (pin "14") (pinfunction "GND_14") (pintype "passive"))
      (node (ref "U3") (pin "14") (pinfunction "GND_14") (pintype "passive"))
      (node (ref "U4") (pin "14") (pinfunction "GND_14") (pintype "passive"))
      (node (ref "U5") (pin "14") (pinfunction "GND_14") (pintype "passive"))
      (node (ref "U6") (pin "14") (pinfunction "GND_14") (pintype "passive"))
      (node (ref "U7") (pin "14") (pinfunction "GND_14") (pintype "passive"))
      (node (ref "U8") (pin "14") (pinfunction "GND_14") (pintype "passive"))
      (node (ref "U9") (pin "14") (pinfunction "GND_14") (pintype "passive"))
    )
    (net (code "87") (name "MOSI") (class "Default")
      (node (ref "U$4") (pin "P3") (pinfunction "P$3_P3") (pintype "bidirectional"))
      (node (ref "U1") (pin "3") (pinfunction "DIN_3") (pintype "passive"))
      (node (ref "U2") (pin "3") (pinfunction "DIN_3") (pintype "passive"))
      (node (ref "U3") (pin "3") (pinfunction "DIN_3") (pintype "passive"))
      (node (ref "U4") (pin "3") (pinfunction "DIN_3") (pintype "passive"))
      (node (ref "U5") (pin "3") (pinfunction "DIN_3") (pintype "passive"))
      (node (ref "U6") (pin "3") (pinfunction "DIN_3") (pintype "passive"))
      (node (ref "U7") (pin "3") (pinfunction "DIN_3") (pintype "passive"))
      (node (ref "U8") (pin "3") (pinfunction "DIN_3") (pintype "passive"))
      (node (ref "U9") (pin "3") (pinfunction "DIN_3") (pintype "passive"))
    )
    (net (code "88") (name "NC1") (class "Default")
      (node (ref "U$4") (pin "P26") (pinfunction "P$26_P26") (pintype "bidirectional"))
    )
    (net (code "89") (name "NC5") (class "Default")
      (node (ref "U$4") (pin "P32") (pinfunction "P$32_P32") (pintype "bidirectional"))
    )
    (net (code "90") (name "NC6") (class "Default")
      (node (ref "U$4") (pin "P66") (pinfunction "P$66_P66") (pintype "bidirectional"))
    )
    (net (code "91") (name "NC7") (class "Default")
      (node (ref "U$4") (pin "P65") (pinfunction "P$65_P65") (pintype "bidirectional"))
    )
    (net (code "92") (name "NC8") (class "Default")
      (node (ref "U$4") (pin "P63") (pinfunction "P$63_P63") (pintype "bidirectional"))
    )
    (net (code "93") (name "NC9") (class "Default")
      (node (ref "U$4") (pin "P62") (pinfunction "P$62_P62") (pintype "bidirectional"))
    )
    (net (code "94") (name "NC10") (class "Default")
      (node (ref "U$4") (pin "P60") (pinfunction "P$60_P60") (pintype "bidirectional"))
    )
    (net (code "95") (name "NC11") (class "Default")
      (node (ref "U$4") (pin "P59") (pinfunction "P$59_P59") (pintype "bidirectional"))
    )
    (net (code "96") (name "NC12") (class "Default")
      (node (ref "U$4") (pin "P57") (pinfunction "P$57_P57") (pintype "bidirectional"))
    )
    (net (code "97") (name "NC13") (class "Default")
      (node (ref "U$4") (pin "P56") (pinfunction "P$56_P56") (pintype "bidirectional"))
    )
    (net (code "98") (name "Net-(C28-Pad2)") (class "Default")
      (node (ref "C28") (pin "2") (pinfunction "2_2") (pintype "passive"))
      (node (ref "R91") (pin "1") (pinfunction "1_1") (pintype "passive"))
      (node (ref "R92") (pin "2") (pinfunction "2_2") (pintype "passive"))
    )
    (net (code "99") (name "Net-(C29-Pad1)") (class "Default")
      (node (ref "C29") (pin "1") (pinfunction "1_1") (pintype "passive"))
      (node (ref "R96") (pin "1") (pinfunction "1_1") (pintype "passive"))
    )
    (net (code "100") (name "Net-(C38-Pad1)") (class "Default")
      (node (ref "C38") (pin "1") (pinfunction "1_1") (pintype "passive"))
      (node (ref "R78") (pin "1") (pinfunction "1_1") (pintype "passive"))
    )
    (net (code "101") (name "Net-(C45-Pad2)") (class "Default")
      (node (ref "C45") (pin "2") (pinfunction "2_2") (pintype "passive"))
      (node (ref "R102") (pin "1") (pinfunction "1_1") (pintype "passive"))
      (node (ref "R93") (pin "1") (pinfunction "1_1") (pintype "passive"))
      (node (ref "R94") (pin "1") (pinfunction "1_1") (pintype "passive"))
    )
    (net (code "102") (name "Net-(C46-Pad1)") (class "Default")
      (node (ref "C46") (pin "1") (pinfunction "1_1") (pintype "passive"))
      (node (ref "R79") (pin "2") (pinfunction "2_2") (pintype "passive"))
    )
    (net (code "103") (name "Net-(R5-Pad2)") (class "Default")
      (node (ref "R5") (pin "2") (pinfunction "2_2") (pintype "passive"))
      (node (ref "R6") (pin "1") (pinfunction "1_1") (pintype "passive"))
    )
    (net (code "104") (name "Net-(R74-Pad1)") (class "Default")
      (node (ref "R74") (pin "1") (pinfunction "1_1") (pintype "passive"))
      (node (ref "R75") (pin "1") (pinfunction "1_1") (pintype "passive"))
      (node (ref "R80") (pin "1") (pinfunction "1_1") (pintype "passive"))
    )
    (net (code "105") (name "Net-(R76-Pad1)") (class "Default")
      (node (ref "R76") (pin "1") (pinfunction "1_1") (pintype "passive"))
      (node (ref "R77") (pin "1") (pinfunction "1_1") (pintype "passive"))
      (node (ref "R81") (pin "1") (pinfunction "1_1") (pintype "passive"))
    )
    (net (code "106") (name "Net-(R83-Pad1)") (class "Default")
      (node (ref "R83") (pin "1") (pinfunction "1_1") (pintype "passive"))
      (node (ref "U$5") (pin "SIG") (pinfunction "SIG_SIG") (pintype "bidirectional"))
    )
    (net (code "107") (name "Net-(R84-Pad1)") (class "Default")
      (node (ref "R84") (pin "1") (pinfunction "1_1") (pintype "passive"))
      (node (ref "U$3") (pin "SIG") (pinfunction "SIG_SIG") (pintype "bidirectional"))
    )
    (net (code "108") (name "Net-(R85-Pad2)") (class "Default")
      (node (ref "R85") (pin "2") (pinfunction "2_2") (pintype "passive"))
      (node (ref "R86") (pin "1") (pinfunction "1_1") (pintype "passive"))
    )
    (net (code "109") (name "Net-(R87-Pad1)") (class "Default")
      (node (ref "R87") (pin "1") (pinfunction "1_1") (pintype "passive"))
      (node (ref "U$43") (pin "2") (pinfunction "2_2") (pintype "bidirectional"))
    )
    (net (code "110") (name "Net-(R91-Pad2)") (class "Default")
      (node (ref "R91") (pin "2") (pinfunction "2_2") (pintype "passive"))
      (node (ref "U$6") (pin "SIG") (pinfunction "SIG_SIG") (pintype "bidirectional"))
    )
    (net (code "111") (name "Net-(R94-Pad2)") (class "Default")
      (node (ref "R94") (pin "2") (pinfunction "2_2") (pintype "passive"))
      (node (ref "U$1") (pin "SIG") (pinfunction "SIG_SIG") (pintype "bidirectional"))
    )
    (net (code "112") (name "Net-(R95-Pad2)") (class "Default")
      (node (ref "R95") (pin "2") (pinfunction "2_2") (pintype "passive"))
      (node (ref "U$7") (pin "SIG") (pinfunction "SIG_SIG") (pintype "bidirectional"))
    )
    (net (code "113") (name "Net-(R101-Pad2)") (class "Default")
      (node (ref "R101") (pin "2") (pinfunction "2_2") (pintype "passive"))
      (node (ref "R102") (pin "2") (pinfunction "2_2") (pintype "passive"))
    )
    (net (code "114") (name "Net-(U$10-1_RFIN)") (class "Default")
      (node (ref "C29") (pin "2") (pinfunction "2_2") (pintype "passive"))
      (node (ref "U$10") (pin "P1") (pinfunction "1_RFIN_P1") (pintype "bidirectional"))
    )
    (net (code "115") (name "Net-(U$10-3_RFOUT)") (class "Default")
      (node (ref "C28") (pin "1") (pinfunction "1_1") (pintype "passive"))
      (node (ref "R5") (pin "1") (pinfunction "1_1") (pintype "passive"))
      (node (ref "U$10") (pin "P3") (pinfunction "3_RFOUT_P3") (pintype "bidirectional"))
    )
    (net (code "116") (name "Net-(U$36-3_RFC)") (class "Default")
      (node (ref "C36") (pin "2") (pinfunction "2_2") (pintype "passive"))
      (node (ref "U$36") (pin "3") (pinfunction "3_RFC_3") (pintype "bidirectional"))
    )
    (net (code "117") (name "Net-(U$36-7_RF1)") (class "Default")
      (node (ref "C37") (pin "2") (pinfunction "2_2") (pintype "passive"))
      (node (ref "U$36") (pin "7") (pinfunction "7_RF1_7") (pintype "bidirectional"))
    )
    (net (code "118") (name "Net-(U$36-10_B)") (class "Default")
      (node (ref "R81") (pin "2") (pinfunction "2_2") (pintype "passive"))
      (node (ref "U$36") (pin "10") (pinfunction "10_B_10") (pintype "bidirectional"))
    )
    (net (code "119") (name "Net-(U$36-11_A)") (class "Default")
      (node (ref "R80") (pin "2") (pinfunction "2_2") (pintype "passive"))
      (node (ref "U$36") (pin "11") (pinfunction "11_A_11") (pintype "bidirectional"))
    )
    (net (code "120") (name "Net-(U$36-14_RF2)") (class "Default")
      (node (ref "C38") (pin "2") (pinfunction "2_2") (pintype "passive"))
      (node (ref "U$36") (pin "14") (pinfunction "14_RF2_14") (pintype "bidirectional"))
    )
    (net (code "121") (name "Net-(U$40-1_RFIN)") (class "Default")
      (node (ref "C46") (pin "2") (pinfunction "2_2") (pintype "passive"))
      (node (ref "U$40") (pin "P1") (pinfunction "1_RFIN_P1") (pintype "bidirectional"))
    )
    (net (code "122") (name "Net-(U$40-3_RFOUT)") (class "Default")
      (node (ref "C45") (pin "1") (pinfunction "1_1") (pintype "passive"))
      (node (ref "R85") (pin "1") (pinfunction "1_1") (pintype "passive"))
      (node (ref "U$40") (pin "P3") (pinfunction "3_RFOUT_P3") (pintype "bidirectional"))
    )
    (net (code "123") (name "Net-(U$42-1_RFIN)") (class "Default")
      (node (ref "C47") (pin "2") (pinfunction "2_2") (pintype "passive"))
      (node (ref "U$42") (pin "P$1") (pinfunction "1_RFIN_P$1") (pintype "bidirectional"))
    )
    (net (code "124") (name "Net-(U$42-5_LEN)") (class "Default")
      (node (ref "R90") (pin "2") (pinfunction "2_2") (pintype "passive"))
      (node (ref "U$42") (pin "P$5") (pinfunction "5_LEN_P$5") (pintype "bidirectional"))
    )
    (net (code "125") (name "Net-(U$42-6_VOUTADJ)") (class "Default")
      (node (ref "C49") (pin "1") (pinfunction "1_1") (pintype "passive"))
      (node (ref "R87") (pin "2") (pinfunction "2_2") (pintype "passive"))
      (node (ref "U$42") (pin "P$6") (pinfunction "6_VOUTADJ_P$6") (pintype "bidirectional"))
      (node (ref "U$50") (pin "1") (pinfunction "P$1_1") (pintype "bidirectional"))
    )
    (net (code "126") (name "Net-(U$42-7_G0)") (class "Default")
      (node (ref "R89") (pin "2") (pinfunction "2_2") (pintype "passive"))
      (node (ref "U$42") (pin "P$7") (pinfunction "7_G0_P$7") (pintype "bidirectional"))
      (node (ref "U$52") (pin "2") (pinfunction "P$2_2") (pintype "bidirectional"))
    )
    (net (code "127") (name "Net-(U$42-8_G1)") (class "Default")
      (node (ref "R88") (pin "2") (pinfunction "2_2") (pintype "passive"))
      (node (ref "U$42") (pin "P$8") (pinfunction "8_G1_P$8") (pintype "bidirectional"))
      (node (ref "U$51") (pin "2") (pinfunction "P$2_2") (pintype "bidirectional"))
    )
    (net (code "128") (name "Net-(U$42-10_VOUT)") (class "Default")
      (node (ref "U$42") (pin "P$10") (pinfunction "10_VOUT_P$10") (pintype "bidirectional"))
      (node (ref "U$53") (pin "CENTER") (pinfunction "A_CENTER") (pintype "bidirectional"))
    )
    (net (code "129") (name "Net-(U$42-14_VREF)") (class "Default")
      (node (ref "C50") (pin "1") (pinfunction "1_1") (pintype "passive"))
      (node (ref "U$42") (pin "P$14") (pinfunction "14_VREF_P$14") (pintype "bidirectional"))
    )
    (net (code "130") (name "Net-(U$44-A1)") (class "Default")
      (node (ref "R73") (pin "1") (pinfunction "1_1") (pintype "passive"))
      (node (ref "U$37") (pin "A") (pinfunction "A_A") (pintype "bidirectional"))
      (node (ref "U$44") (pin "1") (pinfunction "A1_1") (pintype "bidirectional"))
    )
    (net (code "131") (name "Net-(U$46-2_VT)") (class "Default")
      (node (ref "C42") (pin "1") (pinfunction "1_1") (pintype "passive"))
      (node (ref "U$46") (pin "P$2") (pinfunction "2_VT_P$2") (pintype "bidirectional"))
      (node (ref "U$47") (pin "2") (pinfunction "2_2") (pintype "bidirectional"))
      (node (ref "U$48") (pin "1") (pinfunction "P$1_1") (pintype "bidirectional"))
    )
    (net (code "132") (name "Net-(U$46-10_RF_OUT)") (class "Default")
      (node (ref "R82") (pin "1") (pinfunction "1_1") (pintype "passive"))
      (node (ref "R83") (pin "2") (pinfunction "2_2") (pintype "passive"))
      (node (ref "U$46") (pin "P$10") (pinfunction "10_RF_OUT_P$10") (pintype "bidirectional"))
    )
    (net (code "133") (name "Net-(U$46-14_VCC)") (class "Default")
      (node (ref "C41") (pin "1") (pinfunction "1_1") (pintype "passive"))
      (node (ref "C73") (pin "1") (pinfunction "1_1") (pintype "passive"))
      (node (ref "R97") (pin "1") (pinfunction "1_1") (pintype "passive"))
      (node (ref "U$46") (pin "P$14") (pinfunction "14_VCC_P$14") (pintype "bidirectional"))
    )
    (net (code "134") (name "Net-(U1-DOUT)") (class "Default")
      (node (ref "R1") (pin "1") (pinfunction "1_1") (pintype "passive"))
      (node (ref "U1") (pin "15") (pinfunction "DOUT_15") (pintype "passive"))
    )
    (net (code "135") (name "Net-(U2-DOUT)") (class "Default")
      (node (ref "R2") (pin "1") (pinfunction "1_1") (pintype "passive"))
      (node (ref "U2") (pin "15") (pinfunction "DOUT_15") (pintype "passive"))
    )
    (net (code "136") (name "Net-(U3-DOUT)") (class "Default")
      (node (ref "R3") (pin "1") (pinfunction "1_1") (pintype "passive"))
      (node (ref "U3") (pin "15") (pinfunction "DOUT_15") (pintype "passive"))
    )
    (net (code "137") (name "Net-(U4-DOUT)") (class "Default")
      (node (ref "R4") (pin "1") (pinfunction "1_1") (pintype "passive"))
      (node (ref "U4") (pin "15") (pinfunction "DOUT_15") (pintype "passive"))
    )
    (net (code "138") (name "Net-(U5-DOUT)") (class "Default")
      (node (ref "R7") (pin "1") (pinfunction "1_1") (pintype "passive"))
      (node (ref "U5") (pin "15") (pinfunction "DOUT_15") (pintype "passive"))
    )
    (net (code "139") (name "Net-(U6-DOUT)") (class "Default")
      (node (ref "R8") (pin "1") (pinfunction "1_1") (pintype "passive"))
      (node (ref "U6") (pin "15") (pinfunction "DOUT_15") (pintype "passive"))
    )
    (net (code "140") (name "Net-(U7-DOUT)") (class "Default")
      (node (ref "R49") (pin "1") (pinfunction "1_1") (pintype "passive"))
      (node (ref "U7") (pin "15") (pinfunction "DOUT_15") (pintype "passive"))
    )
    (net (code "141") (name "Net-(U8-DOUT)") (class "Default")
      (node (ref "R50") (pin "1") (pinfunction "1_1") (pintype "passive"))
      (node (ref "U8") (pin "15") (pinfunction "DOUT_15") (pintype "passive"))
    )
    (net (code "142") (name "Net-(U9-DOUT)") (class "Default")
      (node (ref "R51") (pin "1") (pinfunction "1_1") (pintype "passive"))
      (node (ref "U9") (pin "15") (pinfunction "DOUT_15") (pintype "passive"))
    )
    (net (code "143") (name "RESETB") (class "Default")
      (node (ref "R72") (pin "1") (pinfunction "1_1") (pintype "passive"))
      (node (ref "U$4") (pin "P1") (pinfunction "P$1_P1") (pintype "bidirectional"))
      (node (ref "U1") (pin "2") (pinfunction "RESET*_2") (pintype "passive"))
      (node (ref "U2") (pin "2") (pinfunction "RESET*_2") (pintype "passive"))
      (node (ref "U3") (pin "2") (pinfunction "RESET*_2") (pintype "passive"))
      (node (ref "U4") (pin "2") (pinfunction "RESET*_2") (pintype "passive"))
      (node (ref "U5") (pin "2") (pinfunction "RESET*_2") (pintype "passive"))
      (node (ref "U6") (pin "2") (pinfunction "RESET*_2") (pintype "passive"))
      (node (ref "U7") (pin "2") (pinfunction "RESET*_2") (pintype "passive"))
      (node (ref "U8") (pin "2") (pinfunction "RESET*_2") (pintype "passive"))
      (node (ref "U9") (pin "2") (pinfunction "RESET*_2") (pintype "passive"))
    )
    (net (code "144") (name "RFC_1_1") (class "Default")
      (node (ref "U$16") (pin "P$4") (pinfunction "RF1_P$4") (pintype "bidirectional"))
      (node (ref "U$8") (pin "P$10") (pinfunction "RFC_P$10") (pintype "bidirectional"))
    )
    (net (code "145") (name "RFC_1_2") (class "Default")
      (node (ref "U$13") (pin "P$10") (pinfunction "RFC_P$10") (pintype "bidirectional"))
      (node (ref "U$16") (pin "P$17") (pinfunction "RF2_P$17") (pintype "bidirectional"))
    )
    (net (code "146") (name "RFC_1_3") (class "Default")
      (node (ref "U$14") (pin "P$10") (pinfunction "RFC_P$10") (pintype "bidirectional"))
      (node (ref "U$16") (pin "P$7") (pinfunction "RF3_P$7") (pintype "bidirectional"))
    )
    (net (code "147") (name "RFC_1_4") (class "Default")
      (node (ref "U$15") (pin "P$10") (pinfunction "RFC_P$10") (pintype "bidirectional"))
      (node (ref "U$16") (pin "P$14") (pinfunction "RF4_P$14") (pintype "bidirectional"))
    )
    (net (code "148") (name "RFC_1_5") (class "Default")
      (node (ref "U$18") (pin "P$10") (pinfunction "RFC_P$10") (pintype "bidirectional"))
      (node (ref "U$22") (pin "P$4") (pinfunction "RF1_P$4") (pintype "bidirectional"))
    )
    (net (code "149") (name "RFC_1_6") (class "Default")
      (node (ref "U$19") (pin "P$10") (pinfunction "RFC_P$10") (pintype "bidirectional"))
      (node (ref "U$22") (pin "P$17") (pinfunction "RF2_P$17") (pintype "bidirectional"))
    )
    (net (code "150") (name "RFC_1_7") (class "Default")
      (node (ref "U$20") (pin "P$10") (pinfunction "RFC_P$10") (pintype "bidirectional"))
      (node (ref "U$22") (pin "P$7") (pinfunction "RF3_P$7") (pintype "bidirectional"))
    )
    (net (code "151") (name "RFC_1_8") (class "Default")
      (node (ref "U$21") (pin "P$10") (pinfunction "RFC_P$10") (pintype "bidirectional"))
      (node (ref "U$22") (pin "P$14") (pinfunction "RF4_P$14") (pintype "bidirectional"))
    )
    (net (code "152") (name "RFC_1_9") (class "Default")
      (node (ref "U$24") (pin "P$10") (pinfunction "RFC_P$10") (pintype "bidirectional"))
      (node (ref "U$28") (pin "P$4") (pinfunction "RF1_P$4") (pintype "bidirectional"))
    )
    (net (code "153") (name "RFC_1_10") (class "Default")
      (node (ref "U$25") (pin "P$10") (pinfunction "RFC_P$10") (pintype "bidirectional"))
      (node (ref "U$28") (pin "P$17") (pinfunction "RF2_P$17") (pintype "bidirectional"))
    )
    (net (code "154") (name "RFC_1_11") (class "Default")
      (node (ref "U$26") (pin "P$10") (pinfunction "RFC_P$10") (pintype "bidirectional"))
      (node (ref "U$28") (pin "P$7") (pinfunction "RF3_P$7") (pintype "bidirectional"))
    )
    (net (code "155") (name "RFC_1_12") (class "Default")
      (node (ref "U$27") (pin "P$10") (pinfunction "RFC_P$10") (pintype "bidirectional"))
      (node (ref "U$28") (pin "P$14") (pinfunction "RF4_P$14") (pintype "bidirectional"))
    )
    (net (code "156") (name "RFC_1_13") (class "Default")
      (node (ref "U$30") (pin "P$10") (pinfunction "RFC_P$10") (pintype "bidirectional"))
      (node (ref "U$34") (pin "P$4") (pinfunction "RF1_P$4") (pintype "bidirectional"))
    )
    (net (code "157") (name "RFC_1_14") (class "Default")
      (node (ref "U$31") (pin "P$10") (pinfunction "RFC_P$10") (pintype "bidirectional"))
      (node (ref "U$34") (pin "P$17") (pinfunction "RF2_P$17") (pintype "bidirectional"))
    )
    (net (code "158") (name "RFC_1_15") (class "Default")
      (node (ref "U$32") (pin "P$10") (pinfunction "RFC_P$10") (pintype "bidirectional"))
      (node (ref "U$34") (pin "P$7") (pinfunction "RF3_P$7") (pintype "bidirectional"))
    )
    (net (code "159") (name "RFC_1_16") (class "Default")
      (node (ref "U$33") (pin "P$10") (pinfunction "RFC_P$10") (pintype "bidirectional"))
      (node (ref "U$34") (pin "P$14") (pinfunction "RF4_P$14") (pintype "bidirectional"))
    )
    (net (code "160") (name "RFC_2_1") (class "Default")
      (node (ref "U$16") (pin "P$10") (pinfunction "RFC_P$10") (pintype "bidirectional"))
      (node (ref "U$35") (pin "P$7") (pinfunction "RF3_P$7") (pintype "bidirectional"))
    )
    (net (code "161") (name "RFC_2_2") (class "Default")
      (node (ref "U$22") (pin "P$10") (pinfunction "RFC_P$10") (pintype "bidirectional"))
      (node (ref "U$35") (pin "P$4") (pinfunction "RF1_P$4") (pintype "bidirectional"))
    )
    (net (code "162") (name "RFC_2_3") (class "Default")
      (node (ref "U$28") (pin "P$10") (pinfunction "RFC_P$10") (pintype "bidirectional"))
      (node (ref "U$35") (pin "P$17") (pinfunction "RF2_P$17") (pintype "bidirectional"))
    )
    (net (code "163") (name "RFC_2_4") (class "Default")
      (node (ref "U$34") (pin "P$10") (pinfunction "RFC_P$10") (pintype "bidirectional"))
      (node (ref "U$35") (pin "P$14") (pinfunction "RF4_P$14") (pintype "bidirectional"))
    )
    (net (code "164") (name "RFC_3_1") (class "Default")
      (node (ref "U$35") (pin "P$10") (pinfunction "RFC_P$10") (pintype "bidirectional"))
      (node (ref "U$9") (pin "P$4") (pinfunction "RFC_P$4") (pintype "bidirectional"))
    )
    (net (code "165") (name "RF_RX") (class "Default")
      (node (ref "R95") (pin "1") (pinfunction "1_1") (pintype "passive"))
      (node (ref "R96") (pin "2") (pinfunction "2_2") (pintype "passive"))
      (node (ref "U$9") (pin "P$8") (pinfunction "RF1_P$8") (pintype "bidirectional"))
    )
    (net (code "166") (name "RF_SOURCE") (class "Default")
      (node (ref "C36") (pin "1") (pinfunction "1_1") (pintype "passive"))
      (node (ref "R82") (pin "2") (pinfunction "2_2") (pintype "passive"))
    )
    (net (code "167") (name "RF_TX") (class "Default")
      (node (ref "R93") (pin "2") (pinfunction "2_2") (pintype "passive"))
      (node (ref "U$9") (pin "P$5") (pinfunction "RF2_P$5") (pintype "bidirectional"))
    )
    (net (code "168") (name "RX_AMP_OUT") (class "Default")
      (node (ref "C47") (pin "1") (pinfunction "1_1") (pintype "passive"))
      (node (ref "C48") (pin "1") (pinfunction "1_1") (pintype "passive"))
      (node (ref "R92") (pin "1") (pinfunction "1_1") (pintype "passive"))
    )
    (net (code "169") (name "SCK") (class "Default")
      (node (ref "U$4") (pin "P4") (pinfunction "P$4_P4") (pintype "bidirectional"))
      (node (ref "U1") (pin "1") (pinfunction "SCLK_1") (pintype "passive"))
      (node (ref "U2") (pin "1") (pinfunction "SCLK_1") (pintype "passive"))
      (node (ref "U3") (pin "1") (pinfunction "SCLK_1") (pintype "passive"))
      (node (ref "U4") (pin "1") (pinfunction "SCLK_1") (pintype "passive"))
      (node (ref "U5") (pin "1") (pinfunction "SCLK_1") (pintype "passive"))
      (node (ref "U6") (pin "1") (pinfunction "SCLK_1") (pintype "passive"))
      (node (ref "U7") (pin "1") (pinfunction "SCLK_1") (pintype "passive"))
      (node (ref "U8") (pin "1") (pinfunction "SCLK_1") (pintype "passive"))
      (node (ref "U9") (pin "1") (pinfunction "SCLK_1") (pintype "passive"))
    )
    (net (code "170") (name "SX_CTRL_1P") (class "Default")
      (node (ref "R74") (pin "2") (pinfunction "2_2") (pintype "passive"))
      (node (ref "R76") (pin "2") (pinfunction "2_2") (pintype "passive"))
      (node (ref "U$44") (pin "4") (pinfunction "Y2_4") (pintype "bidirectional"))
    )
    (net (code "171") (name "SX_CTRL_N") (class "Default")
      (node (ref "R75") (pin "2") (pinfunction "2_2") (pintype "passive"))
      (node (ref "R77") (pin "2") (pinfunction "2_2") (pintype "passive"))
      (node (ref "U$44") (pin "3") (pinfunction "A2_3") (pintype "bidirectional"))
      (node (ref "U$44") (pin "6") (pinfunction "Y1_6") (pintype "bidirectional"))
    )
    (net (code "172") (name "T1") (class "Default")
      (node (ref "U$14") (pin "P$7") (pinfunction "RF3_P$7") (pintype "bidirectional"))
      (node (ref "U$2") (pin "P$1") (pinfunction "P$1_P$1") (pintype "bidirectional"))
    )
    (net (code "173") (name "T2") (class "Default")
      (node (ref "U$14") (pin "P$4") (pinfunction "RF1_P$4") (pintype "bidirectional"))
      (node (ref "U$2") (pin "P$2") (pinfunction "P$2_P$2") (pintype "bidirectional"))
    )
    (net (code "174") (name "T3") (class "Default")
      (node (ref "U$2") (pin "P$3") (pinfunction "P$3_P$3") (pintype "bidirectional"))
      (node (ref "U$8") (pin "P$7") (pinfunction "RF3_P$7") (pintype "bidirectional"))
    )
    (net (code "175") (name "T4") (class "Default")
      (node (ref "U$2") (pin "P$4") (pinfunction "P$4_P$4") (pintype "bidirectional"))
      (node (ref "U$8") (pin "P$4") (pinfunction "RF1_P$4") (pintype "bidirectional"))
    )
    (net (code "176") (name "T5") (class "Default")
      (node (ref "U$2") (pin "P$5") (pinfunction "P$5_P$5") (pintype "bidirectional"))
      (node (ref "U$8") (pin "P$17") (pinfunction "RF2_P$17") (pintype "bidirectional"))
    )
    (net (code "177") (name "T6") (class "Default")
      (node (ref "U$2") (pin "P$6") (pinfunction "P$6_P$6") (pintype "bidirectional"))
      (node (ref "U$8") (pin "P$14") (pinfunction "RF4_P$14") (pintype "bidirectional"))
    )
    (net (code "178") (name "T7") (class "Default")
      (node (ref "U$14") (pin "P$17") (pinfunction "RF2_P$17") (pintype "bidirectional"))
      (node (ref "U$2") (pin "P$7") (pinfunction "P$7_P$7") (pintype "bidirectional"))
    )
    (net (code "179") (name "T8") (class "Default")
      (node (ref "U$14") (pin "P$14") (pinfunction "RF4_P$14") (pintype "bidirectional"))
      (node (ref "U$2") (pin "P$8") (pinfunction "P$8_P$8") (pintype "bidirectional"))
    )
    (net (code "180") (name "T9") (class "Default")
      (node (ref "U$15") (pin "P$7") (pinfunction "RF3_P$7") (pintype "bidirectional"))
      (node (ref "U$2") (pin "P$9") (pinfunction "P$9_P$9") (pintype "bidirectional"))
    )
    (net (code "181") (name "T10") (class "Default")
      (node (ref "U$15") (pin "P$4") (pinfunction "RF1_P$4") (pintype "bidirectional"))
      (node (ref "U$2") (pin "P$10") (pinfunction "P$10_P$10") (pintype "bidirectional"))
    )
    (net (code "182") (name "T11") (class "Default")
      (node (ref "U$13") (pin "P$7") (pinfunction "RF3_P$7") (pintype "bidirectional"))
      (node (ref "U$2") (pin "P$11") (pinfunction "P$11_P$11") (pintype "bidirectional"))
    )
    (net (code "183") (name "T12") (class "Default")
      (node (ref "U$13") (pin "P$4") (pinfunction "RF1_P$4") (pintype "bidirectional"))
      (node (ref "U$2") (pin "P$12") (pinfunction "P$12_P$12") (pintype "bidirectional"))
    )
    (net (code "184") (name "T13") (class "Default")
      (node (ref "U$13") (pin "P$17") (pinfunction "RF2_P$17") (pintype "bidirectional"))
      (node (ref "U$2") (pin "P$13") (pinfunction "P$13_P$13") (pintype "bidirectional"))
    )
    (net (code "185") (name "T14") (class "Default")
      (node (ref "U$13") (pin "P$14") (pinfunction "RF4_P$14") (pintype "bidirectional"))
      (node (ref "U$2") (pin "P$14") (pinfunction "P$14_P$14") (pintype "bidirectional"))
    )
    (net (code "186") (name "T15") (class "Default")
      (node (ref "U$15") (pin "P$17") (pinfunction "RF2_P$17") (pintype "bidirectional"))
      (node (ref "U$2") (pin "P$15") (pinfunction "P$15_P$15") (pintype "bidirectional"))
    )
    (net (code "187") (name "T16") (class "Default")
      (node (ref "U$15") (pin "P$14") (pinfunction "RF4_P$14") (pintype "bidirectional"))
      (node (ref "U$2") (pin "P$16") (pinfunction "P$16_P$16") (pintype "bidirectional"))
    )
    (net (code "188") (name "T17") (class "Default")
      (node (ref "U$17") (pin "P$1") (pinfunction "P$1_P$1") (pintype "bidirectional"))
      (node (ref "U$20") (pin "P$7") (pinfunction "RF3_P$7") (pintype "bidirectional"))
    )
    (net (code "189") (name "T18") (class "Default")
      (node (ref "U$17") (pin "P$2") (pinfunction "P$2_P$2") (pintype "bidirectional"))
      (node (ref "U$20") (pin "P$4") (pinfunction "RF1_P$4") (pintype "bidirectional"))
    )
    (net (code "190") (name "T19") (class "Default")
      (node (ref "U$17") (pin "P$3") (pinfunction "P$3_P$3") (pintype "bidirectional"))
      (node (ref "U$18") (pin "P$7") (pinfunction "RF3_P$7") (pintype "bidirectional"))
    )
    (net (code "191") (name "T20") (class "Default")
      (node (ref "U$17") (pin "P$4") (pinfunction "P$4_P$4") (pintype "bidirectional"))
      (node (ref "U$18") (pin "P$4") (pinfunction "RF1_P$4") (pintype "bidirectional"))
    )
    (net (code "192") (name "T21") (class "Default")
      (node (ref "U$17") (pin "P$5") (pinfunction "P$5_P$5") (pintype "bidirectional"))
      (node (ref "U$18") (pin "P$17") (pinfunction "RF2_P$17") (pintype "bidirectional"))
    )
    (net (code "193") (name "T22") (class "Default")
      (node (ref "U$17") (pin "P$6") (pinfunction "P$6_P$6") (pintype "bidirectional"))
      (node (ref "U$18") (pin "P$14") (pinfunction "RF4_P$14") (pintype "bidirectional"))
    )
    (net (code "194") (name "T23") (class "Default")
      (node (ref "U$17") (pin "P$7") (pinfunction "P$7_P$7") (pintype "bidirectional"))
      (node (ref "U$20") (pin "P$17") (pinfunction "RF2_P$17") (pintype "bidirectional"))
    )
    (net (code "195") (name "T24") (class "Default")
      (node (ref "U$17") (pin "P$8") (pinfunction "P$8_P$8") (pintype "bidirectional"))
      (node (ref "U$20") (pin "P$14") (pinfunction "RF4_P$14") (pintype "bidirectional"))
    )
    (net (code "196") (name "T25") (class "Default")
      (node (ref "U$17") (pin "P$9") (pinfunction "P$9_P$9") (pintype "bidirectional"))
      (node (ref "U$21") (pin "P$7") (pinfunction "RF3_P$7") (pintype "bidirectional"))
    )
    (net (code "197") (name "T26") (class "Default")
      (node (ref "U$17") (pin "P$10") (pinfunction "P$10_P$10") (pintype "bidirectional"))
      (node (ref "U$21") (pin "P$4") (pinfunction "RF1_P$4") (pintype "bidirectional"))
    )
    (net (code "198") (name "T27") (class "Default")
      (node (ref "U$17") (pin "P$11") (pinfunction "P$11_P$11") (pintype "bidirectional"))
      (node (ref "U$19") (pin "P$7") (pinfunction "RF3_P$7") (pintype "bidirectional"))
    )
    (net (code "199") (name "T28") (class "Default")
      (node (ref "U$17") (pin "P$12") (pinfunction "P$12_P$12") (pintype "bidirectional"))
      (node (ref "U$19") (pin "P$4") (pinfunction "RF1_P$4") (pintype "bidirectional"))
    )
    (net (code "200") (name "T29") (class "Default")
      (node (ref "U$17") (pin "P$13") (pinfunction "P$13_P$13") (pintype "bidirectional"))
      (node (ref "U$19") (pin "P$17") (pinfunction "RF2_P$17") (pintype "bidirectional"))
    )
    (net (code "201") (name "T30") (class "Default")
      (node (ref "U$17") (pin "P$14") (pinfunction "P$14_P$14") (pintype "bidirectional"))
      (node (ref "U$19") (pin "P$14") (pinfunction "RF4_P$14") (pintype "bidirectional"))
    )
    (net (code "202") (name "T31") (class "Default")
      (node (ref "U$17") (pin "P$15") (pinfunction "P$15_P$15") (pintype "bidirectional"))
      (node (ref "U$21") (pin "P$17") (pinfunction "RF2_P$17") (pintype "bidirectional"))
    )
    (net (code "203") (name "T32") (class "Default")
      (node (ref "U$17") (pin "P$16") (pinfunction "P$16_P$16") (pintype "bidirectional"))
      (node (ref "U$21") (pin "P$14") (pinfunction "RF4_P$14") (pintype "bidirectional"))
    )
    (net (code "204") (name "T33") (class "Default")
      (node (ref "U$23") (pin "P$1") (pinfunction "P$1_P$1") (pintype "bidirectional"))
      (node (ref "U$26") (pin "P$7") (pinfunction "RF3_P$7") (pintype "bidirectional"))
    )
    (net (code "205") (name "T34") (class "Default")
      (node (ref "U$23") (pin "P$2") (pinfunction "P$2_P$2") (pintype "bidirectional"))
      (node (ref "U$26") (pin "P$4") (pinfunction "RF1_P$4") (pintype "bidirectional"))
    )
    (net (code "206") (name "T35") (class "Default")
      (node (ref "U$23") (pin "P$3") (pinfunction "P$3_P$3") (pintype "bidirectional"))
      (node (ref "U$24") (pin "P$7") (pinfunction "RF3_P$7") (pintype "bidirectional"))
    )
    (net (code "207") (name "T36") (class "Default")
      (node (ref "U$23") (pin "P$4") (pinfunction "P$4_P$4") (pintype "bidirectional"))
      (node (ref "U$24") (pin "P$4") (pinfunction "RF1_P$4") (pintype "bidirectional"))
    )
    (net (code "208") (name "T37") (class "Default")
      (node (ref "U$23") (pin "P$5") (pinfunction "P$5_P$5") (pintype "bidirectional"))
      (node (ref "U$24") (pin "P$17") (pinfunction "RF2_P$17") (pintype "bidirectional"))
    )
    (net (code "209") (name "T38") (class "Default")
      (node (ref "U$23") (pin "P$6") (pinfunction "P$6_P$6") (pintype "bidirectional"))
      (node (ref "U$24") (pin "P$14") (pinfunction "RF4_P$14") (pintype "bidirectional"))
    )
    (net (code "210") (name "T39") (class "Default")
      (node (ref "U$23") (pin "P$7") (pinfunction "P$7_P$7") (pintype "bidirectional"))
      (node (ref "U$26") (pin "P$17") (pinfunction "RF2_P$17") (pintype "bidirectional"))
    )
    (net (code "211") (name "T40") (class "Default")
      (node (ref "U$23") (pin "P$8") (pinfunction "P$8_P$8") (pintype "bidirectional"))
      (node (ref "U$26") (pin "P$14") (pinfunction "RF4_P$14") (pintype "bidirectional"))
    )
    (net (code "212") (name "T41") (class "Default")
      (node (ref "U$23") (pin "P$9") (pinfunction "P$9_P$9") (pintype "bidirectional"))
      (node (ref "U$27") (pin "P$7") (pinfunction "RF3_P$7") (pintype "bidirectional"))
    )
    (net (code "213") (name "T42") (class "Default")
      (node (ref "U$23") (pin "P$10") (pinfunction "P$10_P$10") (pintype "bidirectional"))
      (node (ref "U$27") (pin "P$4") (pinfunction "RF1_P$4") (pintype "bidirectional"))
    )
    (net (code "214") (name "T43") (class "Default")
      (node (ref "U$23") (pin "P$11") (pinfunction "P$11_P$11") (pintype "bidirectional"))
      (node (ref "U$25") (pin "P$7") (pinfunction "RF3_P$7") (pintype "bidirectional"))
    )
    (net (code "215") (name "T44") (class "Default")
      (node (ref "U$23") (pin "P$12") (pinfunction "P$12_P$12") (pintype "bidirectional"))
      (node (ref "U$25") (pin "P$4") (pinfunction "RF1_P$4") (pintype "bidirectional"))
    )
    (net (code "216") (name "T45") (class "Default")
      (node (ref "U$23") (pin "P$13") (pinfunction "P$13_P$13") (pintype "bidirectional"))
      (node (ref "U$25") (pin "P$17") (pinfunction "RF2_P$17") (pintype "bidirectional"))
    )
    (net (code "217") (name "T46") (class "Default")
      (node (ref "U$23") (pin "P$14") (pinfunction "P$14_P$14") (pintype "bidirectional"))
      (node (ref "U$25") (pin "P$14") (pinfunction "RF4_P$14") (pintype "bidirectional"))
    )
    (net (code "218") (name "T47") (class "Default")
      (node (ref "U$23") (pin "P$15") (pinfunction "P$15_P$15") (pintype "bidirectional"))
      (node (ref "U$27") (pin "P$17") (pinfunction "RF2_P$17") (pintype "bidirectional"))
    )
    (net (code "219") (name "T48") (class "Default")
      (node (ref "U$23") (pin "P$16") (pinfunction "P$16_P$16") (pintype "bidirectional"))
      (node (ref "U$27") (pin "P$14") (pinfunction "RF4_P$14") (pintype "bidirectional"))
    )
    (net (code "220") (name "T49") (class "Default")
      (node (ref "U$29") (pin "P$1") (pinfunction "P$1_P$1") (pintype "bidirectional"))
      (node (ref "U$32") (pin "P$7") (pinfunction "RF3_P$7") (pintype "bidirectional"))
    )
    (net (code "221") (name "T50") (class "Default")
      (node (ref "U$29") (pin "P$2") (pinfunction "P$2_P$2") (pintype "bidirectional"))
      (node (ref "U$32") (pin "P$4") (pinfunction "RF1_P$4") (pintype "bidirectional"))
    )
    (net (code "222") (name "T51") (class "Default")
      (node (ref "U$29") (pin "P$3") (pinfunction "P$3_P$3") (pintype "bidirectional"))
      (node (ref "U$30") (pin "P$7") (pinfunction "RF3_P$7") (pintype "bidirectional"))
    )
    (net (code "223") (name "T52") (class "Default")
      (node (ref "U$29") (pin "P$4") (pinfunction "P$4_P$4") (pintype "bidirectional"))
      (node (ref "U$30") (pin "P$4") (pinfunction "RF1_P$4") (pintype "bidirectional"))
    )
    (net (code "224") (name "T53") (class "Default")
      (node (ref "U$29") (pin "P$5") (pinfunction "P$5_P$5") (pintype "bidirectional"))
      (node (ref "U$30") (pin "P$17") (pinfunction "RF2_P$17") (pintype "bidirectional"))
    )
    (net (code "225") (name "T54") (class "Default")
      (node (ref "U$29") (pin "P$6") (pinfunction "P$6_P$6") (pintype "bidirectional"))
      (node (ref "U$30") (pin "P$14") (pinfunction "RF4_P$14") (pintype "bidirectional"))
    )
    (net (code "226") (name "T55") (class "Default")
      (node (ref "U$29") (pin "P$7") (pinfunction "P$7_P$7") (pintype "bidirectional"))
      (node (ref "U$32") (pin "P$17") (pinfunction "RF2_P$17") (pintype "bidirectional"))
    )
    (net (code "227") (name "T56") (class "Default")
      (node (ref "U$29") (pin "P$8") (pinfunction "P$8_P$8") (pintype "bidirectional"))
      (node (ref "U$32") (pin "P$14") (pinfunction "RF4_P$14") (pintype "bidirectional"))
    )
    (net (code "228") (name "T57") (class "Default")
      (node (ref "U$29") (pin "P$9") (pinfunction "P$9_P$9") (pintype "bidirectional"))
      (node (ref "U$33") (pin "P$7") (pinfunction "RF3_P$7") (pintype "bidirectional"))
    )
    (net (code "229") (name "T58") (class "Default")
      (node (ref "U$29") (pin "P$10") (pinfunction "P$10_P$10") (pintype "bidirectional"))
      (node (ref "U$33") (pin "P$4") (pinfunction "RF1_P$4") (pintype "bidirectional"))
    )
    (net (code "230") (name "T59") (class "Default")
      (node (ref "U$29") (pin "P$11") (pinfunction "P$11_P$11") (pintype "bidirectional"))
      (node (ref "U$31") (pin "P$7") (pinfunction "RF3_P$7") (pintype "bidirectional"))
    )
    (net (code "231") (name "T60") (class "Default")
      (node (ref "U$29") (pin "P$12") (pinfunction "P$12_P$12") (pintype "bidirectional"))
      (node (ref "U$31") (pin "P$4") (pinfunction "RF1_P$4") (pintype "bidirectional"))
    )
    (net (code "232") (name "T61") (class "Default")
      (node (ref "U$29") (pin "P$13") (pinfunction "P$13_P$13") (pintype "bidirectional"))
      (node (ref "U$31") (pin "P$17") (pinfunction "RF2_P$17") (pintype "bidirectional"))
    )
    (net (code "233") (name "T62") (class "Default")
      (node (ref "U$29") (pin "P$14") (pinfunction "P$14_P$14") (pintype "bidirectional"))
      (node (ref "U$31") (pin "P$14") (pinfunction "RF4_P$14") (pintype "bidirectional"))
    )
    (net (code "234") (name "T63") (class "Default")
      (node (ref "U$29") (pin "P$15") (pinfunction "P$15_P$15") (pintype "bidirectional"))
      (node (ref "U$33") (pin "P$17") (pinfunction "RF2_P$17") (pintype "bidirectional"))
    )
    (net (code "235") (name "T64") (class "Default")
      (node (ref "U$29") (pin "P$16") (pinfunction "P$16_P$16") (pintype "bidirectional"))
      (node (ref "U$33") (pin "P$14") (pinfunction "RF4_P$14") (pintype "bidirectional"))
    )
    (net (code "236") (name "TX_PULSE") (class "Default")
      (node (ref "U$37") (pin "C") (pinfunction "C_C") (pintype "bidirectional"))
      (node (ref "U$4") (pin "P68") (pinfunction "P$68_P68") (pintype "bidirectional"))
    )
    (net (code "237") (name "TX_SWITCH_OUT") (class "Default")
      (node (ref "C37") (pin "1") (pinfunction "1_1") (pintype "passive"))
      (node (ref "R101") (pin "1") (pinfunction "1_1") (pintype "passive"))
      (node (ref "R79") (pin "1") (pinfunction "1_1") (pintype "passive"))
      (node (ref "R84") (pin "2") (pinfunction "2_2") (pintype "passive"))
    )
    (net (code "238") (name "V+3V") (class "Default")
      (node (ref "C67") (pin "PIN+") (pinfunction "PIN+_PIN+") (pintype "passive"))
      (node (ref "C68") (pin "1") (pinfunction "1_1") (pintype "passive"))
      (node (ref "C69") (pin "1") (pinfunction "1_1") (pintype "passive"))
      (node (ref "C70") (pin "1") (pinfunction "1_1") (pintype "passive"))
      (node (ref "C71") (pin "1") (pinfunction "1_1") (pintype "passive"))
      (node (ref "C72") (pin "1") (pinfunction "1_1") (pintype "passive"))
      (node (ref "R97") (pin "2") (pinfunction "2_2") (pintype "passive"))
      (node (ref "U$59") (pin "A") (pinfunction "A_A") (pintype "bidirectional"))
      (node (ref "U$59") (pin "B") (pinfunction "B_B") (pintype "bidirectional"))
    )
    (net (code "239") (name "V_2P5") (class "Default")
      (node (ref "C1") (pin "1") (pinfunction "1_1") (pintype "passive"))
      (node (ref "C10") (pin "1") (pinfunction "1_1") (pintype "passive"))
      (node (ref "C11") (pin "1") (pinfunction "1_1") (pintype "passive"))
      (node (ref "C12") (pin "1") (pinfunction "1_1") (pintype "passive"))
      (node (ref "C13") (pin "1") (pinfunction "1_1") (pintype "passive"))
      (node (ref "C14") (pin "1") (pinfunction "1_1") (pintype "passive"))
      (node (ref "C15") (pin "1") (pinfunction "1_1") (pintype "passive"))
      (node (ref "C16") (pin "1") (pinfunction "1_1") (pintype "passive"))
      (node (ref "C17") (pin "1") (pinfunction "1_1") (pintype "passive"))
      (node (ref "C18") (pin "1") (pinfunction "1_1") (pintype "passive"))
      (node (ref "C19") (pin "1") (pinfunction "1_1") (pintype "passive"))
      (node (ref "C2") (pin "1") (pinfunction "1_1") (pintype "passive"))
      (node (ref "C20") (pin "1") (pinfunction "1_1") (pintype "passive"))
      (node (ref "C21") (pin "1") (pinfunction "1_1") (pintype "passive"))
      (node (ref "C25") (pin "1") (pinfunction "1_1") (pintype "passive"))
      (node (ref "C3") (pin "1") (pinfunction "1_1") (pintype "passive"))
      (node (ref "C4") (pin "1") (pinfunction "1_1") (pintype "passive"))
      (node (ref "C5") (pin "1") (pinfunction "1_1") (pintype "passive"))
      (node (ref "C59") (pin "PIN+") (pinfunction "PIN+_PIN+") (pintype "passive"))
      (node (ref "C6") (pin "1") (pinfunction "1_1") (pintype "passive"))
      (node (ref "C60") (pin "1") (pinfunction "1_1") (pintype "passive"))
      (node (ref "C61") (pin "1") (pinfunction "1_1") (pintype "passive"))
      (node (ref "C66") (pin "1") (pinfunction "1_1") (pintype "passive"))
      (node (ref "C7") (pin "1") (pinfunction "1_1") (pintype "passive"))
      (node (ref "C8") (pin "1") (pinfunction "1_1") (pintype "passive"))
      (node (ref "C9") (pin "1") (pinfunction "1_1") (pintype "passive"))
      (node (ref "R98") (pin "1") (pinfunction "1_1") (pintype "passive"))
      (node (ref "U$13") (pin "P$2") (pinfunction "VDD_P$2") (pintype "bidirectional"))
      (node (ref "U$14") (pin "P$2") (pinfunction "VDD_P$2") (pintype "bidirectional"))
      (node (ref "U$15") (pin "P$2") (pinfunction "VDD_P$2") (pintype "bidirectional"))
      (node (ref "U$16") (pin "P$2") (pinfunction "VDD_P$2") (pintype "bidirectional"))
      (node (ref "U$18") (pin "P$2") (pinfunction "VDD_P$2") (pintype "bidirectional"))
      (node (ref "U$19") (pin "P$2") (pinfunction "VDD_P$2") (pintype "bidirectional"))
      (node (ref "U$20") (pin "P$2") (pinfunction "VDD_P$2") (pintype "bidirectional"))
      (node (ref "U$21") (pin "P$2") (pinfunction "VDD_P$2") (pintype "bidirectional"))
      (node (ref "U$22") (pin "P$2") (pinfunction "VDD_P$2") (pintype "bidirectional"))
      (node (ref "U$24") (pin "P$2") (pinfunction "VDD_P$2") (pintype "bidirectional"))
      (node (ref "U$25") (pin "P$2") (pinfunction "VDD_P$2") (pintype "bidirectional"))
      (node (ref "U$26") (pin "P$2") (pinfunction "VDD_P$2") (pintype "bidirectional"))
      (node (ref "U$27") (pin "P$2") (pinfunction "VDD_P$2") (pintype "bidirectional"))
      (node (ref "U$28") (pin "P$2") (pinfunction "VDD_P$2") (pintype "bidirectional"))
      (node (ref "U$30") (pin "P$2") (pinfunction "VDD_P$2") (pintype "bidirectional"))
      (node (ref "U$31") (pin "P$2") (pinfunction "VDD_P$2") (pintype "bidirectional"))
      (node (ref "U$32") (pin "P$2") (pinfunction "VDD_P$2") (pintype "bidirectional"))
      (node (ref "U$33") (pin "P$2") (pinfunction "VDD_P$2") (pintype "bidirectional"))
      (node (ref "U$34") (pin "P$2") (pinfunction "VDD_P$2") (pintype "bidirectional"))
      (node (ref "U$35") (pin "P$2") (pinfunction "VDD_P$2") (pintype "bidirectional"))
      (node (ref "U$58") (pin "A") (pinfunction "A_A") (pintype "bidirectional"))
      (node (ref "U$58") (pin "B") (pinfunction "B_B") (pintype "bidirectional"))
      (node (ref "U$8") (pin "P$2") (pinfunction "VDD_P$2") (pintype "bidirectional"))
      (node (ref "U$9") (pin "P$1") (pinfunction "VDD_P$1") (pintype "bidirectional"))
    )
    (net (code "240") (name "unconnected-(U$4-P$15-PadP15)") (class "Default")
      (node (ref "U$4") (pin "P15") (pinfunction "P$15_P15") (pintype "bidirectional"))
    )
    (net (code "241") (name "unconnected-(U$4-P$16-PadP16)") (class "Default")
      (node (ref "U$4") (pin "P16") (pinfunction "P$16_P16") (pintype "bidirectional"))
    )
    (net (code "242") (name "unconnected-(U$4-P$17-PadP17)") (class "Default")
      (node (ref "U$4") (pin "P17") (pinfunction "P$17_P17") (pintype "bidirectional"))
    )
    (net (code "243") (name "unconnected-(U$4-P$18-PadP18)") (class "Default")
      (node (ref "U$4") (pin "P18") (pinfunction "P$18_P18") (pintype "bidirectional"))
    )
    (net (code "244") (name "unconnected-(U$4-P$19-PadP19)") (class "Default")
      (node (ref "U$4") (pin "P19") (pinfunction "P$19_P19") (pintype "bidirectional"))
    )
    (net (code "245") (name "unconnected-(U$4-P$20-PadP20)") (class "Default")
      (node (ref "U$4") (pin "P20") (pinfunction "P$20_P20") (pintype "bidirectional"))
    )
    (net (code "246") (name "unconnected-(U$4-P$49-PadP49)") (class "Default")
      (node (ref "U$4") (pin "P49") (pinfunction "P$49_P49") (pintype "bidirectional"))
    )
    (net (code "247") (name "unconnected-(U$4-P$50-PadP50)") (class "Default")
      (node (ref "U$4") (pin "P50") (pinfunction "P$50_P50") (pintype "bidirectional"))
    )
    (net (code "248") (name "unconnected-(U$4-P$51-PadP51)") (class "Default")
      (node (ref "U$4") (pin "P51") (pinfunction "P$51_P51") (pintype "bidirectional"))
    )
    (net (code "249") (name "unconnected-(U$4-P$52-PadP52)") (class "Default")
      (node (ref "U$4") (pin "P52") (pinfunction "P$52_P52") (pintype "bidirectional"))
    )
    (net (code "250") (name "unconnected-(U$4-P$53-PadP53)") (class "Default")
      (node (ref "U$4") (pin "P53") (pinfunction "P$53_P53") (pintype "bidirectional"))
    )
    (net (code "251") (name "unconnected-(U$4-P$54-PadP54)") (class "Default")
      (node (ref "U$4") (pin "P54") (pinfunction "P$54_P54") (pintype "bidirectional"))
    )
    (net (code "252") (name "unconnected-(U$42-2_NC-PadP$2)") (class "Default")
      (node (ref "U$42") (pin "P$2") (pinfunction "2_NC_P$2") (pintype "bidirectional"))
    )
    (net (code "253") (name "unconnected-(U$42-9_NC-PadP$9)") (class "Default")
      (node (ref "U$42") (pin "P$9") (pinfunction "9_NC_P$9") (pintype "bidirectional"))
    )
    (net (code "254") (name "unconnected-(U$42-13_VCOMP-PadP$13)") (class "Default")
      (node (ref "U$42") (pin "P$13") (pinfunction "13_VCOMP_P$13") (pintype "bidirectional"))
    )
    (net (code "255") (name "unconnected-(U$42-16_NC-PadP$16)") (class "Default")
      (node (ref "U$42") (pin "P$16") (pinfunction "16_NC_P$16") (pintype "bidirectional"))
    )
    (net (code "256") (name "unconnected-(U3-S5-Pad12)") (class "Default")
      (node (ref "U3") (pin "12") (pinfunction "S5_12") (pintype "passive"))
    )
    (net (code "257") (name "unconnected-(U3-S6-Pad11)") (class "Default")
      (node (ref "U3") (pin "11") (pinfunction "S6_11") (pintype "passive"))
    )
    (net (code "258") (name "unconnected-(U3-S7-Pad10)") (class "Default")
      (node (ref "U3") (pin "10") (pinfunction "S7_10") (pintype "passive"))
    )
    (net (code "259") (name "unconnected-(U3-S8-Pad9)") (class "Default")
      (node (ref "U3") (pin "9") (pinfunction "S8_9") (pintype "passive"))
    )
    (net (code "260") (name "unconnected-(U6-S5-Pad12)") (class "Default")
      (node (ref "U6") (pin "12") (pinfunction "S5_12") (pintype "passive"))
    )
    (net (code "261") (name "unconnected-(U6-S6-Pad11)") (class "Default")
      (node (ref "U6") (pin "11") (pinfunction "S6_11") (pintype "passive"))
    )
    (net (code "262") (name "unconnected-(U6-S7-Pad10)") (class "Default")
      (node (ref "U6") (pin "10") (pinfunction "S7_10") (pintype "passive"))
    )
    (net (code "263") (name "unconnected-(U6-S8-Pad9)") (class "Default")
      (node (ref "U6") (pin "9") (pinfunction "S8_9") (pintype "passive"))
    )
    (net (code "264") (name "unconnected-(U9-S5-Pad12)") (class "Default")
      (node (ref "U9") (pin "12") (pinfunction "S5_12") (pintype "passive"))
    )
    (net (code "265") (name "unconnected-(U9-S6-Pad11)") (class "Default")
      (node (ref "U9") (pin "11") (pinfunction "S6_11") (pintype "passive"))
    )
    (net (code "266") (name "unconnected-(U9-S7-Pad10)") (class "Default")
      (node (ref "U9") (pin "10") (pinfunction "S7_10") (pintype "passive"))
    )
    (net (code "267") (name "unconnected-(U9-S8-Pad9)") (class "Default")
      (node (ref "U9") (pin "9") (pinfunction "S8_9") (pintype "passive"))
    )
  )
)
